# CB_1-2.net
KiCad netlist of a schematic drawn in EAGLE
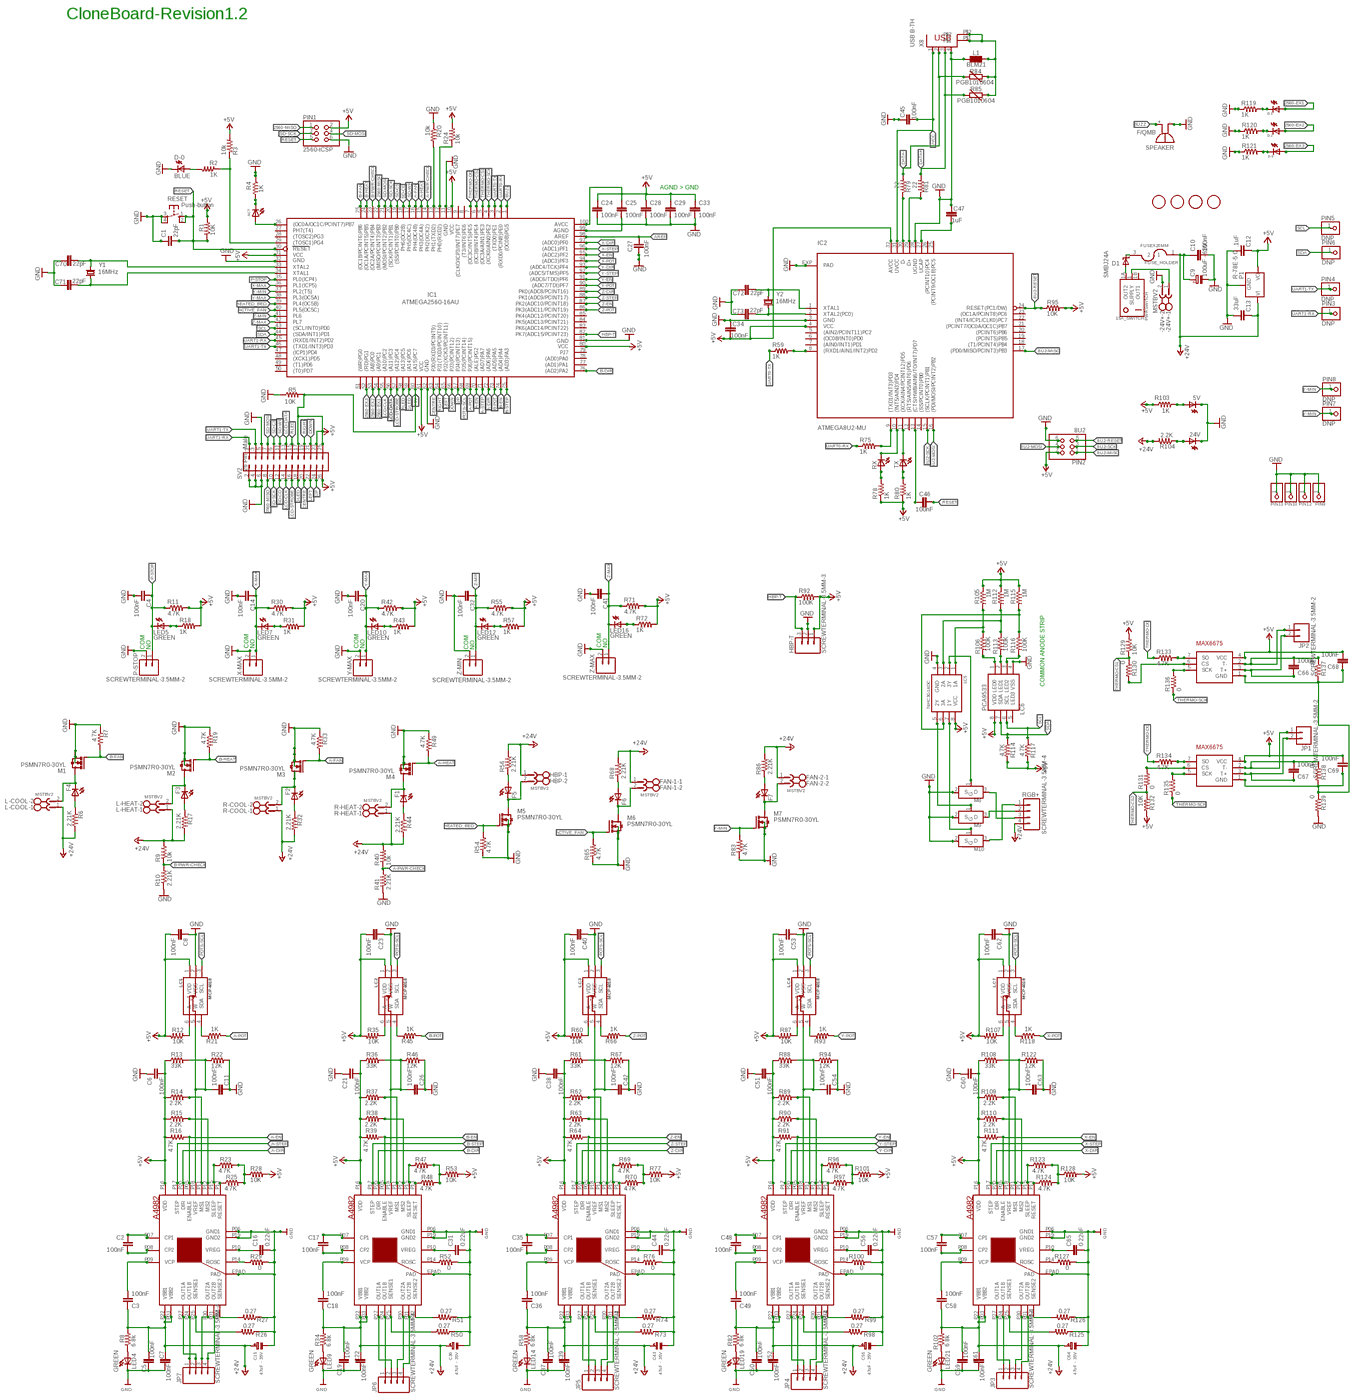
[diagram p0: schematic, sheet 1, overview]
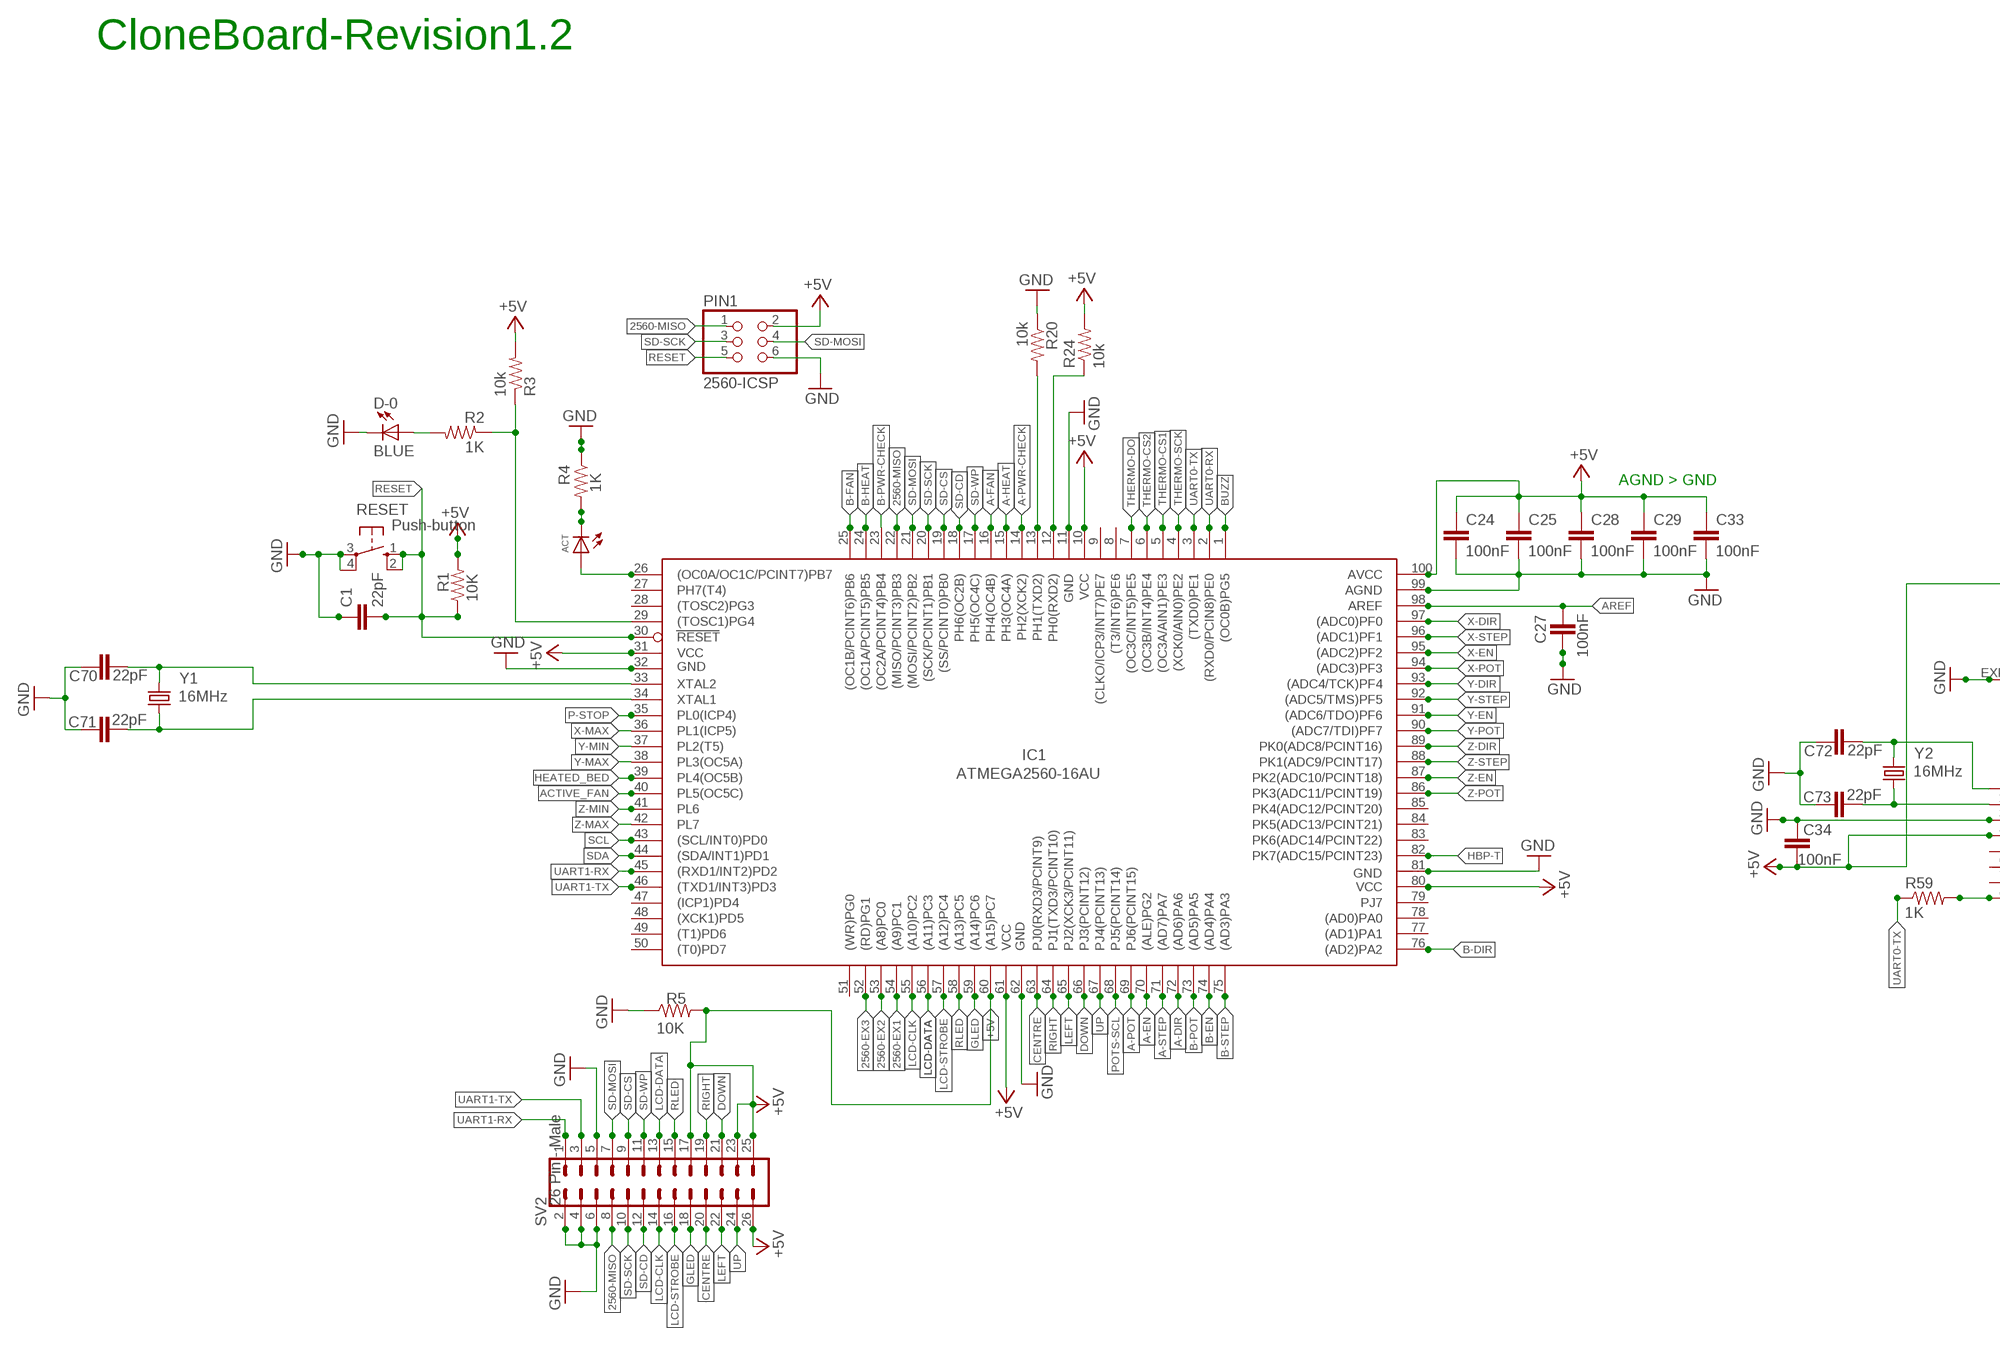
[diagram p1: schematic, sheet 1, part 1 of 4]
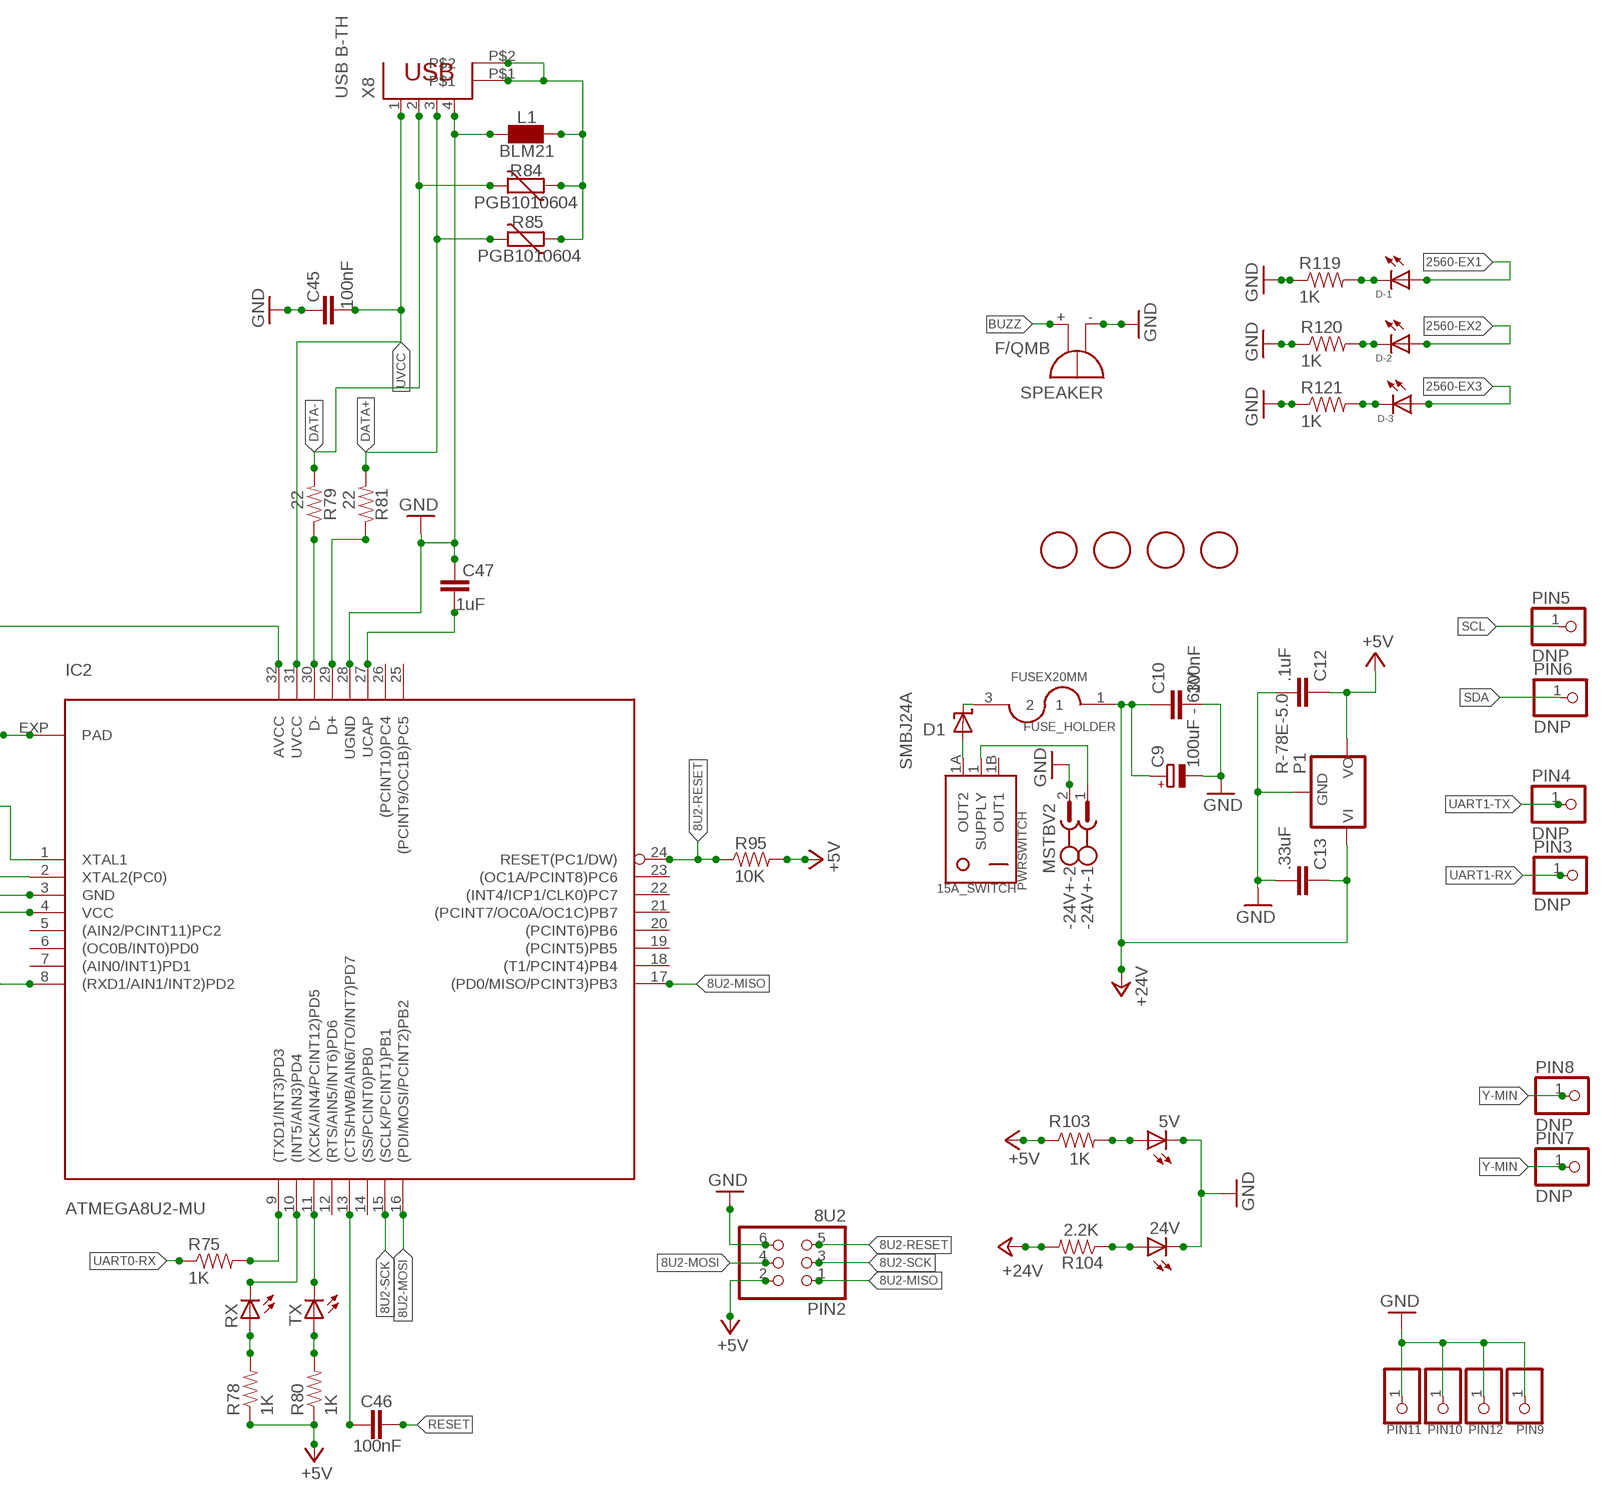
[diagram p2: schematic, sheet 1, part 2 of 4]
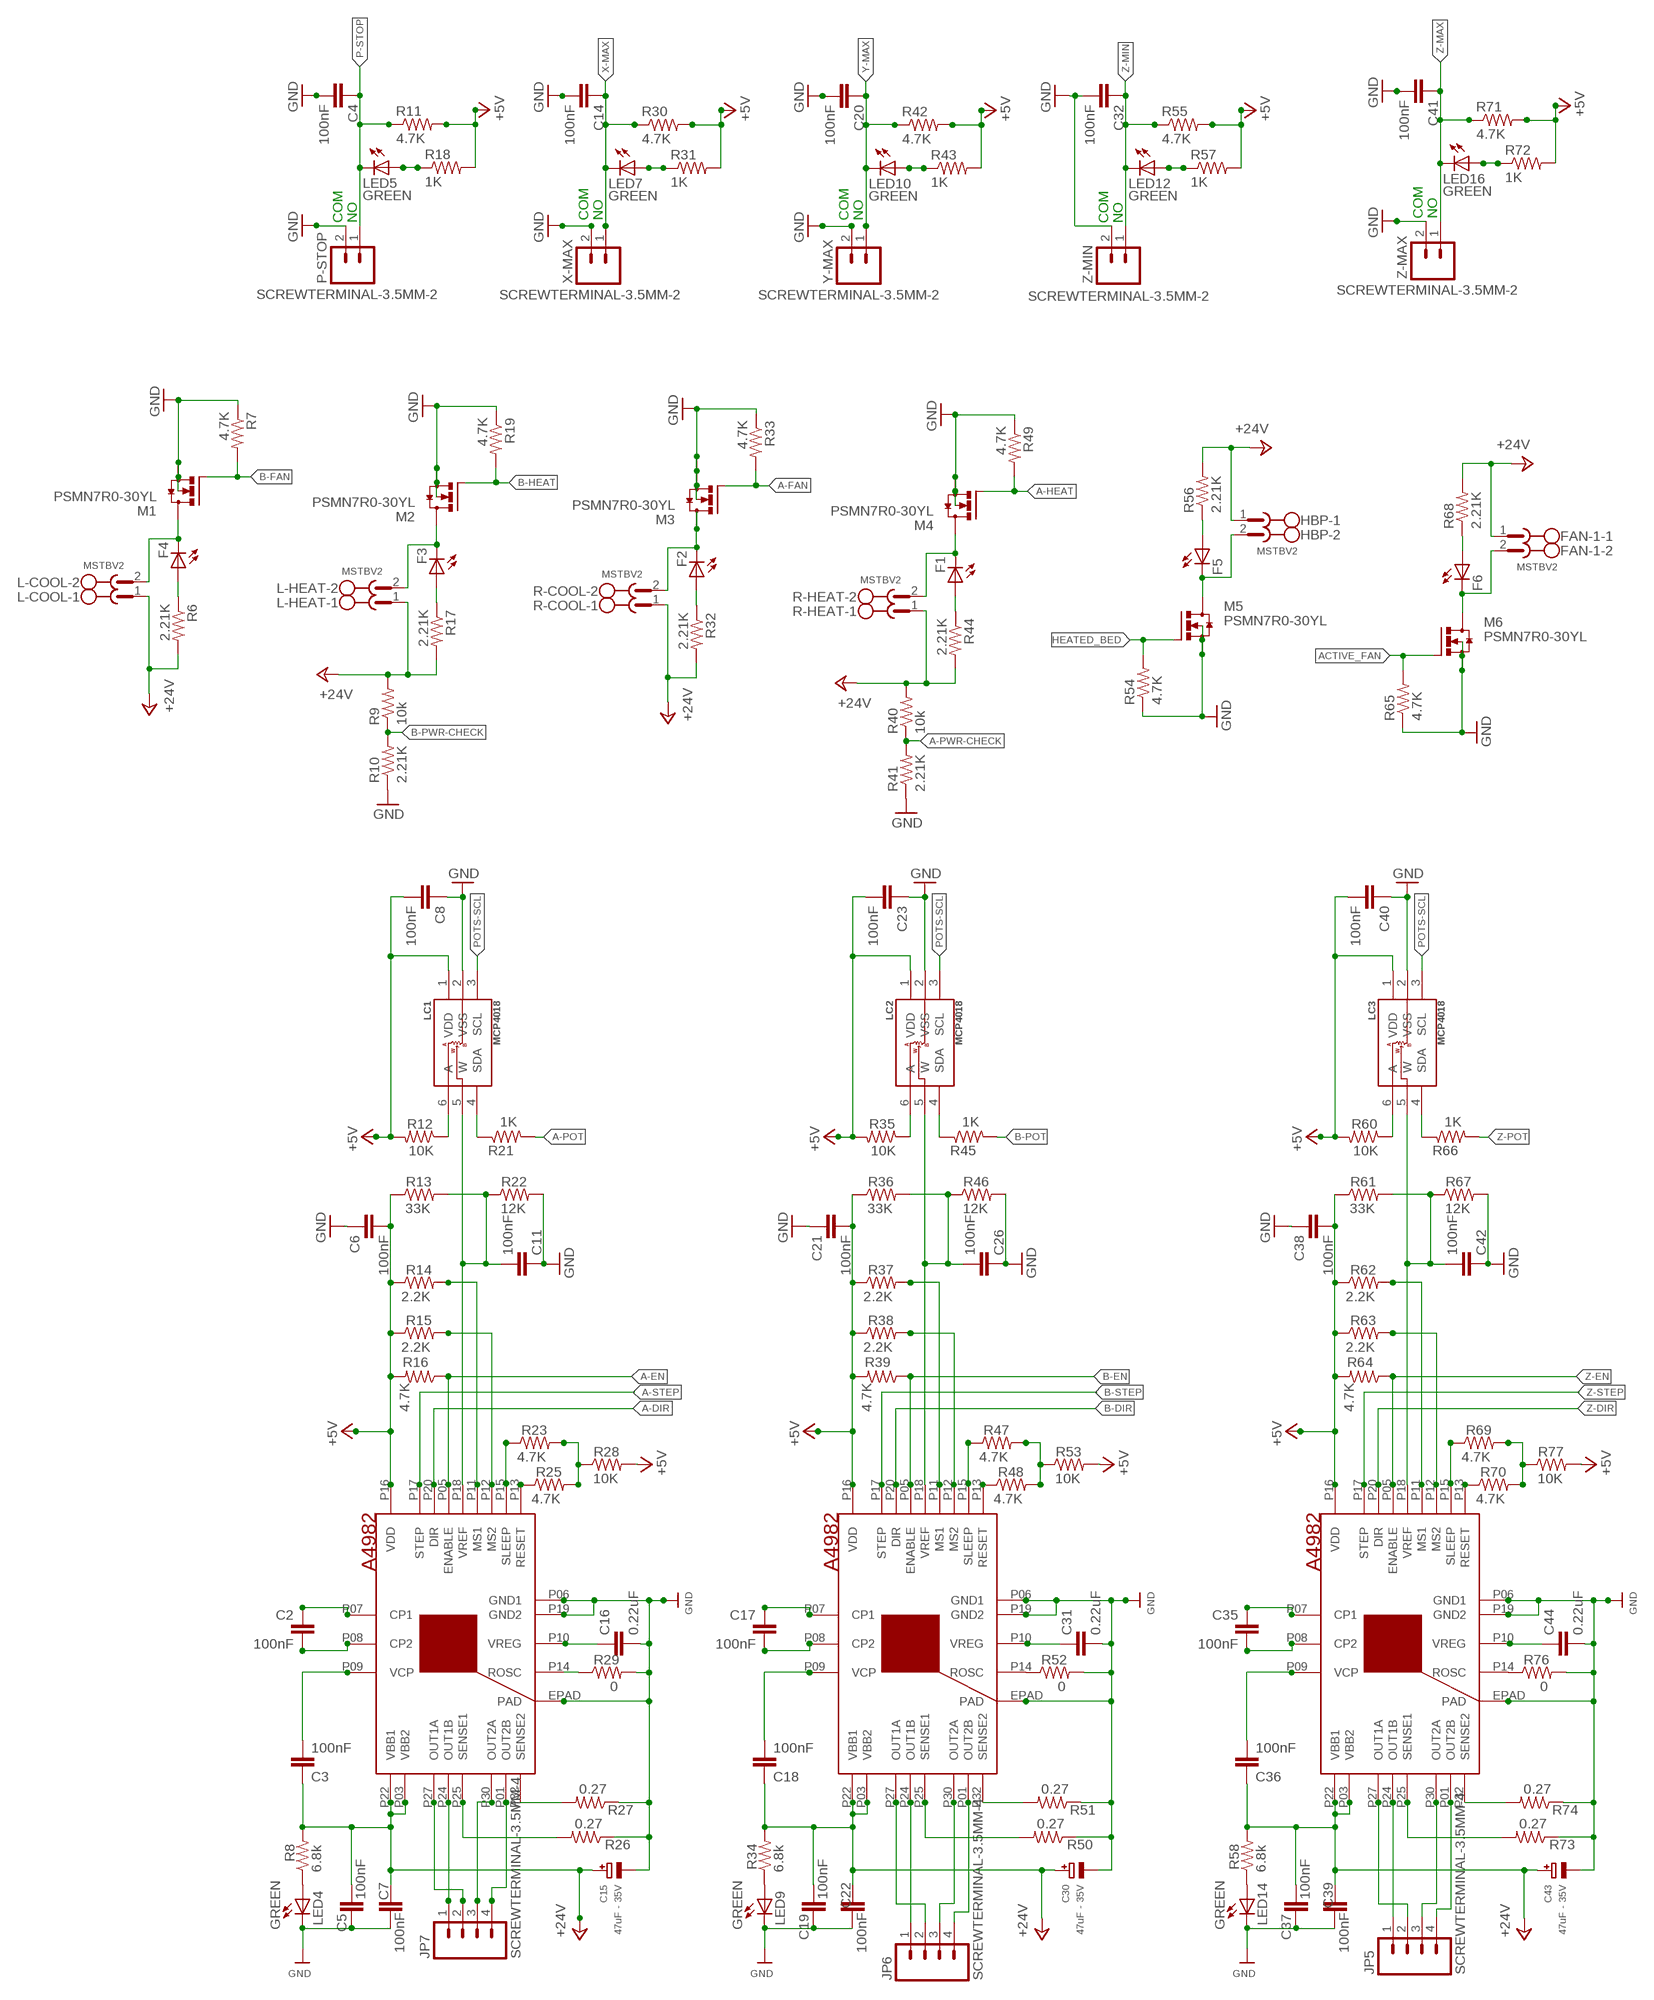
[diagram p3: schematic, sheet 1, part 3 of 4]
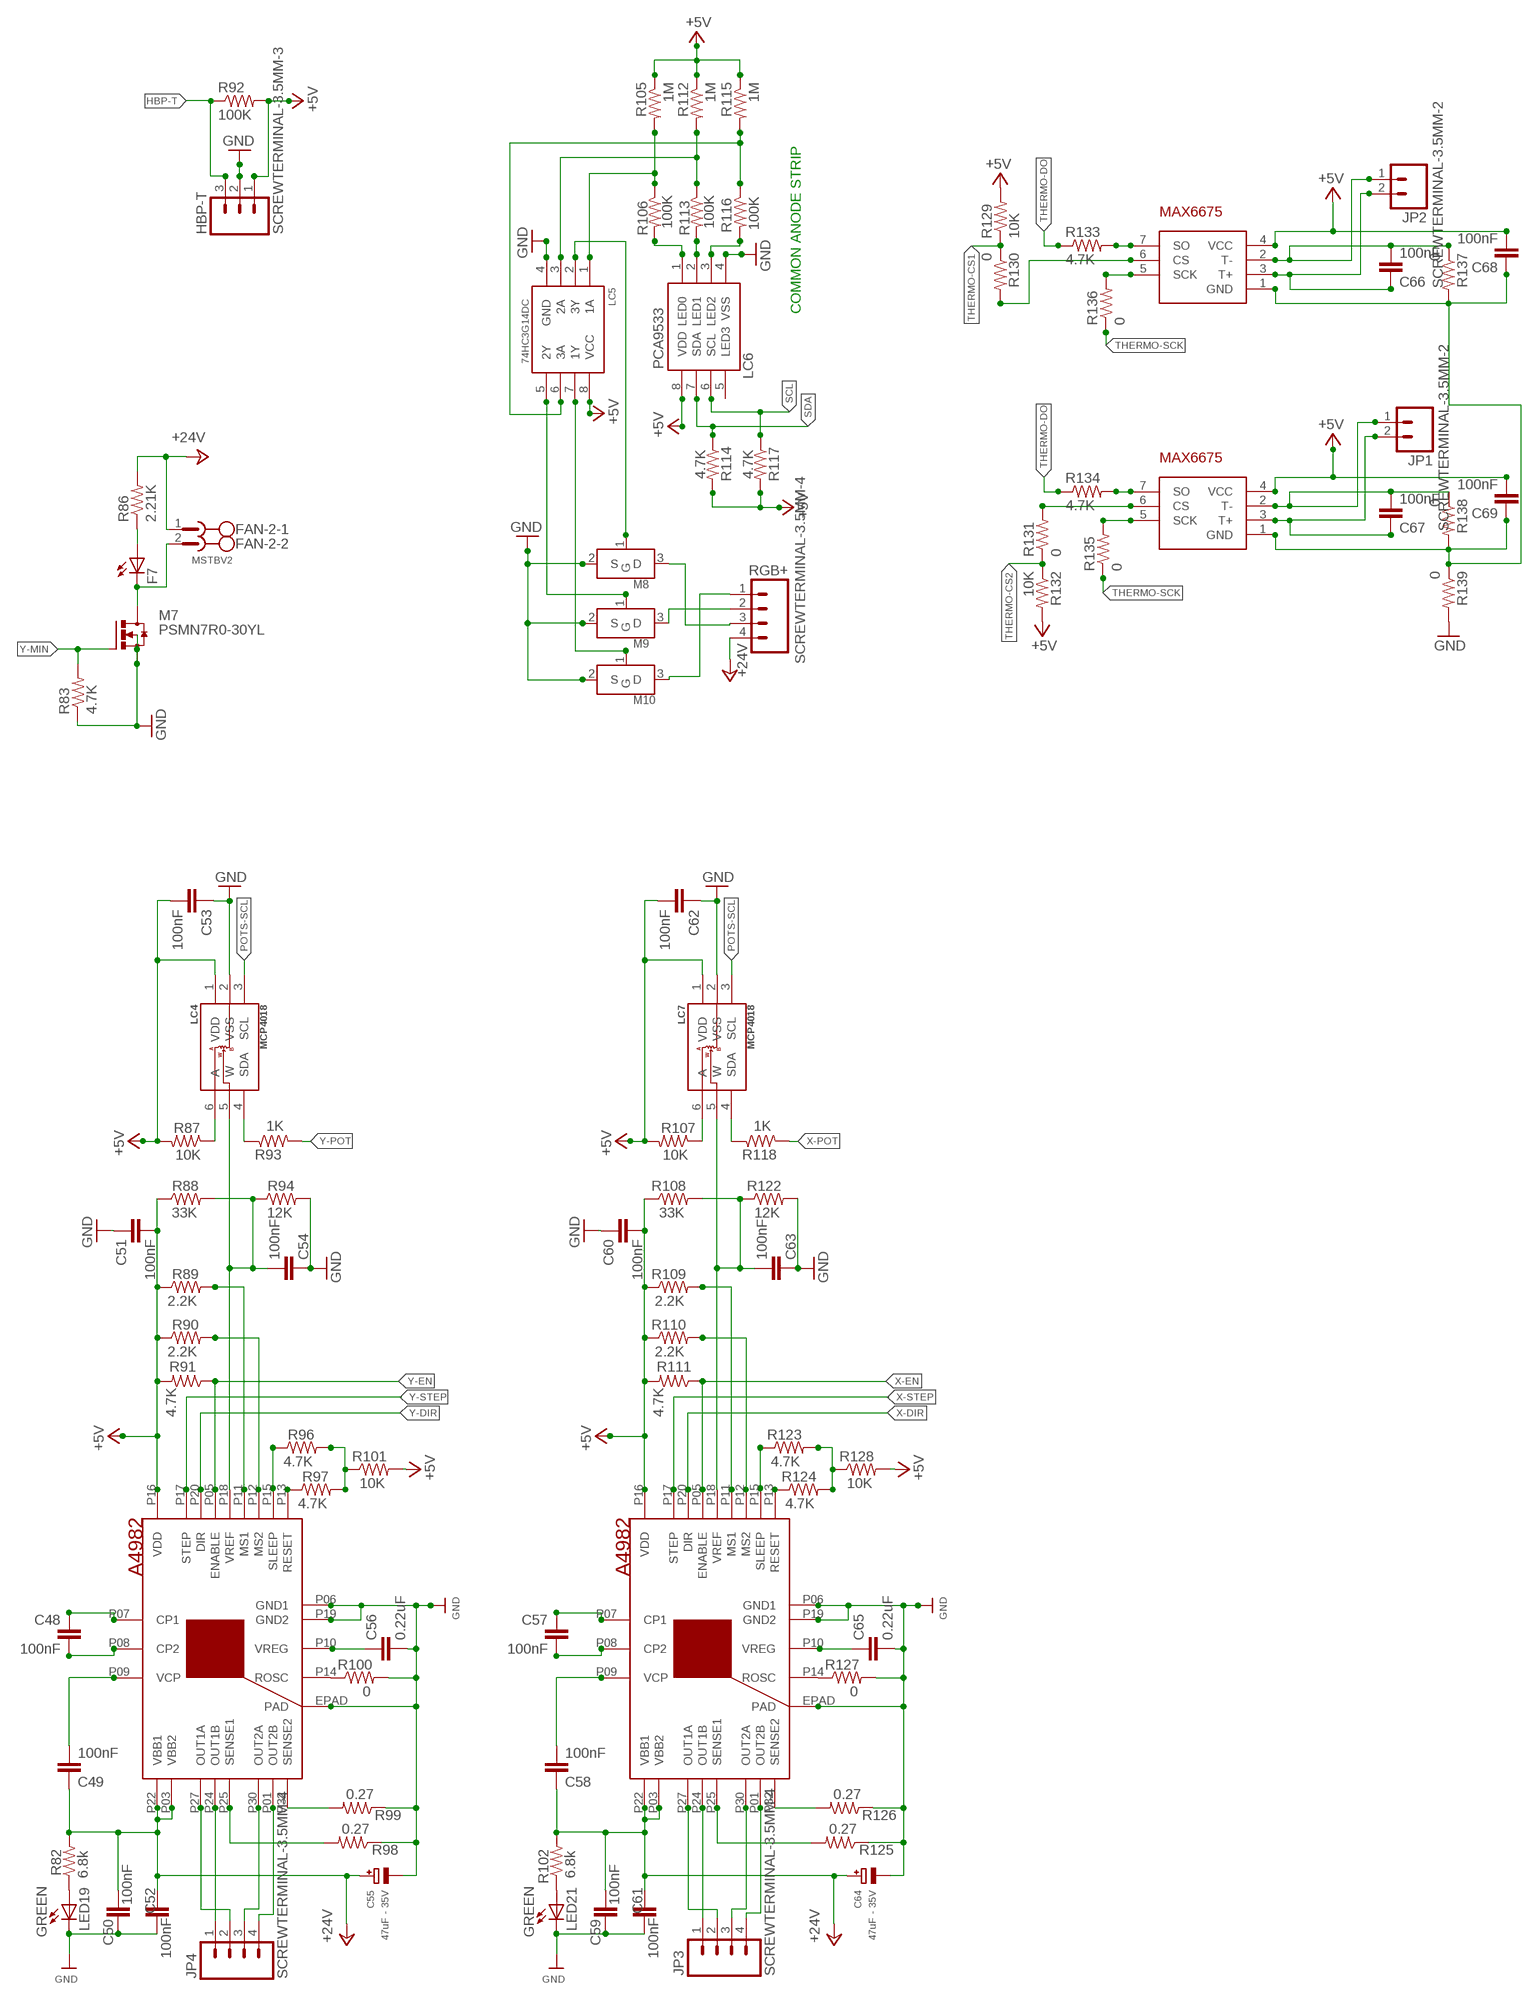
[diagram p4: schematic, sheet 1, part 4 of 4]

(export (version "E")
  (design (tool "Eeschema 10.0.6"))
  (components
    (comp (ref "-24V+")
      (value "MSTBV2")
      (footprint "eagle-import:MSTBV2")
      (fields (field (name "MPN") "MSTBV 2,5/2-GF-5.08"))
      (libsource (lib "eagle-import") (part "con-phoenix-508_MSTBV2"))
    )
    (comp (ref "5V")
      (value "BLUE")
      (footprint "eagle-import:LED-0805")
      (libsource (lib "eagle-import") (part "LED0805"))
    )
    (comp (ref "15A_SWITCH")
      (value "PWRSWITCH")
      (footprint "eagle-import:D501JT2S2APQF")
      (libsource (lib "eagle-import") (part "PWRSWITCH"))
    )
    (comp (ref "24V")
      (value "GREEN")
      (footprint "eagle-import:LED-0805")
      (libsource (lib "eagle-import") (part "LED0805"))
    )
    (comp (ref "A1")
      (value "A4982ETSSOP32")
      (footprint "eagle-import:ETSSOP32")
      (libsource (lib "eagle-import") (part "A4982ETSSOP32"))
    )
    (comp (ref "A2")
      (value "A4982ETSSOP32")
      (footprint "eagle-import:ETSSOP32")
      (libsource (lib "eagle-import") (part "A4982ETSSOP32"))
    )
    (comp (ref "A3")
      (value "A4982ETSSOP32")
      (footprint "eagle-import:ETSSOP32")
      (libsource (lib "eagle-import") (part "A4982ETSSOP32"))
    )
    (comp (ref "A4")
      (value "A4982ETSSOP32")
      (footprint "eagle-import:ETSSOP32")
      (libsource (lib "eagle-import") (part "A4982ETSSOP32"))
    )
    (comp (ref "A5")
      (value "A4982ETSSOP32")
      (footprint "eagle-import:ETSSOP32")
      (libsource (lib "eagle-import") (part "A4982ETSSOP32"))
    )
    (comp (ref "ACT")
      (value "BLUE")
      (footprint "eagle-import:LED-0805")
      (libsource (lib "eagle-import") (part "LED0805"))
    )
    (comp (ref "C1")
      (value "22pF")
      (footprint "eagle-import:0805")
      (libsource (lib "eagle-import") (part "CAP0805"))
    )
    (comp (ref "C2")
      (value "100nF")
      (footprint "eagle-import:0805")
      (libsource (lib "eagle-import") (part "CAP0805"))
    )
    (comp (ref "C3")
      (value "100nF")
      (footprint "eagle-import:0805")
      (libsource (lib "eagle-import") (part "CAP0805"))
    )
    (comp (ref "C4")
      (value "100nF")
      (footprint "eagle-import:0805")
      (libsource (lib "eagle-import") (part "CAP0805"))
    )
    (comp (ref "C5")
      (value "100nF")
      (footprint "eagle-import:0805")
      (libsource (lib "eagle-import") (part "CAP0805"))
    )
    (comp (ref "C6")
      (value "100nF")
      (footprint "eagle-import:0805")
      (libsource (lib "eagle-import") (part "CAP0805"))
    )
    (comp (ref "C7")
      (value "100nF")
      (footprint "eagle-import:0805")
      (libsource (lib "eagle-import") (part "CAP0805"))
    )
    (comp (ref "C8")
      (value "100nF")
      (footprint "eagle-import:0805")
      (libsource (lib "eagle-import") (part "CAP0805"))
    )
    (comp (ref "C9")
      (value "100uF - 63V")
      (footprint "eagle-import:E3,5-8")
      (libsource (lib "eagle-import") (part "CPOL-EUE3.5-8"))
    )
    (comp (ref "C10")
      (value "100nF")
      (footprint "eagle-import:0805")
      (libsource (lib "eagle-import") (part "CAP0805"))
    )
    (comp (ref "C11")
      (value "100nF")
      (footprint "eagle-import:0805")
      (libsource (lib "eagle-import") (part "CAP0805"))
    )
    (comp (ref "C12")
      (value ".1uF")
      (footprint "eagle-import:C0603")
      (libsource (lib "eagle-import") (part "C-EUC0603"))
    )
    (comp (ref "C13")
      (value ".33uF")
      (footprint "eagle-import:C0603")
      (libsource (lib "eagle-import") (part "C-EUC0603"))
    )
    (comp (ref "C14")
      (value "100nF")
      (footprint "eagle-import:0805")
      (libsource (lib "eagle-import") (part "CAP0805"))
    )
    (comp (ref "C15")
      (value "47uF - 35V")
      (footprint "eagle-import:EIA7343-31_D-R")
      (libsource (lib "eagle-import") (part "CAP_TANTALUMD/7343_REFLOW"))
    )
    (comp (ref "C16")
      (value "0.22uF")
      (footprint "eagle-import:0805")
      (libsource (lib "eagle-import") (part "SparkFun-Capacitors_CAP0805"))
    )
    (comp (ref "C17")
      (value "100nF")
      (footprint "eagle-import:0805")
      (libsource (lib "eagle-import") (part "CAP0805"))
    )
    (comp (ref "C18")
      (value "100nF")
      (footprint "eagle-import:0805")
      (libsource (lib "eagle-import") (part "CAP0805"))
    )
    (comp (ref "C19")
      (value "100nF")
      (footprint "eagle-import:0805")
      (libsource (lib "eagle-import") (part "CAP0805"))
    )
    (comp (ref "C20")
      (value "100nF")
      (footprint "eagle-import:0805")
      (libsource (lib "eagle-import") (part "CAP0805"))
    )
    (comp (ref "C21")
      (value "100nF")
      (footprint "eagle-import:0805")
      (libsource (lib "eagle-import") (part "CAP0805"))
    )
    (comp (ref "C22")
      (value "100nF")
      (footprint "eagle-import:0805")
      (libsource (lib "eagle-import") (part "CAP0805"))
    )
    (comp (ref "C23")
      (value "100nF")
      (footprint "eagle-import:0805")
      (libsource (lib "eagle-import") (part "CAP0805"))
    )
    (comp (ref "C24")
      (value "100nF")
      (footprint "eagle-import:0805")
      (libsource (lib "eagle-import") (part "CAP0805"))
    )
    (comp (ref "C25")
      (value "100nF")
      (footprint "eagle-import:0805")
      (libsource (lib "eagle-import") (part "CAP0805"))
    )
    (comp (ref "C26")
      (value "100nF")
      (footprint "eagle-import:0805")
      (libsource (lib "eagle-import") (part "CAP0805"))
    )
    (comp (ref "C27")
      (value "100nF")
      (footprint "eagle-import:0805")
      (libsource (lib "eagle-import") (part "CAP0805"))
    )
    (comp (ref "C28")
      (value "100nF")
      (footprint "eagle-import:0805")
      (libsource (lib "eagle-import") (part "CAP0805"))
    )
    (comp (ref "C29")
      (value "100nF")
      (footprint "eagle-import:0805")
      (libsource (lib "eagle-import") (part "CAP0805"))
    )
    (comp (ref "C30")
      (value "47uF - 35V")
      (footprint "eagle-import:EIA7343-31_D-R")
      (libsource (lib "eagle-import") (part "CAP_TANTALUMD/7343_REFLOW"))
    )
    (comp (ref "C31")
      (value "0.22uF")
      (footprint "eagle-import:0805")
      (libsource (lib "eagle-import") (part "SparkFun-Capacitors_CAP0805"))
    )
    (comp (ref "C32")
      (value "100nF")
      (footprint "eagle-import:0805")
      (libsource (lib "eagle-import") (part "CAP0805"))
    )
    (comp (ref "C33")
      (value "100nF")
      (footprint "eagle-import:0805")
      (libsource (lib "eagle-import") (part "CAP0805"))
    )
    (comp (ref "C34")
      (value "100nF")
      (footprint "eagle-import:0805")
      (libsource (lib "eagle-import") (part "CAP0805"))
    )
    (comp (ref "C35")
      (value "100nF")
      (footprint "eagle-import:0805")
      (libsource (lib "eagle-import") (part "CAP0805"))
    )
    (comp (ref "C36")
      (value "100nF")
      (footprint "eagle-import:0805")
      (libsource (lib "eagle-import") (part "CAP0805"))
    )
    (comp (ref "C37")
      (value "100nF")
      (footprint "eagle-import:0805")
      (libsource (lib "eagle-import") (part "CAP0805"))
    )
    (comp (ref "C38")
      (value "100nF")
      (footprint "eagle-import:0805")
      (libsource (lib "eagle-import") (part "CAP0805"))
    )
    (comp (ref "C39")
      (value "100nF")
      (footprint "eagle-import:0805")
      (libsource (lib "eagle-import") (part "CAP0805"))
    )
    (comp (ref "C40")
      (value "100nF")
      (footprint "eagle-import:0805")
      (libsource (lib "eagle-import") (part "CAP0805"))
    )
    (comp (ref "C41")
      (value "100nF")
      (footprint "eagle-import:0805")
      (libsource (lib "eagle-import") (part "CAP0805"))
    )
    (comp (ref "C42")
      (value "100nF")
      (footprint "eagle-import:0805")
      (libsource (lib "eagle-import") (part "CAP0805"))
    )
    (comp (ref "C43")
      (value "47uF - 35V")
      (footprint "eagle-import:EIA7343-31_D-R")
      (libsource (lib "eagle-import") (part "CAP_TANTALUMD/7343_REFLOW"))
    )
    (comp (ref "C44")
      (value "0.22uF")
      (footprint "eagle-import:0805")
      (libsource (lib "eagle-import") (part "SparkFun-Capacitors_CAP0805"))
    )
    (comp (ref "C45")
      (value "100nF")
      (footprint "eagle-import:0805")
      (libsource (lib "eagle-import") (part "CAP0805"))
    )
    (comp (ref "C46")
      (value "100nF")
      (footprint "eagle-import:0805")
      (libsource (lib "eagle-import") (part "SparkFun-Capacitors_CAP0805"))
    )
    (comp (ref "C47")
      (value "1uF")
      (footprint "eagle-import:0805")
      (libsource (lib "eagle-import") (part "CAP0805"))
    )
    (comp (ref "C48")
      (value "100nF")
      (footprint "eagle-import:0805")
      (libsource (lib "eagle-import") (part "CAP0805"))
    )
    (comp (ref "C49")
      (value "100nF")
      (footprint "eagle-import:0805")
      (libsource (lib "eagle-import") (part "CAP0805"))
    )
    (comp (ref "C50")
      (value "100nF")
      (footprint "eagle-import:0805")
      (libsource (lib "eagle-import") (part "CAP0805"))
    )
    (comp (ref "C51")
      (value "100nF")
      (footprint "eagle-import:0805")
      (libsource (lib "eagle-import") (part "CAP0805"))
    )
    (comp (ref "C52")
      (value "100nF")
      (footprint "eagle-import:0805")
      (libsource (lib "eagle-import") (part "CAP0805"))
    )
    (comp (ref "C53")
      (value "100nF")
      (footprint "eagle-import:0805")
      (libsource (lib "eagle-import") (part "CAP0805"))
    )
    (comp (ref "C54")
      (value "100nF")
      (footprint "eagle-import:0805")
      (libsource (lib "eagle-import") (part "CAP0805"))
    )
    (comp (ref "C55")
      (value "47uF - 35V")
      (footprint "eagle-import:EIA7343-31_D-R")
      (libsource (lib "eagle-import") (part "CAP_TANTALUMD/7343_REFLOW"))
    )
    (comp (ref "C56")
      (value "0.22uF")
      (footprint "eagle-import:0805")
      (libsource (lib "eagle-import") (part "SparkFun-Capacitors_CAP0805"))
    )
    (comp (ref "C57")
      (value "100nF")
      (footprint "eagle-import:0805")
      (libsource (lib "eagle-import") (part "CAP0805"))
    )
    (comp (ref "C58")
      (value "100nF")
      (footprint "eagle-import:0805")
      (libsource (lib "eagle-import") (part "CAP0805"))
    )
    (comp (ref "C59")
      (value "100nF")
      (footprint "eagle-import:0805")
      (libsource (lib "eagle-import") (part "CAP0805"))
    )
    (comp (ref "C60")
      (value "100nF")
      (footprint "eagle-import:0805")
      (libsource (lib "eagle-import") (part "CAP0805"))
    )
    (comp (ref "C61")
      (value "100nF")
      (footprint "eagle-import:0805")
      (libsource (lib "eagle-import") (part "CAP0805"))
    )
    (comp (ref "C62")
      (value "100nF")
      (footprint "eagle-import:0805")
      (libsource (lib "eagle-import") (part "CAP0805"))
    )
    (comp (ref "C63")
      (value "100nF")
      (footprint "eagle-import:0805")
      (libsource (lib "eagle-import") (part "CAP0805"))
    )
    (comp (ref "C64")
      (value "47uF - 35V")
      (footprint "eagle-import:EIA7343-31_D-R")
      (libsource (lib "eagle-import") (part "CAP_TANTALUMD/7343_REFLOW"))
    )
    (comp (ref "C65")
      (value "0.22uF")
      (footprint "eagle-import:0805")
      (libsource (lib "eagle-import") (part "SparkFun-Capacitors_CAP0805"))
    )
    (comp (ref "C66")
      (value "100nF")
      (footprint "eagle-import:0805")
      (libsource (lib "eagle-import") (part "CAP0805"))
    )
    (comp (ref "C67")
      (value "100nF")
      (footprint "eagle-import:0805")
      (libsource (lib "eagle-import") (part "CAP0805"))
    )
    (comp (ref "C68")
      (value "100nF")
      (footprint "eagle-import:0805")
      (libsource (lib "eagle-import") (part "CAP0805"))
    )
    (comp (ref "C69")
      (value "100nF")
      (footprint "eagle-import:0805")
      (libsource (lib "eagle-import") (part "CAP0805"))
    )
    (comp (ref "C70")
      (value "22pF")
      (footprint "eagle-import:0805")
      (libsource (lib "eagle-import") (part "CAP0805"))
    )
    (comp (ref "C71")
      (value "22pF")
      (footprint "eagle-import:0805")
      (libsource (lib "eagle-import") (part "CAP0805"))
    )
    (comp (ref "C72")
      (value "22pF")
      (footprint "eagle-import:0805")
      (libsource (lib "eagle-import") (part "CAP0805"))
    )
    (comp (ref "C73")
      (value "22pF")
      (footprint "eagle-import:0805")
      (libsource (lib "eagle-import") (part "CAP0805"))
    )
    (comp (ref "D-0")
      (value "BLUE")
      (footprint "eagle-import:LED-0805")
      (libsource (lib "eagle-import") (part "LED0805"))
    )
    (comp (ref "D-1")
      (value "YELLOW")
      (footprint "eagle-import:LED-0805")
      (libsource (lib "eagle-import") (part "LED0805"))
    )
    (comp (ref "D-2")
      (value "ORANGE")
      (footprint "eagle-import:LED-0805")
      (libsource (lib "eagle-import") (part "LED0805"))
    )
    (comp (ref "D-3")
      (value "RED")
      (footprint "eagle-import:LED-0805")
      (libsource (lib "eagle-import") (part "LED0805"))
    )
    (comp (ref "D1")
      (value "SMBJ24A")
      (footprint "eagle-import:SMBJ")
      (libsource (lib "eagle-import") (part "SUPPRESSOR-SMBJ"))
    )
    (comp (ref "F1")
      (value "RED")
      (footprint "eagle-import:LED-0805")
      (libsource (lib "eagle-import") (part "LED0805"))
    )
    (comp (ref "F2")
      (value "Yellow")
      (footprint "eagle-import:LED-0805")
      (libsource (lib "eagle-import") (part "LED0805"))
    )
    (comp (ref "F3")
      (value "RED")
      (footprint "eagle-import:LED-0805")
      (libsource (lib "eagle-import") (part "LED0805"))
    )
    (comp (ref "F4")
      (value "Yellow")
      (footprint "eagle-import:LED-0805")
      (libsource (lib "eagle-import") (part "LED0805"))
    )
    (comp (ref "F5")
      (value "RED")
      (footprint "eagle-import:LED-0805")
      (libsource (lib "eagle-import") (part "LED0805"))
    )
    (comp (ref "F6")
      (value "Yellow")
      (footprint "eagle-import:LED-0805")
      (libsource (lib "eagle-import") (part "LED0805"))
    )
    (comp (ref "F7")
      (value "Yellow")
      (footprint "eagle-import:LED-0805")
      (libsource (lib "eagle-import") (part "LED0805"))
    )
    (comp (ref "FAN-1")
      (value "MSTBV2")
      (footprint "eagle-import:MSTBV2")
      (fields (field (name "MPN") "MSTBV 2,5/2-GF-5.08"))
      (libsource (lib "eagle-import") (part "MSTBV2"))
    )
    (comp (ref "FAN-2")
      (value "MSTBV2")
      (footprint "eagle-import:MSTBV2")
      (fields (field (name "MPN") "MSTBV 2,5/2-GF-5.08"))
      (libsource (lib "eagle-import") (part "MSTBV2"))
    )
    (comp (ref "FID1")
      (value "FIDUCIALMOUNT")
      (footprint "eagle-import:FIDUCIA-MOUNT")
      (libsource (lib "eagle-import") (part "FIDUCIALMOUNT"))
    )
    (comp (ref "FID2")
      (value "FIDUCIALMOUNT")
      (footprint "eagle-import:FIDUCIA-MOUNT")
      (libsource (lib "eagle-import") (part "FIDUCIALMOUNT"))
    )
    (comp (ref "FID3")
      (value "FIDUCIALMOUNT")
      (footprint "eagle-import:FIDUCIA-MOUNT")
      (libsource (lib "eagle-import") (part "FIDUCIALMOUNT"))
    )
    (comp (ref "FID4")
      (value "FIDUCIALMOUNT")
      (footprint "eagle-import:FIDUCIA-MOUNT")
      (libsource (lib "eagle-import") (part "FIDUCIALMOUNT"))
    )
    (comp (ref "FUSE_HOLDER")
      (value "FUSEX20MM")
      (footprint "eagle-import:FUSE_5MM")
      (libsource (lib "eagle-import") (part "FUSEX20MM"))
    )
    (comp (ref "HBP")
      (value "MSTBV2")
      (footprint "eagle-import:MSTBV2")
      (fields (field (name "MPN") "MSTBV 2,5/2-GF-5.08"))
      (libsource (lib "eagle-import") (part "MSTBV2"))
    )
    (comp (ref "HBP-T")
      (value "SCREWTERMINAL-3.5MM-3")
      (footprint "eagle-import:SCREWTERMINAL-3.5MM-3")
      (libsource (lib "eagle-import") (part "M03SCREW"))
    )
    (comp (ref "IC1")
      (value "ATMEGA2560-16AU")
      (footprint "eagle-import:TQFP100")
      (libsource (lib "eagle-import") (part "ATMEGAAU2560-16"))
    )
    (comp (ref "IC2")
      (value "ATMEGA8U2-MU")
      (footprint "eagle-import:ATMEL_QFN32")
      (libsource (lib "eagle-import") (part "ATMEGA8U2"))
    )
    (comp (ref "JP1")
      (value "SCREWTERMINAL-3.5MM-2")
      (footprint "eagle-import:SCREWTERMINAL-3.5MM-2")
      (libsource (lib "eagle-import") (part "M023.5MM"))
    )
    (comp (ref "JP2")
      (value "SCREWTERMINAL-3.5MM-2")
      (footprint "eagle-import:SCREWTERMINAL-3.5MM-2")
      (libsource (lib "eagle-import") (part "M023.5MM"))
    )
    (comp (ref "JP3")
      (value "SCREWTERMINAL-3.5MM-4")
      (footprint "eagle-import:SCREWTERMINAL-3.5MM-4_LOCK")
      (libsource (lib "eagle-import") (part "M04SCREW_LOCK"))
    )
    (comp (ref "JP4")
      (value "SCREWTERMINAL-3.5MM-4")
      (footprint "eagle-import:SCREWTERMINAL-3.5MM-4_LOCK")
      (libsource (lib "eagle-import") (part "M04SCREW_LOCK"))
    )
    (comp (ref "JP5")
      (value "SCREWTERMINAL-3.5MM-4")
      (footprint "eagle-import:SCREWTERMINAL-3.5MM-4_LOCK")
      (libsource (lib "eagle-import") (part "M04SCREW_LOCK"))
    )
    (comp (ref "JP6")
      (value "SCREWTERMINAL-3.5MM-4")
      (footprint "eagle-import:SCREWTERMINAL-3.5MM-4_LOCK")
      (libsource (lib "eagle-import") (part "M04SCREW_LOCK"))
    )
    (comp (ref "JP7")
      (value "SCREWTERMINAL-3.5MM-4")
      (footprint "eagle-import:SCREWTERMINAL-3.5MM-4_LOCK")
      (libsource (lib "eagle-import") (part "M04SCREW_LOCK"))
    )
    (comp (ref "L-COOL")
      (value "MSTBV2")
      (footprint "eagle-import:MSTBV2")
      (fields (field (name "MPN") "MSTBV 2,5/2-GF-5.08"))
      (libsource (lib "eagle-import") (part "MSTBV2"))
    )
    (comp (ref "L-HEAT")
      (value "MSTBV2")
      (footprint "eagle-import:MSTBV2")
      (fields (field (name "MPN") "MSTBV 2,5/2-GF-5.08"))
      (libsource (lib "eagle-import") (part "MSTBV2"))
    )
    (comp (ref "L1")
      (value "BLM21")
      (footprint "eagle-import:0805")
      (libsource (lib "eagle-import") (part "WE-CBF_0805"))
    )
    (comp (ref "LC1")
      (value "MCP4018")
      (footprint "eagle-import:SC70-6L")
      (libsource (lib "eagle-import") (part "MCP4018"))
    )
    (comp (ref "LC2")
      (value "MCP4018")
      (footprint "eagle-import:SC70-6L")
      (libsource (lib "eagle-import") (part "MCP4018"))
    )
    (comp (ref "LC3")
      (value "MCP4018")
      (footprint "eagle-import:SC70-6L")
      (libsource (lib "eagle-import") (part "MCP4018"))
    )
    (comp (ref "LC4")
      (value "MCP4018")
      (footprint "eagle-import:SC70-6L")
      (libsource (lib "eagle-import") (part "MCP4018"))
    )
    (comp (ref "LC5")
      (value "74HC3G14DC")
      (footprint "eagle-import:VSSOP8")
      (libsource (lib "eagle-import") (part "74HC3G14DC"))
    )
    (comp (ref "LC6")
      (value "PCA9533")
      (footprint "eagle-import:SO8")
      (libsource (lib "eagle-import") (part "PCA9533"))
    )
    (comp (ref "LC7")
      (value "MCP4018")
      (footprint "eagle-import:SC70-6L")
      (libsource (lib "eagle-import") (part "MCP4018"))
    )
    (comp (ref "LED4")
      (value "GREEN")
      (footprint "eagle-import:LED-0805")
      (libsource (lib "eagle-import") (part "LED0805"))
    )
    (comp (ref "LED5")
      (value "GREEN")
      (footprint "eagle-import:LED-0805")
      (libsource (lib "eagle-import") (part "LED0805"))
    )
    (comp (ref "LED7")
      (value "GREEN")
      (footprint "eagle-import:LED-0805")
      (libsource (lib "eagle-import") (part "LED0805"))
    )
    (comp (ref "LED9")
      (value "GREEN")
      (footprint "eagle-import:LED-0805")
      (libsource (lib "eagle-import") (part "LED0805"))
    )
    (comp (ref "LED10")
      (value "GREEN")
      (footprint "eagle-import:LED-0805")
      (libsource (lib "eagle-import") (part "LED0805"))
    )
    (comp (ref "LED12")
      (value "GREEN")
      (footprint "eagle-import:LED-0805")
      (libsource (lib "eagle-import") (part "LED0805"))
    )
    (comp (ref "LED14")
      (value "GREEN")
      (footprint "eagle-import:LED-0805")
      (libsource (lib "eagle-import") (part "LED0805"))
    )
    (comp (ref "LED16")
      (value "GREEN")
      (footprint "eagle-import:LED-0805")
      (libsource (lib "eagle-import") (part "LED0805"))
    )
    (comp (ref "LED19")
      (value "GREEN")
      (footprint "eagle-import:LED-0805")
      (libsource (lib "eagle-import") (part "LED0805"))
    )
    (comp (ref "LED21")
      (value "GREEN")
      (footprint "eagle-import:LED-0805")
      (libsource (lib "eagle-import") (part "LED0805"))
    )
    (comp (ref "M1")
      (value "PSMN7R0-30YL")
      (footprint "eagle-import:SOT669")
      (libsource (lib "eagle-import") (part "PSMN7R0-30YL"))
    )
    (comp (ref "M2")
      (value "PSMN7R0-30YL")
      (footprint "eagle-import:SOT669")
      (libsource (lib "eagle-import") (part "PSMN7R0-30YL"))
    )
    (comp (ref "M3")
      (value "PSMN7R0-30YL")
      (footprint "eagle-import:SOT669")
      (libsource (lib "eagle-import") (part "PSMN7R0-30YL"))
    )
    (comp (ref "M4")
      (value "PSMN7R0-30YL")
      (footprint "eagle-import:SOT669")
      (libsource (lib "eagle-import") (part "PSMN7R0-30YL"))
    )
    (comp (ref "M5")
      (value "PSMN7R0-30YL")
      (footprint "eagle-import:SOT669")
      (libsource (lib "eagle-import") (part "PSMN7R0-30YL"))
    )
    (comp (ref "M6")
      (value "PSMN7R0-30YL")
      (footprint "eagle-import:SOT669")
      (libsource (lib "eagle-import") (part "PSMN7R0-30YL"))
    )
    (comp (ref "M7")
      (value "PSMN7R0-30YL")
      (footprint "eagle-import:SOT669")
      (libsource (lib "eagle-import") (part "PSMN7R0-30YL"))
    )
    (comp (ref "M8")
      (value "FDV301N")
      (footprint "eagle-import:SOT-23")
      (libsource (lib "eagle-import") (part "FDV301N"))
    )
    (comp (ref "M9")
      (value "FDV301N")
      (footprint "eagle-import:SOT-23")
      (libsource (lib "eagle-import") (part "FDV301N"))
    )
    (comp (ref "M10")
      (value "FDV301N")
      (footprint "eagle-import:SOT-23")
      (libsource (lib "eagle-import") (part "FDV301N"))
    )
    (comp (ref "P-STOP")
      (value "SCREWTERMINAL-3.5MM-2")
      (footprint "eagle-import:SCREWTERMINAL-3.5MM-2")
      (libsource (lib "eagle-import") (part "M023.5MM"))
    )
    (comp (ref "P1")
      (value "R-78E-5.0")
      (footprint "eagle-import:R-78")
      (libsource (lib "eagle-import") (part "R-78"))
    )
    (comp (ref "PIN1")
      (value "2560-ICSP")
      (footprint "eagle-import:2X03")
      (libsource (lib "eagle-import") (part "pinhead_PINHD-2X3"))
    )
    (comp (ref "PIN2")
      (value "8U2")
      (footprint "eagle-import:2X03")
      (libsource (lib "eagle-import") (part "PINHD-2X3"))
    )
    (comp (ref "PIN3")
      (value "DNP")
      (footprint "eagle-import:1X01")
      (libsource (lib "eagle-import") (part "PINHD-1X1"))
    )
    (comp (ref "PIN4")
      (value "DNP")
      (footprint "eagle-import:1X01")
      (libsource (lib "eagle-import") (part "PINHD-1X1"))
    )
    (comp (ref "PIN5")
      (value "DNP")
      (footprint "eagle-import:1X01")
      (libsource (lib "eagle-import") (part "PINHD-1X1"))
    )
    (comp (ref "PIN6")
      (value "DNP")
      (footprint "eagle-import:1X01")
      (libsource (lib "eagle-import") (part "PINHD-1X1"))
    )
    (comp (ref "PIN7")
      (value "DNP")
      (footprint "eagle-import:1X01")
      (libsource (lib "eagle-import") (part "PINHD-1X1"))
    )
    (comp (ref "PIN8")
      (value "DNP")
      (footprint "eagle-import:1X01")
      (libsource (lib "eagle-import") (part "PINHD-1X1"))
    )
    (comp (ref "PIN9")
      (value "DNP")
      (footprint "eagle-import:1X01")
      (libsource (lib "eagle-import") (part "pinhead_PINHD-1X1"))
    )
    (comp (ref "PIN10")
      (value "DNP")
      (footprint "eagle-import:1X01")
      (libsource (lib "eagle-import") (part "pinhead_PINHD-1X1"))
    )
    (comp (ref "PIN11")
      (value "DNP")
      (footprint "eagle-import:1X01")
      (libsource (lib "eagle-import") (part "pinhead_PINHD-1X1"))
    )
    (comp (ref "PIN12")
      (value "DNP")
      (footprint "eagle-import:1X01")
      (libsource (lib "eagle-import") (part "pinhead_PINHD-1X1"))
    )
    (comp (ref "R-COOL")
      (value "MSTBV2")
      (footprint "eagle-import:MSTBV2")
      (fields (field (name "MPN") "MSTBV 2,5/2-GF-5.08"))
      (libsource (lib "eagle-import") (part "MSTBV2"))
    )
    (comp (ref "R-HEAT")
      (value "MSTBV2")
      (footprint "eagle-import:MSTBV2")
      (fields (field (name "MPN") "MSTBV 2,5/2-GF-5.08"))
      (libsource (lib "eagle-import") (part "MSTBV2"))
    )
    (comp (ref "R1")
      (value "10K")
      (footprint "eagle-import:0805")
      (libsource (lib "eagle-import") (part "RESISTOR"))
    )
    (comp (ref "R2")
      (value "1K")
      (footprint "eagle-import:0805")
      (libsource (lib "eagle-import") (part "RESISTOR"))
    )
    (comp (ref "R3")
      (value "10k")
      (footprint "eagle-import:0805")
      (libsource (lib "eagle-import") (part "RESISTOR"))
    )
    (comp (ref "R4")
      (value "1K")
      (footprint "eagle-import:0805")
      (libsource (lib "eagle-import") (part "RESISTOR"))
    )
    (comp (ref "R5")
      (value "10K")
      (footprint "eagle-import:0805")
      (libsource (lib "eagle-import") (part "RESISTOR"))
    )
    (comp (ref "R6")
      (value "2.21K")
      (footprint "eagle-import:0805")
      (libsource (lib "eagle-import") (part "RESISTOR"))
    )
    (comp (ref "R7")
      (value "4.7K")
      (footprint "eagle-import:0805")
      (libsource (lib "eagle-import") (part "RESISTOR"))
    )
    (comp (ref "R8")
      (value "6.8k")
      (footprint "eagle-import:0805")
      (libsource (lib "eagle-import") (part "RESISTOR"))
    )
    (comp (ref "R9")
      (value "10k")
      (footprint "eagle-import:0805")
      (libsource (lib "eagle-import") (part "RESISTOR"))
    )
    (comp (ref "R10")
      (value "2.21K")
      (footprint "eagle-import:0805")
      (libsource (lib "eagle-import") (part "RESISTOR"))
    )
    (comp (ref "R11")
      (value "4.7K")
      (footprint "eagle-import:0805")
      (libsource (lib "eagle-import") (part "RESISTOR"))
    )
    (comp (ref "R12")
      (value "10K")
      (footprint "eagle-import:0805")
      (libsource (lib "eagle-import") (part "RESISTOR"))
    )
    (comp (ref "R13")
      (value "33K")
      (footprint "eagle-import:0805")
      (libsource (lib "eagle-import") (part "RESISTOR"))
    )
    (comp (ref "R14")
      (value "2.2K")
      (footprint "eagle-import:0805")
      (libsource (lib "eagle-import") (part "RESISTOR"))
    )
    (comp (ref "R15")
      (value "2.2K")
      (footprint "eagle-import:0805")
      (libsource (lib "eagle-import") (part "RESISTOR"))
    )
    (comp (ref "R16")
      (value "4.7K")
      (footprint "eagle-import:0805")
      (libsource (lib "eagle-import") (part "RESISTOR"))
    )
    (comp (ref "R17")
      (value "2.21K")
      (footprint "eagle-import:0805")
      (libsource (lib "eagle-import") (part "RESISTOR"))
    )
    (comp (ref "R18")
      (value "1K")
      (footprint "eagle-import:0805")
      (libsource (lib "eagle-import") (part "RESISTOR"))
    )
    (comp (ref "R19")
      (value "4.7K")
      (footprint "eagle-import:0805")
      (libsource (lib "eagle-import") (part "RESISTOR"))
    )
    (comp (ref "R20")
      (value "10k")
      (footprint "eagle-import:0805")
      (libsource (lib "eagle-import") (part "RESISTOR"))
    )
    (comp (ref "R21")
      (value "1K")
      (footprint "eagle-import:0805")
      (libsource (lib "eagle-import") (part "RESISTOR"))
    )
    (comp (ref "R22")
      (value "12K")
      (footprint "eagle-import:0805")
      (libsource (lib "eagle-import") (part "RESISTOR"))
    )
    (comp (ref "R23")
      (value "4.7K")
      (footprint "eagle-import:0805")
      (libsource (lib "eagle-import") (part "RESISTOR"))
    )
    (comp (ref "R24")
      (value "10k")
      (footprint "eagle-import:0805")
      (libsource (lib "eagle-import") (part "RESISTOR"))
    )
    (comp (ref "R25")
      (value "4.7K")
      (footprint "eagle-import:0805")
      (libsource (lib "eagle-import") (part "RESISTOR"))
    )
    (comp (ref "R26")
      (value "0.27")
      (footprint "eagle-import:0805")
      (libsource (lib "eagle-import") (part "RESISTOR"))
    )
    (comp (ref "R27")
      (value "0.27")
      (footprint "eagle-import:0805")
      (libsource (lib "eagle-import") (part "RESISTOR"))
    )
    (comp (ref "R28")
      (value "10K")
      (footprint "eagle-import:0805")
      (libsource (lib "eagle-import") (part "RESISTOR"))
    )
    (comp (ref "R29")
      (value "0")
      (footprint "eagle-import:0805")
      (libsource (lib "eagle-import") (part "RESISTOR"))
    )
    (comp (ref "R30")
      (value "4.7K")
      (footprint "eagle-import:0805")
      (libsource (lib "eagle-import") (part "RESISTOR"))
    )
    (comp (ref "R31")
      (value "1K")
      (footprint "eagle-import:0805")
      (libsource (lib "eagle-import") (part "RESISTOR"))
    )
    (comp (ref "R32")
      (value "2.21K")
      (footprint "eagle-import:0805")
      (libsource (lib "eagle-import") (part "RESISTOR"))
    )
    (comp (ref "R33")
      (value "4.7K")
      (footprint "eagle-import:0805")
      (libsource (lib "eagle-import") (part "RESISTOR"))
    )
    (comp (ref "R34")
      (value "6.8k")
      (footprint "eagle-import:0805")
      (libsource (lib "eagle-import") (part "RESISTOR"))
    )
    (comp (ref "R35")
      (value "10K")
      (footprint "eagle-import:0805")
      (libsource (lib "eagle-import") (part "RESISTOR"))
    )
    (comp (ref "R36")
      (value "33K")
      (footprint "eagle-import:0805")
      (libsource (lib "eagle-import") (part "RESISTOR"))
    )
    (comp (ref "R37")
      (value "2.2K")
      (footprint "eagle-import:0805")
      (libsource (lib "eagle-import") (part "RESISTOR"))
    )
    (comp (ref "R38")
      (value "2.2K")
      (footprint "eagle-import:0805")
      (libsource (lib "eagle-import") (part "RESISTOR"))
    )
    (comp (ref "R39")
      (value "4.7K")
      (footprint "eagle-import:0805")
      (libsource (lib "eagle-import") (part "RESISTOR"))
    )
    (comp (ref "R40")
      (value "10k")
      (footprint "eagle-import:0805")
      (libsource (lib "eagle-import") (part "RESISTOR"))
    )
    (comp (ref "R41")
      (value "2.21K")
      (footprint "eagle-import:0805")
      (libsource (lib "eagle-import") (part "RESISTOR"))
    )
    (comp (ref "R42")
      (value "4.7K")
      (footprint "eagle-import:0805")
      (libsource (lib "eagle-import") (part "RESISTOR"))
    )
    (comp (ref "R43")
      (value "1K")
      (footprint "eagle-import:0805")
      (libsource (lib "eagle-import") (part "RESISTOR"))
    )
    (comp (ref "R44")
      (value "2.21K")
      (footprint "eagle-import:0805")
      (libsource (lib "eagle-import") (part "RESISTOR"))
    )
    (comp (ref "R45")
      (value "1K")
      (footprint "eagle-import:0805")
      (libsource (lib "eagle-import") (part "RESISTOR"))
    )
    (comp (ref "R46")
      (value "12K")
      (footprint "eagle-import:0805")
      (libsource (lib "eagle-import") (part "RESISTOR"))
    )
    (comp (ref "R47")
      (value "4.7K")
      (footprint "eagle-import:0805")
      (libsource (lib "eagle-import") (part "RESISTOR"))
    )
    (comp (ref "R48")
      (value "4.7K")
      (footprint "eagle-import:0805")
      (libsource (lib "eagle-import") (part "RESISTOR"))
    )
    (comp (ref "R49")
      (value "4.7K")
      (footprint "eagle-import:0805")
      (libsource (lib "eagle-import") (part "RESISTOR"))
    )
    (comp (ref "R50")
      (value "0.27")
      (footprint "eagle-import:0805")
      (libsource (lib "eagle-import") (part "RESISTOR"))
    )
    (comp (ref "R51")
      (value "0.27")
      (footprint "eagle-import:0805")
      (libsource (lib "eagle-import") (part "RESISTOR"))
    )
    (comp (ref "R52")
      (value "0")
      (footprint "eagle-import:0805")
      (libsource (lib "eagle-import") (part "RESISTOR"))
    )
    (comp (ref "R53")
      (value "10K")
      (footprint "eagle-import:0805")
      (libsource (lib "eagle-import") (part "RESISTOR"))
    )
    (comp (ref "R54")
      (value "4.7K")
      (footprint "eagle-import:0805")
      (libsource (lib "eagle-import") (part "RESISTOR"))
    )
    (comp (ref "R55")
      (value "4.7K")
      (footprint "eagle-import:0805")
      (libsource (lib "eagle-import") (part "RESISTOR"))
    )
    (comp (ref "R56")
      (value "2.21K")
      (footprint "eagle-import:0805")
      (libsource (lib "eagle-import") (part "RESISTOR"))
    )
    (comp (ref "R57")
      (value "1K")
      (footprint "eagle-import:0805")
      (libsource (lib "eagle-import") (part "RESISTOR"))
    )
    (comp (ref "R58")
      (value "6.8k")
      (footprint "eagle-import:0805")
      (libsource (lib "eagle-import") (part "RESISTOR"))
    )
    (comp (ref "R59")
      (value "1K")
      (footprint "eagle-import:0805")
      (libsource (lib "eagle-import") (part "RESISTOR"))
    )
    (comp (ref "R60")
      (value "10K")
      (footprint "eagle-import:0805")
      (libsource (lib "eagle-import") (part "RESISTOR"))
    )
    (comp (ref "R61")
      (value "33K")
      (footprint "eagle-import:0805")
      (libsource (lib "eagle-import") (part "RESISTOR"))
    )
    (comp (ref "R62")
      (value "2.2K")
      (footprint "eagle-import:0805")
      (libsource (lib "eagle-import") (part "RESISTOR"))
    )
    (comp (ref "R63")
      (value "2.2K")
      (footprint "eagle-import:0805")
      (libsource (lib "eagle-import") (part "RESISTOR"))
    )
    (comp (ref "R64")
      (value "4.7K")
      (footprint "eagle-import:0805")
      (libsource (lib "eagle-import") (part "RESISTOR"))
    )
    (comp (ref "R65")
      (value "4.7K")
      (footprint "eagle-import:0805")
      (libsource (lib "eagle-import") (part "RESISTOR"))
    )
    (comp (ref "R66")
      (value "1K")
      (footprint "eagle-import:0805")
      (libsource (lib "eagle-import") (part "RESISTOR"))
    )
    (comp (ref "R67")
      (value "12K")
      (footprint "eagle-import:0805")
      (libsource (lib "eagle-import") (part "RESISTOR"))
    )
    (comp (ref "R68")
      (value "2.21K")
      (footprint "eagle-import:0805")
      (libsource (lib "eagle-import") (part "RESISTOR"))
    )
    (comp (ref "R69")
      (value "4.7K")
      (footprint "eagle-import:0805")
      (libsource (lib "eagle-import") (part "RESISTOR"))
    )
    (comp (ref "R70")
      (value "4.7K")
      (footprint "eagle-import:0805")
      (libsource (lib "eagle-import") (part "RESISTOR"))
    )
    (comp (ref "R71")
      (value "4.7K")
      (footprint "eagle-import:0805")
      (libsource (lib "eagle-import") (part "RESISTOR"))
    )
    (comp (ref "R72")
      (value "1K")
      (footprint "eagle-import:0805")
      (libsource (lib "eagle-import") (part "RESISTOR"))
    )
    (comp (ref "R73")
      (value "0.27")
      (footprint "eagle-import:0805")
      (libsource (lib "eagle-import") (part "RESISTOR"))
    )
    (comp (ref "R74")
      (value "0.27")
      (footprint "eagle-import:0805")
      (libsource (lib "eagle-import") (part "RESISTOR"))
    )
    (comp (ref "R75")
      (value "1K")
      (footprint "eagle-import:0805")
      (libsource (lib "eagle-import") (part "RESISTOR"))
    )
    (comp (ref "R76")
      (value "0")
      (footprint "eagle-import:0805")
      (libsource (lib "eagle-import") (part "RESISTOR"))
    )
    (comp (ref "R77")
      (value "10K")
      (footprint "eagle-import:0805")
      (libsource (lib "eagle-import") (part "RESISTOR"))
    )
    (comp (ref "R78")
      (value "1K")
      (footprint "eagle-import:0805")
      (libsource (lib "eagle-import") (part "RESISTOR"))
    )
    (comp (ref "R79")
      (value "22")
      (footprint "eagle-import:0805")
      (libsource (lib "eagle-import") (part "RESISTOR"))
    )
    (comp (ref "R80")
      (value "1K")
      (footprint "eagle-import:0805")
      (libsource (lib "eagle-import") (part "RESISTOR"))
    )
    (comp (ref "R81")
      (value "22")
      (footprint "eagle-import:0805")
      (libsource (lib "eagle-import") (part "RESISTOR"))
    )
    (comp (ref "R82")
      (value "6.8k")
      (footprint "eagle-import:0805")
      (libsource (lib "eagle-import") (part "RESISTOR"))
    )
    (comp (ref "R83")
      (value "4.7K")
      (footprint "eagle-import:0805")
      (libsource (lib "eagle-import") (part "RESISTOR"))
    )
    (comp (ref "R84")
      (value "PGB1010604")
      (footprint "eagle-import:CT_CN0603")
      (libsource (lib "eagle-import") (part "VARISTORCN0603"))
    )
    (comp (ref "R85")
      (value "PGB1010604")
      (footprint "eagle-import:CT_CN0603")
      (libsource (lib "eagle-import") (part "VARISTORCN0603"))
    )
    (comp (ref "R86")
      (value "2.21K")
      (footprint "eagle-import:0805")
      (libsource (lib "eagle-import") (part "RESISTOR"))
    )
    (comp (ref "R87")
      (value "10K")
      (footprint "eagle-import:0805")
      (libsource (lib "eagle-import") (part "RESISTOR"))
    )
    (comp (ref "R88")
      (value "33K")
      (footprint "eagle-import:0805")
      (libsource (lib "eagle-import") (part "RESISTOR"))
    )
    (comp (ref "R89")
      (value "2.2K")
      (footprint "eagle-import:0805")
      (libsource (lib "eagle-import") (part "RESISTOR"))
    )
    (comp (ref "R90")
      (value "2.2K")
      (footprint "eagle-import:0805")
      (libsource (lib "eagle-import") (part "RESISTOR"))
    )
    (comp (ref "R91")
      (value "4.7K")
      (footprint "eagle-import:0805")
      (libsource (lib "eagle-import") (part "RESISTOR"))
    )
    (comp (ref "R92")
      (value "100K")
      (footprint "eagle-import:0805")
      (libsource (lib "eagle-import") (part "RESISTOR"))
    )
    (comp (ref "R93")
      (value "1K")
      (footprint "eagle-import:0805")
      (libsource (lib "eagle-import") (part "RESISTOR"))
    )
    (comp (ref "R94")
      (value "12K")
      (footprint "eagle-import:0805")
      (libsource (lib "eagle-import") (part "RESISTOR"))
    )
    (comp (ref "R95")
      (value "10K")
      (footprint "eagle-import:0805")
      (libsource (lib "eagle-import") (part "RESISTOR"))
    )
    (comp (ref "R96")
      (value "4.7K")
      (footprint "eagle-import:0805")
      (libsource (lib "eagle-import") (part "RESISTOR"))
    )
    (comp (ref "R97")
      (value "4.7K")
      (footprint "eagle-import:0805")
      (libsource (lib "eagle-import") (part "RESISTOR"))
    )
    (comp (ref "R98")
      (value "0.27")
      (footprint "eagle-import:0805")
      (libsource (lib "eagle-import") (part "RESISTOR"))
    )
    (comp (ref "R99")
      (value "0.27")
      (footprint "eagle-import:0805")
      (libsource (lib "eagle-import") (part "RESISTOR"))
    )
    (comp (ref "R100")
      (value "0")
      (footprint "eagle-import:0805")
      (libsource (lib "eagle-import") (part "RESISTOR"))
    )
    (comp (ref "R101")
      (value "10K")
      (footprint "eagle-import:0805")
      (libsource (lib "eagle-import") (part "RESISTOR"))
    )
    (comp (ref "R102")
      (value "6.8k")
      (footprint "eagle-import:0805")
      (libsource (lib "eagle-import") (part "RESISTOR"))
    )
    (comp (ref "R103")
      (value "1K")
      (footprint "eagle-import:0805")
      (libsource (lib "eagle-import") (part "RESISTOR"))
    )
    (comp (ref "R104")
      (value "2.2K")
      (footprint "eagle-import:0805")
      (libsource (lib "eagle-import") (part "RESISTOR"))
    )
    (comp (ref "R105")
      (value "1M")
      (footprint "eagle-import:0805")
      (libsource (lib "eagle-import") (part "RESISTOR"))
    )
    (comp (ref "R106")
      (value "100K")
      (footprint "eagle-import:0805")
      (libsource (lib "eagle-import") (part "RESISTOR"))
    )
    (comp (ref "R107")
      (value "10K")
      (footprint "eagle-import:0805")
      (libsource (lib "eagle-import") (part "RESISTOR"))
    )
    (comp (ref "R108")
      (value "33K")
      (footprint "eagle-import:0805")
      (libsource (lib "eagle-import") (part "RESISTOR"))
    )
    (comp (ref "R109")
      (value "2.2K")
      (footprint "eagle-import:0805")
      (libsource (lib "eagle-import") (part "RESISTOR"))
    )
    (comp (ref "R110")
      (value "2.2K")
      (footprint "eagle-import:0805")
      (libsource (lib "eagle-import") (part "RESISTOR"))
    )
    (comp (ref "R111")
      (value "4.7K")
      (footprint "eagle-import:0805")
      (libsource (lib "eagle-import") (part "RESISTOR"))
    )
    (comp (ref "R112")
      (value "1M")
      (footprint "eagle-import:0805")
      (libsource (lib "eagle-import") (part "RESISTOR"))
    )
    (comp (ref "R113")
      (value "100K")
      (footprint "eagle-import:0805")
      (libsource (lib "eagle-import") (part "RESISTOR"))
    )
    (comp (ref "R114")
      (value "4.7K")
      (footprint "eagle-import:0805")
      (libsource (lib "eagle-import") (part "RESISTOR"))
    )
    (comp (ref "R115")
      (value "1M")
      (footprint "eagle-import:0805")
      (libsource (lib "eagle-import") (part "RESISTOR"))
    )
    (comp (ref "R116")
      (value "100K")
      (footprint "eagle-import:0805")
      (libsource (lib "eagle-import") (part "RESISTOR"))
    )
    (comp (ref "R117")
      (value "4.7K")
      (footprint "eagle-import:0805")
      (libsource (lib "eagle-import") (part "RESISTOR"))
    )
    (comp (ref "R118")
      (value "1K")
      (footprint "eagle-import:0805")
      (libsource (lib "eagle-import") (part "RESISTOR"))
    )
    (comp (ref "R119")
      (value "1K")
      (footprint "eagle-import:0805")
      (libsource (lib "eagle-import") (part "RESISTOR"))
    )
    (comp (ref "R120")
      (value "1K")
      (footprint "eagle-import:0805")
      (libsource (lib "eagle-import") (part "RESISTOR"))
    )
    (comp (ref "R121")
      (value "1K")
      (footprint "eagle-import:0805")
      (libsource (lib "eagle-import") (part "RESISTOR"))
    )
    (comp (ref "R122")
      (value "12K")
      (footprint "eagle-import:0805")
      (libsource (lib "eagle-import") (part "RESISTOR"))
    )
    (comp (ref "R123")
      (value "4.7K")
      (footprint "eagle-import:0805")
      (libsource (lib "eagle-import") (part "RESISTOR"))
    )
    (comp (ref "R124")
      (value "4.7K")
      (footprint "eagle-import:0805")
      (libsource (lib "eagle-import") (part "RESISTOR"))
    )
    (comp (ref "R125")
      (value "0.27")
      (footprint "eagle-import:0805")
      (libsource (lib "eagle-import") (part "RESISTOR"))
    )
    (comp (ref "R126")
      (value "0.27")
      (footprint "eagle-import:0805")
      (libsource (lib "eagle-import") (part "RESISTOR"))
    )
    (comp (ref "R127")
      (value "0")
      (footprint "eagle-import:0805")
      (libsource (lib "eagle-import") (part "RESISTOR"))
    )
    (comp (ref "R128")
      (value "10K")
      (footprint "eagle-import:0805")
      (libsource (lib "eagle-import") (part "RESISTOR"))
    )
    (comp (ref "R129")
      (value "10K")
      (footprint "eagle-import:0805")
      (libsource (lib "eagle-import") (part "RESISTOR"))
    )
    (comp (ref "R130")
      (value "0")
      (footprint "eagle-import:0805")
      (libsource (lib "eagle-import") (part "RESISTOR"))
    )
    (comp (ref "R131")
      (value "0")
      (footprint "eagle-import:0805")
      (libsource (lib "eagle-import") (part "RESISTOR"))
    )
    (comp (ref "R132")
      (value "10K")
      (footprint "eagle-import:0805")
      (libsource (lib "eagle-import") (part "RESISTOR"))
    )
    (comp (ref "R133")
      (value "4.7K")
      (footprint "eagle-import:0805")
      (libsource (lib "eagle-import") (part "RESISTOR"))
    )
    (comp (ref "R134")
      (value "4.7K")
      (footprint "eagle-import:0805")
      (libsource (lib "eagle-import") (part "RESISTOR"))
    )
    (comp (ref "R135")
      (value "0")
      (footprint "eagle-import:0805")
      (libsource (lib "eagle-import") (part "RESISTOR"))
    )
    (comp (ref "R136")
      (value "0")
      (footprint "eagle-import:0805")
      (libsource (lib "eagle-import") (part "RESISTOR"))
    )
    (comp (ref "R137")
      (value "0")
      (footprint "eagle-import:0805")
      (libsource (lib "eagle-import") (part "RESISTOR"))
    )
    (comp (ref "R138")
      (value "0")
      (footprint "eagle-import:0805")
      (libsource (lib "eagle-import") (part "RESISTOR"))
    )
    (comp (ref "R139")
      (value "0")
      (footprint "eagle-import:0805")
      (libsource (lib "eagle-import") (part "RESISTOR"))
    )
    (comp (ref "RESET")
      (value "Push-button")
      (footprint "eagle-import:B3F-10XX")
      (libsource (lib "eagle-import") (part "10-XX"))
    )
    (comp (ref "RGB+")
      (value "SCREWTERMINAL-3.5MM-4")
      (footprint "eagle-import:SCREWTERMINAL-3.5MM-4")
      (libsource (lib "eagle-import") (part "M04SCREW"))
    )
    (comp (ref "RX")
      (value "YELLOW")
      (footprint "eagle-import:LED-0805")
      (libsource (lib "eagle-import") (part "LED0805"))
    )
    (comp (ref "SPEAKER")
      (value "F/QMB")
      (footprint "eagle-import:F_QMB")
      (libsource (lib "eagle-import") (part "F/QMB"))
    )
    (comp (ref "SV2")
      (value "26 Pin - Male")
      (footprint "eagle-import:ML26")
      (libsource (lib "eagle-import") (part "ML26"))
    )
    (comp (ref "T1")
      (value "MAX6675")
      (footprint "eagle-import:SO08")
      (libsource (lib "eagle-import") (part "MAX6675"))
    )
    (comp (ref "T2")
      (value "MAX6675")
      (footprint "eagle-import:SO08")
      (libsource (lib "eagle-import") (part "MAX6675"))
    )
    (comp (ref "TX")
      (value "YELLOW")
      (footprint "eagle-import:LED-0805")
      (libsource (lib "eagle-import") (part "LED0805"))
    )
    (comp (ref "X-MAX")
      (value "SCREWTERMINAL-3.5MM-2")
      (footprint "eagle-import:SCREWTERMINAL-3.5MM-2")
      (libsource (lib "eagle-import") (part "M023.5MM"))
    )
    (comp (ref "X8")
      (value "USB B-TH")
      (footprint "eagle-import:PN61729")
      (libsource (lib "eagle-import") (part "PN61729"))
    )
    (comp (ref "Y-MAX")
      (value "SCREWTERMINAL-3.5MM-2")
      (footprint "eagle-import:SCREWTERMINAL-3.5MM-2")
      (libsource (lib "eagle-import") (part "M023.5MM"))
    )
    (comp (ref "Y1")
      (value "16MHz")
      (footprint "eagle-import:HC49_S")
      (libsource (lib "eagle-import") (part "CRYTALHC49S"))
    )
    (comp (ref "Y2")
      (value "16MHz")
      (footprint "eagle-import:HC49_S")
      (libsource (lib "eagle-import") (part "CRYTALHC49S"))
    )
    (comp (ref "Z-MAX")
      (value "SCREWTERMINAL-3.5MM-2")
      (footprint "eagle-import:SCREWTERMINAL-3.5MM-2")
      (libsource (lib "eagle-import") (part "M023.5MM"))
    )
    (comp (ref "Z-MIN")
      (value "SCREWTERMINAL-3.5MM-2")
      (footprint "eagle-import:SCREWTERMINAL-3.5MM-2")
      (libsource (lib "eagle-import") (part "M023.5MM"))
    )
  )
  (nets
    (net (code "1") (name "+5V") (class "Default")
      (node (ref "A1") (pin "P16") (pinfunction "VDD_P16") (pintype "bidirectional"))
      (node (ref "A2") (pin "P16") (pinfunction "VDD_P16") (pintype "bidirectional"))
      (node (ref "A3") (pin "P16") (pinfunction "VDD_P16") (pintype "bidirectional"))
      (node (ref "A4") (pin "P16") (pinfunction "VDD_P16") (pintype "bidirectional"))
      (node (ref "A5") (pin "P16") (pinfunction "VDD_P16") (pintype "bidirectional"))
      (node (ref "C12") (pin "1") (pinfunction "1_1") (pintype "passive"))
      (node (ref "C21") (pin "2") (pinfunction "2_2") (pintype "passive"))
      (node (ref "C23") (pin "2") (pinfunction "2_2") (pintype "passive"))
      (node (ref "C24") (pin "1") (pinfunction "1_1") (pintype "passive"))
      (node (ref "C25") (pin "1") (pinfunction "1_1") (pintype "passive"))
      (node (ref "C28") (pin "1") (pinfunction "1_1") (pintype "passive"))
      (node (ref "C29") (pin "1") (pinfunction "1_1") (pintype "passive"))
      (node (ref "C33") (pin "1") (pinfunction "1_1") (pintype "passive"))
      (node (ref "C34") (pin "2") (pinfunction "2_2") (pintype "passive"))
      (node (ref "C38") (pin "2") (pinfunction "2_2") (pintype "passive"))
      (node (ref "C40") (pin "2") (pinfunction "2_2") (pintype "passive"))
      (node (ref "C51") (pin "2") (pinfunction "2_2") (pintype "passive"))
      (node (ref "C53") (pin "2") (pinfunction "2_2") (pintype "passive"))
      (node (ref "C6") (pin "2") (pinfunction "2_2") (pintype "passive"))
      (node (ref "C60") (pin "2") (pinfunction "2_2") (pintype "passive"))
      (node (ref "C62") (pin "2") (pinfunction "2_2") (pintype "passive"))
      (node (ref "C68") (pin "2") (pinfunction "2_2") (pintype "passive"))
      (node (ref "C69") (pin "2") (pinfunction "2_2") (pintype "passive"))
      (node (ref "C8") (pin "2") (pinfunction "2_2") (pintype "passive"))
      (node (ref "HBP-T") (pin "1") (pinfunction "1_1") (pintype "passive"))
      (node (ref "IC1") (pin "10") (pinfunction "VCC_10") (pintype "power_in"))
      (node (ref "IC1") (pin "100") (pinfunction "AVCC_100") (pintype "power_in"))
      (node (ref "IC1") (pin "31") (pinfunction "VCC1_31") (pintype "power_in"))
      (node (ref "IC1") (pin "60") (pinfunction "(A15)PC7_60") (pintype "bidirectional"))
      (node (ref "IC1") (pin "61") (pinfunction "VCC2_61") (pintype "power_in"))
      (node (ref "IC1") (pin "80") (pinfunction "VCC3_80") (pintype "power_in"))
      (node (ref "IC2") (pin "32") (pinfunction "AVCC_32") (pintype "power_in"))
      (node (ref "IC2") (pin "4") (pinfunction "VCC_4") (pintype "power_in"))
      (node (ref "LC1") (pin "1") (pinfunction "VDD_1") (pintype "bidirectional"))
      (node (ref "LC2") (pin "1") (pinfunction "VDD_1") (pintype "bidirectional"))
      (node (ref "LC3") (pin "1") (pinfunction "VDD_1") (pintype "bidirectional"))
      (node (ref "LC4") (pin "1") (pinfunction "VDD_1") (pintype "bidirectional"))
      (node (ref "LC5") (pin "8") (pinfunction "VCC_8") (pintype "bidirectional"))
      (node (ref "LC6") (pin "8") (pinfunction "VDD_8") (pintype "bidirectional"))
      (node (ref "LC7") (pin "1") (pinfunction "VDD_1") (pintype "bidirectional"))
      (node (ref "P1") (pin "3") (pinfunction "VO_3") (pintype "bidirectional"))
      (node (ref "PIN1") (pin "2") (pinfunction "2_2") (pintype "passive"))
      (node (ref "PIN2") (pin "2") (pinfunction "2_2") (pintype "passive"))
      (node (ref "R1") (pin "2") (pinfunction "2_2") (pintype "passive"))
      (node (ref "R101") (pin "2") (pinfunction "2_2") (pintype "passive"))
      (node (ref "R103") (pin "1") (pinfunction "1_1") (pintype "passive"))
      (node (ref "R105") (pin "1") (pinfunction "1_1") (pintype "passive"))
      (node (ref "R107") (pin "2") (pinfunction "2_2") (pintype "passive"))
      (node (ref "R108") (pin "1") (pinfunction "1_1") (pintype "passive"))
      (node (ref "R109") (pin "1") (pinfunction "1_1") (pintype "passive"))
      (node (ref "R11") (pin "2") (pinfunction "2_2") (pintype "passive"))
      (node (ref "R110") (pin "1") (pinfunction "1_1") (pintype "passive"))
      (node (ref "R111") (pin "2") (pinfunction "2_2") (pintype "passive"))
      (node (ref "R112") (pin "1") (pinfunction "1_1") (pintype "passive"))
      (node (ref "R114") (pin "2") (pinfunction "2_2") (pintype "passive"))
      (node (ref "R115") (pin "1") (pinfunction "1_1") (pintype "passive"))
      (node (ref "R117") (pin "2") (pinfunction "2_2") (pintype "passive"))
      (node (ref "R12") (pin "2") (pinfunction "2_2") (pintype "passive"))
      (node (ref "R128") (pin "2") (pinfunction "2_2") (pintype "passive"))
      (node (ref "R129") (pin "2") (pinfunction "2_2") (pintype "passive"))
      (node (ref "R13") (pin "1") (pinfunction "1_1") (pintype "passive"))
      (node (ref "R132") (pin "2") (pinfunction "2_2") (pintype "passive"))
      (node (ref "R14") (pin "1") (pinfunction "1_1") (pintype "passive"))
      (node (ref "R15") (pin "1") (pinfunction "1_1") (pintype "passive"))
      (node (ref "R16") (pin "2") (pinfunction "2_2") (pintype "passive"))
      (node (ref "R18") (pin "2") (pinfunction "2_2") (pintype "passive"))
      (node (ref "R24") (pin "2") (pinfunction "2_2") (pintype "passive"))
      (node (ref "R28") (pin "2") (pinfunction "2_2") (pintype "passive"))
      (node (ref "R3") (pin "2") (pinfunction "2_2") (pintype "passive"))
      (node (ref "R30") (pin "2") (pinfunction "2_2") (pintype "passive"))
      (node (ref "R31") (pin "2") (pinfunction "2_2") (pintype "passive"))
      (node (ref "R35") (pin "2") (pinfunction "2_2") (pintype "passive"))
      (node (ref "R36") (pin "1") (pinfunction "1_1") (pintype "passive"))
      (node (ref "R37") (pin "1") (pinfunction "1_1") (pintype "passive"))
      (node (ref "R38") (pin "1") (pinfunction "1_1") (pintype "passive"))
      (node (ref "R39") (pin "2") (pinfunction "2_2") (pintype "passive"))
      (node (ref "R42") (pin "2") (pinfunction "2_2") (pintype "passive"))
      (node (ref "R43") (pin "2") (pinfunction "2_2") (pintype "passive"))
      (node (ref "R5") (pin "2") (pinfunction "2_2") (pintype "passive"))
      (node (ref "R53") (pin "2") (pinfunction "2_2") (pintype "passive"))
      (node (ref "R55") (pin "2") (pinfunction "2_2") (pintype "passive"))
      (node (ref "R57") (pin "2") (pinfunction "2_2") (pintype "passive"))
      (node (ref "R60") (pin "2") (pinfunction "2_2") (pintype "passive"))
      (node (ref "R61") (pin "1") (pinfunction "1_1") (pintype "passive"))
      (node (ref "R62") (pin "1") (pinfunction "1_1") (pintype "passive"))
      (node (ref "R63") (pin "1") (pinfunction "1_1") (pintype "passive"))
      (node (ref "R64") (pin "2") (pinfunction "2_2") (pintype "passive"))
      (node (ref "R71") (pin "2") (pinfunction "2_2") (pintype "passive"))
      (node (ref "R72") (pin "2") (pinfunction "2_2") (pintype "passive"))
      (node (ref "R77") (pin "2") (pinfunction "2_2") (pintype "passive"))
      (node (ref "R78") (pin "1") (pinfunction "1_1") (pintype "passive"))
      (node (ref "R80") (pin "1") (pinfunction "1_1") (pintype "passive"))
      (node (ref "R87") (pin "2") (pinfunction "2_2") (pintype "passive"))
      (node (ref "R88") (pin "1") (pinfunction "1_1") (pintype "passive"))
      (node (ref "R89") (pin "1") (pinfunction "1_1") (pintype "passive"))
      (node (ref "R90") (pin "1") (pinfunction "1_1") (pintype "passive"))
      (node (ref "R91") (pin "2") (pinfunction "2_2") (pintype "passive"))
      (node (ref "R92") (pin "2") (pinfunction "2_2") (pintype "passive"))
      (node (ref "R95") (pin "2") (pinfunction "2_2") (pintype "passive"))
      (node (ref "SV2") (pin "17") (pinfunction "17_17") (pintype "passive"))
      (node (ref "SV2") (pin "23") (pinfunction "23_23") (pintype "passive"))
      (node (ref "SV2") (pin "25") (pinfunction "25_25") (pintype "passive"))
      (node (ref "SV2") (pin "26") (pinfunction "26_26") (pintype "passive"))
      (node (ref "T1") (pin "4") (pinfunction "VCC_4") (pintype "power_in"))
      (node (ref "T2") (pin "4") (pinfunction "VCC_4") (pintype "power_in"))
    )
    (net (code "2") (name "+24V") (class "Default")
      (node (ref "A1") (pin "P03") (pinfunction "VBB2_P03") (pintype "bidirectional"))
      (node (ref "A1") (pin "P22") (pinfunction "VBB1_P22") (pintype "bidirectional"))
      (node (ref "A2") (pin "P03") (pinfunction "VBB2_P03") (pintype "bidirectional"))
      (node (ref "A2") (pin "P22") (pinfunction "VBB1_P22") (pintype "bidirectional"))
      (node (ref "A3") (pin "P03") (pinfunction "VBB2_P03") (pintype "bidirectional"))
      (node (ref "A3") (pin "P22") (pinfunction "VBB1_P22") (pintype "bidirectional"))
      (node (ref "A4") (pin "P03") (pinfunction "VBB2_P03") (pintype "bidirectional"))
      (node (ref "A4") (pin "P22") (pinfunction "VBB1_P22") (pintype "bidirectional"))
      (node (ref "A5") (pin "P03") (pinfunction "VBB2_P03") (pintype "bidirectional"))
      (node (ref "A5") (pin "P22") (pinfunction "VBB1_P22") (pintype "bidirectional"))
      (node (ref "C10") (pin "1") (pinfunction "1_1") (pintype "passive"))
      (node (ref "C13") (pin "1") (pinfunction "1_1") (pintype "passive"))
      (node (ref "C15") (pin "+") (pinfunction "+_+") (pintype "passive"))
      (node (ref "C18") (pin "1") (pinfunction "1_1") (pintype "passive"))
      (node (ref "C19") (pin "2") (pinfunction "2_2") (pintype "passive"))
      (node (ref "C22") (pin "2") (pinfunction "2_2") (pintype "passive"))
      (node (ref "C3") (pin "1") (pinfunction "1_1") (pintype "passive"))
      (node (ref "C30") (pin "+") (pinfunction "+_+") (pintype "passive"))
      (node (ref "C36") (pin "1") (pinfunction "1_1") (pintype "passive"))
      (node (ref "C37") (pin "2") (pinfunction "2_2") (pintype "passive"))
      (node (ref "C39") (pin "2") (pinfunction "2_2") (pintype "passive"))
      (node (ref "C43") (pin "+") (pinfunction "+_+") (pintype "passive"))
      (node (ref "C49") (pin "1") (pinfunction "1_1") (pintype "passive"))
      (node (ref "C5") (pin "2") (pinfunction "2_2") (pintype "passive"))
      (node (ref "C50") (pin "2") (pinfunction "2_2") (pintype "passive"))
      (node (ref "C52") (pin "2") (pinfunction "2_2") (pintype "passive"))
      (node (ref "C55") (pin "+") (pinfunction "+_+") (pintype "passive"))
      (node (ref "C58") (pin "1") (pinfunction "1_1") (pintype "passive"))
      (node (ref "C59") (pin "2") (pinfunction "2_2") (pintype "passive"))
      (node (ref "C61") (pin "2") (pinfunction "2_2") (pintype "passive"))
      (node (ref "C64") (pin "+") (pinfunction "+_+") (pintype "passive"))
      (node (ref "C7") (pin "2") (pinfunction "2_2") (pintype "passive"))
      (node (ref "C9") (pin "+") (pinfunction "+_+") (pintype "passive"))
      (node (ref "FAN-1") (pin "1") (pinfunction "1_1") (pintype "passive"))
      (node (ref "FAN-2") (pin "1") (pinfunction "1_1") (pintype "passive"))
      (node (ref "FUSE_HOLDER") (pin "1") (pinfunction "1_1") (pintype "bidirectional"))
      (node (ref "HBP") (pin "1") (pinfunction "1_1") (pintype "passive"))
      (node (ref "L-COOL") (pin "1") (pinfunction "1_1") (pintype "passive"))
      (node (ref "L-HEAT") (pin "1") (pinfunction "1_1") (pintype "passive"))
      (node (ref "P1") (pin "1") (pinfunction "VI_1") (pintype "input"))
      (node (ref "R-COOL") (pin "1") (pinfunction "1_1") (pintype "passive"))
      (node (ref "R-HEAT") (pin "1") (pinfunction "1_1") (pintype "passive"))
      (node (ref "R102") (pin "2") (pinfunction "2_2") (pintype "passive"))
      (node (ref "R104") (pin "2") (pinfunction "2_2") (pintype "passive"))
      (node (ref "R17") (pin "2") (pinfunction "2_2") (pintype "passive"))
      (node (ref "R32") (pin "2") (pinfunction "2_2") (pintype "passive"))
      (node (ref "R34") (pin "2") (pinfunction "2_2") (pintype "passive"))
      (node (ref "R40") (pin "2") (pinfunction "2_2") (pintype "passive"))
      (node (ref "R44") (pin "2") (pinfunction "2_2") (pintype "passive"))
      (node (ref "R56") (pin "2") (pinfunction "2_2") (pintype "passive"))
      (node (ref "R58") (pin "2") (pinfunction "2_2") (pintype "passive"))
      (node (ref "R6") (pin "2") (pinfunction "2_2") (pintype "passive"))
      (node (ref "R68") (pin "2") (pinfunction "2_2") (pintype "passive"))
      (node (ref "R8") (pin "2") (pinfunction "2_2") (pintype "passive"))
      (node (ref "R82") (pin "2") (pinfunction "2_2") (pintype "passive"))
      (node (ref "R86") (pin "2") (pinfunction "2_2") (pintype "passive"))
      (node (ref "R9") (pin "2") (pinfunction "2_2") (pintype "passive"))
      (node (ref "RGB+") (pin "4") (pinfunction "4_4") (pintype "passive"))
    )
    (net (code "3") (name "8U2-MISO") (class "Default")
      (node (ref "IC2") (pin "17") (pinfunction "(PD0/MISO/PCINT3)PB3_17") (pintype "bidirectional"))
      (node (ref "PIN2") (pin "1") (pinfunction "1_1") (pintype "passive"))
    )
    (net (code "4") (name "8U2-MOSI") (class "Default")
      (node (ref "IC2") (pin "16") (pinfunction "(PDI/MOSI/PCINT2)PB2_16") (pintype "bidirectional"))
      (node (ref "PIN2") (pin "4") (pinfunction "4_4") (pintype "passive"))
    )
    (net (code "5") (name "8U2-RESET") (class "Default")
      (node (ref "IC2") (pin "24") (pinfunction "RESET(PC1/DW)_24") (pintype "input"))
      (node (ref "PIN2") (pin "5") (pinfunction "5_5") (pintype "passive"))
      (node (ref "R95") (pin "1") (pinfunction "1_1") (pintype "passive"))
    )
    (net (code "6") (name "8U2-SCK") (class "Default")
      (node (ref "IC2") (pin "15") (pinfunction "(SCLK/PCINT1)PB1_15") (pintype "bidirectional"))
      (node (ref "PIN2") (pin "3") (pinfunction "3_3") (pintype "passive"))
    )
    (net (code "7") (name "2560-EX1") (class "Default")
      (node (ref "D-1") (pin "A") (pinfunction "A_A") (pintype "passive"))
      (node (ref "IC1") (pin "54") (pinfunction "(A9)PC1_54") (pintype "bidirectional"))
    )
    (net (code "8") (name "2560-EX2") (class "Default")
      (node (ref "D-2") (pin "A") (pinfunction "A_A") (pintype "passive"))
      (node (ref "IC1") (pin "53") (pinfunction "(A8)PC0_53") (pintype "bidirectional"))
    )
    (net (code "9") (name "2560-EX3") (class "Default")
      (node (ref "D-3") (pin "A") (pinfunction "A_A") (pintype "passive"))
      (node (ref "IC1") (pin "52") (pinfunction "(RD)PG1_52") (pintype "bidirectional"))
    )
    (net (code "10") (name "2560-MISO") (class "Default")
      (node (ref "IC1") (pin "22") (pinfunction "(MISO/PCINT3)PB3_22") (pintype "bidirectional"))
      (node (ref "PIN1") (pin "1") (pinfunction "1_1") (pintype "passive"))
      (node (ref "SV2") (pin "8") (pinfunction "8_8") (pintype "passive"))
    )
    (net (code "11") (name "A-DIR") (class "Default")
      (node (ref "A1") (pin "P20") (pinfunction "DIR_P20") (pintype "bidirectional"))
      (node (ref "IC1") (pin "72") (pinfunction "(AD6)PA6_72") (pintype "bidirectional"))
    )
    (net (code "12") (name "A-EN") (class "Default")
      (node (ref "A1") (pin "P05") (pinfunction "ENABLE_P05") (pintype "bidirectional"))
      (node (ref "IC1") (pin "70") (pinfunction "(ALE)PG2_70") (pintype "bidirectional"))
      (node (ref "R16") (pin "1") (pinfunction "1_1") (pintype "passive"))
    )
    (net (code "13") (name "A-FAN") (class "Default")
      (node (ref "IC1") (pin "16") (pinfunction "PH4(OC4B)_16") (pintype "bidirectional"))
      (node (ref "M3") (pin "4") (pinfunction "G_4") (pintype "passive"))
      (node (ref "R33") (pin "2") (pinfunction "2_2") (pintype "passive"))
    )
    (net (code "14") (name "A-HEAT") (class "Default")
      (node (ref "IC1") (pin "15") (pinfunction "PH3(OC4A)_15") (pintype "bidirectional"))
      (node (ref "M4") (pin "4") (pinfunction "G_4") (pintype "passive"))
      (node (ref "R49") (pin "2") (pinfunction "2_2") (pintype "passive"))
    )
    (net (code "15") (name "A-POT") (class "Default")
      (node (ref "IC1") (pin "69") (pinfunction "PJ6(PCINT15)_69") (pintype "bidirectional"))
      (node (ref "R21") (pin "2") (pinfunction "2_2") (pintype "passive"))
    )
    (net (code "16") (name "A-PWR-CHECK") (class "Default")
      (node (ref "IC1") (pin "14") (pinfunction "PH2(XCK2)_14") (pintype "bidirectional"))
      (node (ref "R40") (pin "1") (pinfunction "1_1") (pintype "passive"))
      (node (ref "R41") (pin "2") (pinfunction "2_2") (pintype "passive"))
    )
    (net (code "17") (name "A-STEP") (class "Default")
      (node (ref "A1") (pin "P17") (pinfunction "STEP_P17") (pintype "bidirectional"))
      (node (ref "IC1") (pin "71") (pinfunction "(AD7)PA7_71") (pintype "bidirectional"))
    )
    (net (code "18") (name "ACTIVE_FAN") (class "Default")
      (node (ref "IC1") (pin "40") (pinfunction "PL5(OC5C)_40") (pintype "bidirectional"))
      (node (ref "M6") (pin "4") (pinfunction "G_4") (pintype "passive"))
      (node (ref "R65") (pin "2") (pinfunction "2_2") (pintype "passive"))
    )
    (net (code "19") (name "AREF") (class "Default")
      (node (ref "C27") (pin "1") (pinfunction "1_1") (pintype "passive"))
      (node (ref "IC1") (pin "98") (pinfunction "AREF_98") (pintype "bidirectional"))
    )
    (net (code "20") (name "B-DIR") (class "Default")
      (node (ref "A2") (pin "P20") (pinfunction "DIR_P20") (pintype "bidirectional"))
      (node (ref "IC1") (pin "76") (pinfunction "(AD2)PA2_76") (pintype "bidirectional"))
    )
    (net (code "21") (name "B-EN") (class "Default")
      (node (ref "A2") (pin "P05") (pinfunction "ENABLE_P05") (pintype "bidirectional"))
      (node (ref "IC1") (pin "74") (pinfunction "(AD4)PA4_74") (pintype "bidirectional"))
      (node (ref "R39") (pin "1") (pinfunction "1_1") (pintype "passive"))
    )
    (net (code "22") (name "B-FAN") (class "Default")
      (node (ref "IC1") (pin "25") (pinfunction "(OC1B/PCINT6)PB6_25") (pintype "bidirectional"))
      (node (ref "M1") (pin "4") (pinfunction "G_4") (pintype "passive"))
      (node (ref "R7") (pin "2") (pinfunction "2_2") (pintype "passive"))
    )
    (net (code "23") (name "B-HEAT") (class "Default")
      (node (ref "IC1") (pin "24") (pinfunction "(OC1A/PCINT5)PB5_24") (pintype "bidirectional"))
      (node (ref "M2") (pin "4") (pinfunction "G_4") (pintype "passive"))
      (node (ref "R19") (pin "2") (pinfunction "2_2") (pintype "passive"))
    )
    (net (code "24") (name "B-POT") (class "Default")
      (node (ref "IC1") (pin "73") (pinfunction "(AD5)PA5_73") (pintype "bidirectional"))
      (node (ref "R45") (pin "2") (pinfunction "2_2") (pintype "passive"))
    )
    (net (code "25") (name "B-PWR-CHECK") (class "Default")
      (node (ref "IC1") (pin "23") (pinfunction "(OC2A/PCINT4)PB4_23") (pintype "bidirectional"))
      (node (ref "R10") (pin "2") (pinfunction "2_2") (pintype "passive"))
      (node (ref "R9") (pin "1") (pinfunction "1_1") (pintype "passive"))
    )
    (net (code "26") (name "B-STEP") (class "Default")
      (node (ref "A2") (pin "P17") (pinfunction "STEP_P17") (pintype "bidirectional"))
      (node (ref "IC1") (pin "75") (pinfunction "(AD3)PA3_75") (pintype "bidirectional"))
    )
    (net (code "27") (name "BUZZ") (class "Default")
      (node (ref "IC1") (pin "1") (pinfunction "(OC0B)PG5_1") (pintype "bidirectional"))
      (node (ref "SPEAKER") (pin "+") (pinfunction "-_+") (pintype "passive"))
    )
    (net (code "28") (name "CENTRE") (class "Default")
      (node (ref "IC1") (pin "63") (pinfunction "PJ0(RXD3/PCINT9)_63") (pintype "bidirectional"))
      (node (ref "SV2") (pin "20") (pinfunction "20_20") (pintype "passive"))
    )
    (net (code "29") (name "DATA+") (class "Default")
      (node (ref "R81") (pin "2") (pinfunction "2_2") (pintype "passive"))
      (node (ref "R85") (pin "2") (pinfunction "2_2") (pintype "passive"))
      (node (ref "X8") (pin "3") (pinfunction "3_3") (pintype "bidirectional"))
    )
    (net (code "30") (name "DATA-") (class "Default")
      (node (ref "R79") (pin "2") (pinfunction "2_2") (pintype "passive"))
      (node (ref "R84") (pin "2") (pinfunction "2_2") (pintype "passive"))
      (node (ref "X8") (pin "2") (pinfunction "2_2") (pintype "bidirectional"))
    )
    (net (code "31") (name "DOWN") (class "Default")
      (node (ref "IC1") (pin "66") (pinfunction "PJ3(PCINT12)_66") (pintype "bidirectional"))
      (node (ref "SV2") (pin "21") (pinfunction "21_21") (pintype "passive"))
    )
    (net (code "32") (name "GLED") (class "Default")
      (node (ref "IC1") (pin "59") (pinfunction "(A14)PC6_59") (pintype "bidirectional"))
      (node (ref "SV2") (pin "18") (pinfunction "18_18") (pintype "passive"))
    )
    (net (code "33") (name "GND") (class "Default")
      (node (ref "-24V+") (pin "2") (pinfunction "1_2") (pintype "passive"))
      (node (ref "24V") (pin "C") (pinfunction "C_C") (pintype "passive"))
      (node (ref "5V") (pin "C") (pinfunction "C_C") (pintype "passive"))
      (node (ref "A1") (pin "EPAD") (pinfunction "PAD_EPAD") (pintype "bidirectional"))
      (node (ref "A1") (pin "P06") (pinfunction "GND1_P06") (pintype "bidirectional"))
      (node (ref "A1") (pin "P19") (pinfunction "GND2_P19") (pintype "bidirectional"))
      (node (ref "A2") (pin "EPAD") (pinfunction "PAD_EPAD") (pintype "bidirectional"))
      (node (ref "A2") (pin "P06") (pinfunction "GND1_P06") (pintype "bidirectional"))
      (node (ref "A2") (pin "P19") (pinfunction "GND2_P19") (pintype "bidirectional"))
      (node (ref "A3") (pin "EPAD") (pinfunction "PAD_EPAD") (pintype "bidirectional"))
      (node (ref "A3") (pin "P06") (pinfunction "GND1_P06") (pintype "bidirectional"))
      (node (ref "A3") (pin "P19") (pinfunction "GND2_P19") (pintype "bidirectional"))
      (node (ref "A4") (pin "EPAD") (pinfunction "PAD_EPAD") (pintype "bidirectional"))
      (node (ref "A4") (pin "P06") (pinfunction "GND1_P06") (pintype "bidirectional"))
      (node (ref "A4") (pin "P19") (pinfunction "GND2_P19") (pintype "bidirectional"))
      (node (ref "A5") (pin "EPAD") (pinfunction "PAD_EPAD") (pintype "bidirectional"))
      (node (ref "A5") (pin "P06") (pinfunction "GND1_P06") (pintype "bidirectional"))
      (node (ref "A5") (pin "P19") (pinfunction "GND2_P19") (pintype "bidirectional"))
      (node (ref "C1") (pin "1") (pinfunction "1_1") (pintype "passive"))
      (node (ref "C10") (pin "2") (pinfunction "2_2") (pintype "passive"))
      (node (ref "C11") (pin "1") (pinfunction "1_1") (pintype "passive"))
      (node (ref "C12") (pin "2") (pinfunction "2_2") (pintype "passive"))
      (node (ref "C13") (pin "2") (pinfunction "2_2") (pintype "passive"))
      (node (ref "C14") (pin "2") (pinfunction "2_2") (pintype "passive"))
      (node (ref "C15") (pin "-") (pinfunction "-_-") (pintype "passive"))
      (node (ref "C16") (pin "2") (pinfunction "2_2") (pintype "passive"))
      (node (ref "C19") (pin "1") (pinfunction "1_1") (pintype "passive"))
      (node (ref "C20") (pin "2") (pinfunction "2_2") (pintype "passive"))
      (node (ref "C21") (pin "1") (pinfunction "1_1") (pintype "passive"))
      (node (ref "C22") (pin "1") (pinfunction "1_1") (pintype "passive"))
      (node (ref "C23") (pin "1") (pinfunction "1_1") (pintype "passive"))
      (node (ref "C24") (pin "2") (pinfunction "2_2") (pintype "passive"))
      (node (ref "C25") (pin "2") (pinfunction "2_2") (pintype "passive"))
      (node (ref "C26") (pin "1") (pinfunction "1_1") (pintype "passive"))
      (node (ref "C27") (pin "2") (pinfunction "2_2") (pintype "passive"))
      (node (ref "C28") (pin "2") (pinfunction "2_2") (pintype "passive"))
      (node (ref "C29") (pin "2") (pinfunction "2_2") (pintype "passive"))
      (node (ref "C30") (pin "-") (pinfunction "-_-") (pintype "passive"))
      (node (ref "C31") (pin "2") (pinfunction "2_2") (pintype "passive"))
      (node (ref "C32") (pin "2") (pinfunction "2_2") (pintype "passive"))
      (node (ref "C33") (pin "2") (pinfunction "2_2") (pintype "passive"))
      (node (ref "C34") (pin "1") (pinfunction "1_1") (pintype "passive"))
      (node (ref "C37") (pin "1") (pinfunction "1_1") (pintype "passive"))
      (node (ref "C38") (pin "1") (pinfunction "1_1") (pintype "passive"))
      (node (ref "C39") (pin "1") (pinfunction "1_1") (pintype "passive"))
      (node (ref "C4") (pin "2") (pinfunction "2_2") (pintype "passive"))
      (node (ref "C40") (pin "1") (pinfunction "1_1") (pintype "passive"))
      (node (ref "C41") (pin "2") (pinfunction "2_2") (pintype "passive"))
      (node (ref "C42") (pin "1") (pinfunction "1_1") (pintype "passive"))
      (node (ref "C43") (pin "-") (pinfunction "-_-") (pintype "passive"))
      (node (ref "C44") (pin "2") (pinfunction "2_2") (pintype "passive"))
      (node (ref "C45") (pin "1") (pinfunction "1_1") (pintype "passive"))
      (node (ref "C47") (pin "1") (pinfunction "1_1") (pintype "passive"))
      (node (ref "C5") (pin "1") (pinfunction "1_1") (pintype "passive"))
      (node (ref "C50") (pin "1") (pinfunction "1_1") (pintype "passive"))
      (node (ref "C51") (pin "1") (pinfunction "1_1") (pintype "passive"))
      (node (ref "C52") (pin "1") (pinfunction "1_1") (pintype "passive"))
      (node (ref "C53") (pin "1") (pinfunction "1_1") (pintype "passive"))
      (node (ref "C54") (pin "1") (pinfunction "1_1") (pintype "passive"))
      (node (ref "C55") (pin "-") (pinfunction "-_-") (pintype "passive"))
      (node (ref "C56") (pin "2") (pinfunction "2_2") (pintype "passive"))
      (node (ref "C59") (pin "1") (pinfunction "1_1") (pintype "passive"))
      (node (ref "C6") (pin "1") (pinfunction "1_1") (pintype "passive"))
      (node (ref "C60") (pin "1") (pinfunction "1_1") (pintype "passive"))
      (node (ref "C61") (pin "1") (pinfunction "1_1") (pintype "passive"))
      (node (ref "C62") (pin "1") (pinfunction "1_1") (pintype "passive"))
      (node (ref "C63") (pin "1") (pinfunction "1_1") (pintype "passive"))
      (node (ref "C64") (pin "-") (pinfunction "-_-") (pintype "passive"))
      (node (ref "C65") (pin "2") (pinfunction "2_2") (pintype "passive"))
      (node (ref "C7") (pin "1") (pinfunction "1_1") (pintype "passive"))
      (node (ref "C70") (pin "1") (pinfunction "1_1") (pintype "passive"))
      (node (ref "C71") (pin "1") (pinfunction "1_1") (pintype "passive"))
      (node (ref "C72") (pin "1") (pinfunction "1_1") (pintype "passive"))
      (node (ref "C73") (pin "1") (pinfunction "1_1") (pintype "passive"))
      (node (ref "C8") (pin "1") (pinfunction "1_1") (pintype "passive"))
      (node (ref "C9") (pin "-") (pinfunction "-_-") (pintype "passive"))
      (node (ref "D-0") (pin "C") (pinfunction "C_C") (pintype "passive"))
      (node (ref "HBP-T") (pin "2") (pinfunction "2_2") (pintype "passive"))
      (node (ref "IC1") (pin "11") (pinfunction "GND_11") (pintype "power_in"))
      (node (ref "IC1") (pin "32") (pinfunction "GND1_32") (pintype "power_in"))
      (node (ref "IC1") (pin "62") (pinfunction "GND2_62") (pintype "power_in"))
      (node (ref "IC1") (pin "81") (pinfunction "GND3_81") (pintype "power_in"))
      (node (ref "IC1") (pin "99") (pinfunction "AGND_99") (pintype "power_in"))
      (node (ref "IC2") (pin "28") (pinfunction "UGND_28") (pintype "power_in"))
      (node (ref "IC2") (pin "3") (pinfunction "GND_3") (pintype "power_in"))
      (node (ref "IC2") (pin "EXP") (pinfunction "PAD_EXP") (pintype "power_in"))
      (node (ref "L1") (pin "1") (pinfunction "1_1") (pintype "passive"))
      (node (ref "LC1") (pin "2") (pinfunction "VSS_2") (pintype "bidirectional"))
      (node (ref "LC2") (pin "2") (pinfunction "VSS_2") (pintype "bidirectional"))
      (node (ref "LC3") (pin "2") (pinfunction "VSS_2") (pintype "bidirectional"))
      (node (ref "LC4") (pin "2") (pinfunction "VSS_2") (pintype "bidirectional"))
      (node (ref "LC5") (pin "4") (pinfunction "GND_4") (pintype "bidirectional"))
      (node (ref "LC6") (pin "4") (pinfunction "VSS_4") (pintype "bidirectional"))
      (node (ref "LC7") (pin "2") (pinfunction "VSS_2") (pintype "bidirectional"))
      (node (ref "LED14") (pin "C") (pinfunction "C_C") (pintype "passive"))
      (node (ref "LED19") (pin "C") (pinfunction "C_C") (pintype "passive"))
      (node (ref "LED21") (pin "C") (pinfunction "C_C") (pintype "passive"))
      (node (ref "LED4") (pin "C") (pinfunction "C_C") (pintype "passive"))
      (node (ref "LED9") (pin "C") (pinfunction "C_C") (pintype "passive"))
      (node (ref "M1") (pin "1") (pinfunction "S_1") (pintype "passive"))
      (node (ref "M1") (pin "2") (pinfunction "S_2") (pintype "passive"))
      (node (ref "M1") (pin "3") (pinfunction "S_3") (pintype "passive"))
      (node (ref "M10") (pin "2") (pinfunction "S_2") (pintype "bidirectional"))
      (node (ref "M2") (pin "1") (pinfunction "S_1") (pintype "passive"))
      (node (ref "M2") (pin "2") (pinfunction "S_2") (pintype "passive"))
      (node (ref "M2") (pin "3") (pinfunction "S_3") (pintype "passive"))
      (node (ref "M3") (pin "1") (pinfunction "S_1") (pintype "passive"))
      (node (ref "M3") (pin "2") (pinfunction "S_2") (pintype "passive"))
      (node (ref "M3") (pin "3") (pinfunction "S_3") (pintype "passive"))
      (node (ref "M4") (pin "1") (pinfunction "S_1") (pintype "passive"))
      (node (ref "M4") (pin "2") (pinfunction "S_2") (pintype "passive"))
      (node (ref "M4") (pin "3") (pinfunction "S_3") (pintype "passive"))
      (node (ref "M5") (pin "1") (pinfunction "S_1") (pintype "passive"))
      (node (ref "M5") (pin "2") (pinfunction "S_2") (pintype "passive"))
      (node (ref "M5") (pin "3") (pinfunction "S_3") (pintype "passive"))
      (node (ref "M6") (pin "1") (pinfunction "S_1") (pintype "passive"))
      (node (ref "M6") (pin "2") (pinfunction "S_2") (pintype "passive"))
      (node (ref "M6") (pin "3") (pinfunction "S_3") (pintype "passive"))
      (node (ref "M7") (pin "1") (pinfunction "S_1") (pintype "passive"))
      (node (ref "M7") (pin "2") (pinfunction "S_2") (pintype "passive"))
      (node (ref "M7") (pin "3") (pinfunction "S_3") (pintype "passive"))
      (node (ref "M8") (pin "2") (pinfunction "S_2") (pintype "bidirectional"))
      (node (ref "M9") (pin "2") (pinfunction "S_2") (pintype "bidirectional"))
      (node (ref "P-STOP") (pin "2") (pinfunction "2_2") (pintype "passive"))
      (node (ref "P1") (pin "2") (pinfunction "GND_2") (pintype "input"))
      (node (ref "PIN1") (pin "6") (pinfunction "6_6") (pintype "passive"))
      (node (ref "PIN10") (pin "1") (pinfunction "1_1") (pintype "passive"))
      (node (ref "PIN11") (pin "1") (pinfunction "1_1") (pintype "passive"))
      (node (ref "PIN12") (pin "1") (pinfunction "1_1") (pintype "passive"))
      (node (ref "PIN2") (pin "6") (pinfunction "6_6") (pintype "passive"))
      (node (ref "PIN9") (pin "1") (pinfunction "1_1") (pintype "passive"))
      (node (ref "R10") (pin "1") (pinfunction "1_1") (pintype "passive"))
      (node (ref "R100") (pin "2") (pinfunction "2_2") (pintype "passive"))
      (node (ref "R119") (pin "1") (pinfunction "1_1") (pintype "passive"))
      (node (ref "R120") (pin "1") (pinfunction "1_1") (pintype "passive"))
      (node (ref "R121") (pin "1") (pinfunction "1_1") (pintype "passive"))
      (node (ref "R122") (pin "2") (pinfunction "2_2") (pintype "passive"))
      (node (ref "R125") (pin "1") (pinfunction "1_1") (pintype "passive"))
      (node (ref "R126") (pin "1") (pinfunction "1_1") (pintype "passive"))
      (node (ref "R127") (pin "2") (pinfunction "2_2") (pintype "passive"))
      (node (ref "R139") (pin "2") (pinfunction "2_2") (pintype "passive"))
      (node (ref "R19") (pin "1") (pinfunction "1_1") (pintype "passive"))
      (node (ref "R20") (pin "1") (pinfunction "1_1") (pintype "passive"))
      (node (ref "R22") (pin "2") (pinfunction "2_2") (pintype "passive"))
      (node (ref "R26") (pin "1") (pinfunction "1_1") (pintype "passive"))
      (node (ref "R27") (pin "1") (pinfunction "1_1") (pintype "passive"))
      (node (ref "R29") (pin "2") (pinfunction "2_2") (pintype "passive"))
      (node (ref "R33") (pin "1") (pinfunction "1_1") (pintype "passive"))
      (node (ref "R4") (pin "1") (pinfunction "1_1") (pintype "passive"))
      (node (ref "R41") (pin "1") (pinfunction "1_1") (pintype "passive"))
      (node (ref "R46") (pin "2") (pinfunction "2_2") (pintype "passive"))
      (node (ref "R49") (pin "1") (pinfunction "1_1") (pintype "passive"))
      (node (ref "R5") (pin "1") (pinfunction "1_1") (pintype "passive"))
      (node (ref "R50") (pin "1") (pinfunction "1_1") (pintype "passive"))
      (node (ref "R51") (pin "1") (pinfunction "1_1") (pintype "passive"))
      (node (ref "R52") (pin "2") (pinfunction "2_2") (pintype "passive"))
      (node (ref "R54") (pin "1") (pinfunction "1_1") (pintype "passive"))
      (node (ref "R65") (pin "1") (pinfunction "1_1") (pintype "passive"))
      (node (ref "R67") (pin "2") (pinfunction "2_2") (pintype "passive"))
      (node (ref "R7") (pin "1") (pinfunction "1_1") (pintype "passive"))
      (node (ref "R73") (pin "1") (pinfunction "1_1") (pintype "passive"))
      (node (ref "R74") (pin "1") (pinfunction "1_1") (pintype "passive"))
      (node (ref "R76") (pin "2") (pinfunction "2_2") (pintype "passive"))
      (node (ref "R83") (pin "1") (pinfunction "1_1") (pintype "passive"))
      (node (ref "R94") (pin "2") (pinfunction "2_2") (pintype "passive"))
      (node (ref "R98") (pin "1") (pinfunction "1_1") (pintype "passive"))
      (node (ref "R99") (pin "1") (pinfunction "1_1") (pintype "passive"))
      (node (ref "RESET") (pin "3") (pinfunction "P_3") (pintype "passive"))
      (node (ref "RESET") (pin "4") (pinfunction "P1_4") (pintype "passive"))
      (node (ref "SPEAKER") (pin "-") (pinfunction "+_-") (pintype "passive"))
      (node (ref "SV2") (pin "2") (pinfunction "2_2") (pintype "passive"))
      (node (ref "SV2") (pin "4") (pinfunction "4_4") (pintype "passive"))
      (node (ref "SV2") (pin "5") (pinfunction "5_5") (pintype "passive"))
      (node (ref "SV2") (pin "6") (pinfunction "6_6") (pintype "passive"))
      (node (ref "X-MAX") (pin "2") (pinfunction "2_2") (pintype "passive"))
      (node (ref "X8") (pin "4") (pinfunction "4_4") (pintype "bidirectional"))
      (node (ref "Y-MAX") (pin "2") (pinfunction "2_2") (pintype "passive"))
      (node (ref "Z-MAX") (pin "2") (pinfunction "2_2") (pintype "passive"))
      (node (ref "Z-MIN") (pin "2") (pinfunction "2_2") (pintype "passive"))
    )
    (net (code "34") (name "HBP-T") (class "Default")
      (node (ref "HBP-T") (pin "3") (pinfunction "3_3") (pintype "passive"))
      (node (ref "IC1") (pin "82") (pinfunction "PK7(ADC15/PCINT23)_82") (pintype "bidirectional"))
      (node (ref "R92") (pin "1") (pinfunction "1_1") (pintype "passive"))
    )
    (net (code "35") (name "HEATED_BED") (class "Default")
      (node (ref "IC1") (pin "39") (pinfunction "PL4(OC5B)_39") (pintype "bidirectional"))
      (node (ref "M5") (pin "4") (pinfunction "G_4") (pintype "passive"))
      (node (ref "R54") (pin "2") (pinfunction "2_2") (pintype "passive"))
    )
    (net (code "36") (name "LCD-CLK") (class "Default")
      (node (ref "IC1") (pin "55") (pinfunction "(A10)PC2_55") (pintype "bidirectional"))
      (node (ref "SV2") (pin "14") (pinfunction "14_14") (pintype "passive"))
    )
    (net (code "37") (name "LCD-DATA") (class "Default")
      (node (ref "IC1") (pin "56") (pinfunction "(A11)PC3_56") (pintype "bidirectional"))
      (node (ref "SV2") (pin "13") (pinfunction "13_13") (pintype "passive"))
    )
    (net (code "38") (name "LCD-STROBE") (class "Default")
      (node (ref "IC1") (pin "57") (pinfunction "(A12)PC4_57") (pintype "bidirectional"))
      (node (ref "SV2") (pin "16") (pinfunction "16_16") (pintype "passive"))
    )
    (net (code "39") (name "LEFT") (class "Default")
      (node (ref "IC1") (pin "65") (pinfunction "PJ2(XCK3/PCINT11)_65") (pintype "bidirectional"))
      (node (ref "SV2") (pin "22") (pinfunction "22_22") (pintype "passive"))
    )
    (net (code "40") (name "Net-(5V-PadA)") (class "Default")
      (node (ref "5V") (pin "A") (pinfunction "A_A") (pintype "passive"))
      (node (ref "R103") (pin "2") (pinfunction "2_2") (pintype "passive"))
    )
    (net (code "41") (name "Net-(15A_SWITCH-OUT2)") (class "Default")
      (node (ref "15A_SWITCH") (pin "1A") (pinfunction "OUT2_1A") (pintype "bidirectional"))
      (node (ref "D1") (pin "A") (pinfunction "A_A") (pintype "passive"))
    )
    (net (code "42") (name "Net-(15A_SWITCH-SUPPLY)") (class "Default")
      (node (ref "-24V+") (pin "1") (pinfunction "1_1") (pintype "passive"))
      (node (ref "15A_SWITCH") (pin "1") (pinfunction "SUPPLY_1") (pintype "bidirectional"))
    )
    (net (code "43") (name "Net-(24V-PadA)") (class "Default")
      (node (ref "24V") (pin "A") (pinfunction "A_A") (pintype "passive"))
      (node (ref "R104") (pin "1") (pinfunction "1_1") (pintype "passive"))
    )
    (net (code "44") (name "Net-(A1-CP1)") (class "Default")
      (node (ref "A1") (pin "P07") (pinfunction "CP1_P07") (pintype "bidirectional"))
      (node (ref "C2") (pin "1") (pinfunction "1_1") (pintype "passive"))
    )
    (net (code "45") (name "Net-(A1-CP2)") (class "Default")
      (node (ref "A1") (pin "P08") (pinfunction "CP2_P08") (pintype "bidirectional"))
      (node (ref "C2") (pin "2") (pinfunction "2_2") (pintype "passive"))
    )
    (net (code "46") (name "Net-(A1-MS1)") (class "Default")
      (node (ref "A1") (pin "P11") (pinfunction "MS1_P11") (pintype "bidirectional"))
      (node (ref "R14") (pin "2") (pinfunction "2_2") (pintype "passive"))
    )
    (net (code "47") (name "Net-(A1-MS2)") (class "Default")
      (node (ref "A1") (pin "P12") (pinfunction "MS2_P12") (pintype "bidirectional"))
      (node (ref "R15") (pin "2") (pinfunction "2_2") (pintype "passive"))
    )
    (net (code "48") (name "Net-(A1-OUT1A)") (class "Default")
      (node (ref "A1") (pin "P27") (pinfunction "OUT1A_P27") (pintype "bidirectional"))
      (node (ref "JP7") (pin "2") (pinfunction "2_2") (pintype "passive"))
    )
    (net (code "49") (name "Net-(A1-OUT1B)") (class "Default")
      (node (ref "A1") (pin "P24") (pinfunction "OUT1B_P24") (pintype "bidirectional"))
      (node (ref "JP7") (pin "1") (pinfunction "1_1") (pintype "passive"))
    )
    (net (code "50") (name "Net-(A1-OUT2A)") (class "Default")
      (node (ref "A1") (pin "P30") (pinfunction "OUT2A_P30") (pintype "bidirectional"))
      (node (ref "JP7") (pin "3") (pinfunction "3_3") (pintype "passive"))
    )
    (net (code "51") (name "Net-(A1-OUT2B)") (class "Default")
      (node (ref "A1") (pin "P01") (pinfunction "OUT2B_P01") (pintype "bidirectional"))
      (node (ref "JP7") (pin "4") (pinfunction "4_4") (pintype "passive"))
    )
    (net (code "52") (name "Net-(A1-RESET)") (class "Default")
      (node (ref "A1") (pin "P13") (pinfunction "RESET_P13") (pintype "bidirectional"))
      (node (ref "R25") (pin "1") (pinfunction "1_1") (pintype "passive"))
    )
    (net (code "53") (name "Net-(A1-ROSC)") (class "Default")
      (node (ref "A1") (pin "P14") (pinfunction "ROSC_P14") (pintype "bidirectional"))
      (node (ref "R29") (pin "1") (pinfunction "1_1") (pintype "passive"))
    )
    (net (code "54") (name "Net-(A1-SENSE1)") (class "Default")
      (node (ref "A1") (pin "P25") (pinfunction "SENSE1_P25") (pintype "bidirectional"))
      (node (ref "R26") (pin "2") (pinfunction "2_2") (pintype "passive"))
    )
    (net (code "55") (name "Net-(A1-SENSE2)") (class "Default")
      (node (ref "A1") (pin "P32") (pinfunction "SENSE2_P32") (pintype "bidirectional"))
      (node (ref "R27") (pin "2") (pinfunction "2_2") (pintype "passive"))
    )
    (net (code "56") (name "Net-(A1-SLEEP)") (class "Default")
      (node (ref "A1") (pin "P15") (pinfunction "SLEEP_P15") (pintype "bidirectional"))
      (node (ref "R23") (pin "1") (pinfunction "1_1") (pintype "passive"))
    )
    (net (code "57") (name "Net-(A1-VCP)") (class "Default")
      (node (ref "A1") (pin "P09") (pinfunction "VCP_P09") (pintype "bidirectional"))
      (node (ref "C3") (pin "2") (pinfunction "2_2") (pintype "passive"))
    )
    (net (code "58") (name "Net-(A1-VREF)") (class "Default")
      (node (ref "A1") (pin "P18") (pinfunction "VREF_P18") (pintype "bidirectional"))
      (node (ref "C11") (pin "2") (pinfunction "2_2") (pintype "passive"))
      (node (ref "LC1") (pin "5") (pinfunction "W_5") (pintype "bidirectional"))
      (node (ref "R13") (pin "2") (pinfunction "2_2") (pintype "passive"))
      (node (ref "R22") (pin "1") (pinfunction "1_1") (pintype "passive"))
    )
    (net (code "59") (name "Net-(A1-VREG)") (class "Default")
      (node (ref "A1") (pin "P10") (pinfunction "VREG_P10") (pintype "bidirectional"))
      (node (ref "C16") (pin "1") (pinfunction "1_1") (pintype "passive"))
    )
    (net (code "60") (name "Net-(A2-CP1)") (class "Default")
      (node (ref "A2") (pin "P07") (pinfunction "CP1_P07") (pintype "bidirectional"))
      (node (ref "C17") (pin "1") (pinfunction "1_1") (pintype "passive"))
    )
    (net (code "61") (name "Net-(A2-CP2)") (class "Default")
      (node (ref "A2") (pin "P08") (pinfunction "CP2_P08") (pintype "bidirectional"))
      (node (ref "C17") (pin "2") (pinfunction "2_2") (pintype "passive"))
    )
    (net (code "62") (name "Net-(A2-MS1)") (class "Default")
      (node (ref "A2") (pin "P11") (pinfunction "MS1_P11") (pintype "bidirectional"))
      (node (ref "R37") (pin "2") (pinfunction "2_2") (pintype "passive"))
    )
    (net (code "63") (name "Net-(A2-MS2)") (class "Default")
      (node (ref "A2") (pin "P12") (pinfunction "MS2_P12") (pintype "bidirectional"))
      (node (ref "R38") (pin "2") (pinfunction "2_2") (pintype "passive"))
    )
    (net (code "64") (name "Net-(A2-OUT1A)") (class "Default")
      (node (ref "A2") (pin "P27") (pinfunction "OUT1A_P27") (pintype "bidirectional"))
      (node (ref "JP6") (pin "2") (pinfunction "2_2") (pintype "passive"))
    )
    (net (code "65") (name "Net-(A2-OUT1B)") (class "Default")
      (node (ref "A2") (pin "P24") (pinfunction "OUT1B_P24") (pintype "bidirectional"))
      (node (ref "JP6") (pin "1") (pinfunction "1_1") (pintype "passive"))
    )
    (net (code "66") (name "Net-(A2-OUT2A)") (class "Default")
      (node (ref "A2") (pin "P30") (pinfunction "OUT2A_P30") (pintype "bidirectional"))
      (node (ref "JP6") (pin "3") (pinfunction "3_3") (pintype "passive"))
    )
    (net (code "67") (name "Net-(A2-OUT2B)") (class "Default")
      (node (ref "A2") (pin "P01") (pinfunction "OUT2B_P01") (pintype "bidirectional"))
      (node (ref "JP6") (pin "4") (pinfunction "4_4") (pintype "passive"))
    )
    (net (code "68") (name "Net-(A2-RESET)") (class "Default")
      (node (ref "A2") (pin "P13") (pinfunction "RESET_P13") (pintype "bidirectional"))
      (node (ref "R48") (pin "1") (pinfunction "1_1") (pintype "passive"))
    )
    (net (code "69") (name "Net-(A2-ROSC)") (class "Default")
      (node (ref "A2") (pin "P14") (pinfunction "ROSC_P14") (pintype "bidirectional"))
      (node (ref "R52") (pin "1") (pinfunction "1_1") (pintype "passive"))
    )
    (net (code "70") (name "Net-(A2-SENSE1)") (class "Default")
      (node (ref "A2") (pin "P25") (pinfunction "SENSE1_P25") (pintype "bidirectional"))
      (node (ref "R50") (pin "2") (pinfunction "2_2") (pintype "passive"))
    )
    (net (code "71") (name "Net-(A2-SENSE2)") (class "Default")
      (node (ref "A2") (pin "P32") (pinfunction "SENSE2_P32") (pintype "bidirectional"))
      (node (ref "R51") (pin "2") (pinfunction "2_2") (pintype "passive"))
    )
    (net (code "72") (name "Net-(A2-SLEEP)") (class "Default")
      (node (ref "A2") (pin "P15") (pinfunction "SLEEP_P15") (pintype "bidirectional"))
      (node (ref "R47") (pin "1") (pinfunction "1_1") (pintype "passive"))
    )
    (net (code "73") (name "Net-(A2-VCP)") (class "Default")
      (node (ref "A2") (pin "P09") (pinfunction "VCP_P09") (pintype "bidirectional"))
      (node (ref "C18") (pin "2") (pinfunction "2_2") (pintype "passive"))
    )
    (net (code "74") (name "Net-(A2-VREF)") (class "Default")
      (node (ref "A2") (pin "P18") (pinfunction "VREF_P18") (pintype "bidirectional"))
      (node (ref "C26") (pin "2") (pinfunction "2_2") (pintype "passive"))
      (node (ref "LC2") (pin "5") (pinfunction "W_5") (pintype "bidirectional"))
      (node (ref "R36") (pin "2") (pinfunction "2_2") (pintype "passive"))
      (node (ref "R46") (pin "1") (pinfunction "1_1") (pintype "passive"))
    )
    (net (code "75") (name "Net-(A2-VREG)") (class "Default")
      (node (ref "A2") (pin "P10") (pinfunction "VREG_P10") (pintype "bidirectional"))
      (node (ref "C31") (pin "1") (pinfunction "1_1") (pintype "passive"))
    )
    (net (code "76") (name "Net-(A3-CP1)") (class "Default")
      (node (ref "A3") (pin "P07") (pinfunction "CP1_P07") (pintype "bidirectional"))
      (node (ref "C35") (pin "1") (pinfunction "1_1") (pintype "passive"))
    )
    (net (code "77") (name "Net-(A3-CP2)") (class "Default")
      (node (ref "A3") (pin "P08") (pinfunction "CP2_P08") (pintype "bidirectional"))
      (node (ref "C35") (pin "2") (pinfunction "2_2") (pintype "passive"))
    )
    (net (code "78") (name "Net-(A3-MS1)") (class "Default")
      (node (ref "A3") (pin "P11") (pinfunction "MS1_P11") (pintype "bidirectional"))
      (node (ref "R62") (pin "2") (pinfunction "2_2") (pintype "passive"))
    )
    (net (code "79") (name "Net-(A3-MS2)") (class "Default")
      (node (ref "A3") (pin "P12") (pinfunction "MS2_P12") (pintype "bidirectional"))
      (node (ref "R63") (pin "2") (pinfunction "2_2") (pintype "passive"))
    )
    (net (code "80") (name "Net-(A3-OUT1A)") (class "Default")
      (node (ref "A3") (pin "P27") (pinfunction "OUT1A_P27") (pintype "bidirectional"))
      (node (ref "JP5") (pin "2") (pinfunction "2_2") (pintype "passive"))
    )
    (net (code "81") (name "Net-(A3-OUT1B)") (class "Default")
      (node (ref "A3") (pin "P24") (pinfunction "OUT1B_P24") (pintype "bidirectional"))
      (node (ref "JP5") (pin "1") (pinfunction "1_1") (pintype "passive"))
    )
    (net (code "82") (name "Net-(A3-OUT2A)") (class "Default")
      (node (ref "A3") (pin "P30") (pinfunction "OUT2A_P30") (pintype "bidirectional"))
      (node (ref "JP5") (pin "3") (pinfunction "3_3") (pintype "passive"))
    )
    (net (code "83") (name "Net-(A3-OUT2B)") (class "Default")
      (node (ref "A3") (pin "P01") (pinfunction "OUT2B_P01") (pintype "bidirectional"))
      (node (ref "JP5") (pin "4") (pinfunction "4_4") (pintype "passive"))
    )
    (net (code "84") (name "Net-(A3-RESET)") (class "Default")
      (node (ref "A3") (pin "P13") (pinfunction "RESET_P13") (pintype "bidirectional"))
      (node (ref "R70") (pin "1") (pinfunction "1_1") (pintype "passive"))
    )
    (net (code "85") (name "Net-(A3-ROSC)") (class "Default")
      (node (ref "A3") (pin "P14") (pinfunction "ROSC_P14") (pintype "bidirectional"))
      (node (ref "R76") (pin "1") (pinfunction "1_1") (pintype "passive"))
    )
    (net (code "86") (name "Net-(A3-SENSE1)") (class "Default")
      (node (ref "A3") (pin "P25") (pinfunction "SENSE1_P25") (pintype "bidirectional"))
      (node (ref "R73") (pin "2") (pinfunction "2_2") (pintype "passive"))
    )
    (net (code "87") (name "Net-(A3-SENSE2)") (class "Default")
      (node (ref "A3") (pin "P32") (pinfunction "SENSE2_P32") (pintype "bidirectional"))
      (node (ref "R74") (pin "2") (pinfunction "2_2") (pintype "passive"))
    )
    (net (code "88") (name "Net-(A3-SLEEP)") (class "Default")
      (node (ref "A3") (pin "P15") (pinfunction "SLEEP_P15") (pintype "bidirectional"))
      (node (ref "R69") (pin "1") (pinfunction "1_1") (pintype "passive"))
    )
    (net (code "89") (name "Net-(A3-VCP)") (class "Default")
      (node (ref "A3") (pin "P09") (pinfunction "VCP_P09") (pintype "bidirectional"))
      (node (ref "C36") (pin "2") (pinfunction "2_2") (pintype "passive"))
    )
    (net (code "90") (name "Net-(A3-VREF)") (class "Default")
      (node (ref "A3") (pin "P18") (pinfunction "VREF_P18") (pintype "bidirectional"))
      (node (ref "C42") (pin "2") (pinfunction "2_2") (pintype "passive"))
      (node (ref "LC3") (pin "5") (pinfunction "W_5") (pintype "bidirectional"))
      (node (ref "R61") (pin "2") (pinfunction "2_2") (pintype "passive"))
      (node (ref "R67") (pin "1") (pinfunction "1_1") (pintype "passive"))
    )
    (net (code "91") (name "Net-(A3-VREG)") (class "Default")
      (node (ref "A3") (pin "P10") (pinfunction "VREG_P10") (pintype "bidirectional"))
      (node (ref "C44") (pin "1") (pinfunction "1_1") (pintype "passive"))
    )
    (net (code "92") (name "Net-(A4-CP1)") (class "Default")
      (node (ref "A4") (pin "P07") (pinfunction "CP1_P07") (pintype "bidirectional"))
      (node (ref "C48") (pin "1") (pinfunction "1_1") (pintype "passive"))
    )
    (net (code "93") (name "Net-(A4-CP2)") (class "Default")
      (node (ref "A4") (pin "P08") (pinfunction "CP2_P08") (pintype "bidirectional"))
      (node (ref "C48") (pin "2") (pinfunction "2_2") (pintype "passive"))
    )
    (net (code "94") (name "Net-(A4-MS1)") (class "Default")
      (node (ref "A4") (pin "P11") (pinfunction "MS1_P11") (pintype "bidirectional"))
      (node (ref "R89") (pin "2") (pinfunction "2_2") (pintype "passive"))
    )
    (net (code "95") (name "Net-(A4-MS2)") (class "Default")
      (node (ref "A4") (pin "P12") (pinfunction "MS2_P12") (pintype "bidirectional"))
      (node (ref "R90") (pin "2") (pinfunction "2_2") (pintype "passive"))
    )
    (net (code "96") (name "Net-(A4-OUT1A)") (class "Default")
      (node (ref "A4") (pin "P27") (pinfunction "OUT1A_P27") (pintype "bidirectional"))
      (node (ref "JP4") (pin "2") (pinfunction "2_2") (pintype "passive"))
    )
    (net (code "97") (name "Net-(A4-OUT1B)") (class "Default")
      (node (ref "A4") (pin "P24") (pinfunction "OUT1B_P24") (pintype "bidirectional"))
      (node (ref "JP4") (pin "1") (pinfunction "1_1") (pintype "passive"))
    )
    (net (code "98") (name "Net-(A4-OUT2A)") (class "Default")
      (node (ref "A4") (pin "P30") (pinfunction "OUT2A_P30") (pintype "bidirectional"))
      (node (ref "JP4") (pin "3") (pinfunction "3_3") (pintype "passive"))
    )
    (net (code "99") (name "Net-(A4-OUT2B)") (class "Default")
      (node (ref "A4") (pin "P01") (pinfunction "OUT2B_P01") (pintype "bidirectional"))
      (node (ref "JP4") (pin "4") (pinfunction "4_4") (pintype "passive"))
    )
    (net (code "100") (name "Net-(A4-RESET)") (class "Default")
      (node (ref "A4") (pin "P13") (pinfunction "RESET_P13") (pintype "bidirectional"))
      (node (ref "R97") (pin "1") (pinfunction "1_1") (pintype "passive"))
    )
    (net (code "101") (name "Net-(A4-ROSC)") (class "Default")
      (node (ref "A4") (pin "P14") (pinfunction "ROSC_P14") (pintype "bidirectional"))
      (node (ref "R100") (pin "1") (pinfunction "1_1") (pintype "passive"))
    )
    (net (code "102") (name "Net-(A4-SENSE1)") (class "Default")
      (node (ref "A4") (pin "P25") (pinfunction "SENSE1_P25") (pintype "bidirectional"))
      (node (ref "R98") (pin "2") (pinfunction "2_2") (pintype "passive"))
    )
    (net (code "103") (name "Net-(A4-SENSE2)") (class "Default")
      (node (ref "A4") (pin "P32") (pinfunction "SENSE2_P32") (pintype "bidirectional"))
      (node (ref "R99") (pin "2") (pinfunction "2_2") (pintype "passive"))
    )
    (net (code "104") (name "Net-(A4-SLEEP)") (class "Default")
      (node (ref "A4") (pin "P15") (pinfunction "SLEEP_P15") (pintype "bidirectional"))
      (node (ref "R96") (pin "1") (pinfunction "1_1") (pintype "passive"))
    )
    (net (code "105") (name "Net-(A4-VCP)") (class "Default")
      (node (ref "A4") (pin "P09") (pinfunction "VCP_P09") (pintype "bidirectional"))
      (node (ref "C49") (pin "2") (pinfunction "2_2") (pintype "passive"))
    )
    (net (code "106") (name "Net-(A4-VREF)") (class "Default")
      (node (ref "A4") (pin "P18") (pinfunction "VREF_P18") (pintype "bidirectional"))
      (node (ref "C54") (pin "2") (pinfunction "2_2") (pintype "passive"))
      (node (ref "LC4") (pin "5") (pinfunction "W_5") (pintype "bidirectional"))
      (node (ref "R88") (pin "2") (pinfunction "2_2") (pintype "passive"))
      (node (ref "R94") (pin "1") (pinfunction "1_1") (pintype "passive"))
    )
    (net (code "107") (name "Net-(A4-VREG)") (class "Default")
      (node (ref "A4") (pin "P10") (pinfunction "VREG_P10") (pintype "bidirectional"))
      (node (ref "C56") (pin "1") (pinfunction "1_1") (pintype "passive"))
    )
    (net (code "108") (name "Net-(A5-CP1)") (class "Default")
      (node (ref "A5") (pin "P07") (pinfunction "CP1_P07") (pintype "bidirectional"))
      (node (ref "C57") (pin "1") (pinfunction "1_1") (pintype "passive"))
    )
    (net (code "109") (name "Net-(A5-CP2)") (class "Default")
      (node (ref "A5") (pin "P08") (pinfunction "CP2_P08") (pintype "bidirectional"))
      (node (ref "C57") (pin "2") (pinfunction "2_2") (pintype "passive"))
    )
    (net (code "110") (name "Net-(A5-MS1)") (class "Default")
      (node (ref "A5") (pin "P11") (pinfunction "MS1_P11") (pintype "bidirectional"))
      (node (ref "R109") (pin "2") (pinfunction "2_2") (pintype "passive"))
    )
    (net (code "111") (name "Net-(A5-MS2)") (class "Default")
      (node (ref "A5") (pin "P12") (pinfunction "MS2_P12") (pintype "bidirectional"))
      (node (ref "R110") (pin "2") (pinfunction "2_2") (pintype "passive"))
    )
    (net (code "112") (name "Net-(A5-OUT1A)") (class "Default")
      (node (ref "A5") (pin "P27") (pinfunction "OUT1A_P27") (pintype "bidirectional"))
      (node (ref "JP3") (pin "2") (pinfunction "2_2") (pintype "passive"))
    )
    (net (code "113") (name "Net-(A5-OUT1B)") (class "Default")
      (node (ref "A5") (pin "P24") (pinfunction "OUT1B_P24") (pintype "bidirectional"))
      (node (ref "JP3") (pin "1") (pinfunction "1_1") (pintype "passive"))
    )
    (net (code "114") (name "Net-(A5-OUT2A)") (class "Default")
      (node (ref "A5") (pin "P30") (pinfunction "OUT2A_P30") (pintype "bidirectional"))
      (node (ref "JP3") (pin "3") (pinfunction "3_3") (pintype "passive"))
    )
    (net (code "115") (name "Net-(A5-OUT2B)") (class "Default")
      (node (ref "A5") (pin "P01") (pinfunction "OUT2B_P01") (pintype "bidirectional"))
      (node (ref "JP3") (pin "4") (pinfunction "4_4") (pintype "passive"))
    )
    (net (code "116") (name "Net-(A5-RESET)") (class "Default")
      (node (ref "A5") (pin "P13") (pinfunction "RESET_P13") (pintype "bidirectional"))
      (node (ref "R124") (pin "1") (pinfunction "1_1") (pintype "passive"))
    )
    (net (code "117") (name "Net-(A5-ROSC)") (class "Default")
      (node (ref "A5") (pin "P14") (pinfunction "ROSC_P14") (pintype "bidirectional"))
      (node (ref "R127") (pin "1") (pinfunction "1_1") (pintype "passive"))
    )
    (net (code "118") (name "Net-(A5-SENSE1)") (class "Default")
      (node (ref "A5") (pin "P25") (pinfunction "SENSE1_P25") (pintype "bidirectional"))
      (node (ref "R125") (pin "2") (pinfunction "2_2") (pintype "passive"))
    )
    (net (code "119") (name "Net-(A5-SENSE2)") (class "Default")
      (node (ref "A5") (pin "P32") (pinfunction "SENSE2_P32") (pintype "bidirectional"))
      (node (ref "R126") (pin "2") (pinfunction "2_2") (pintype "passive"))
    )
    (net (code "120") (name "Net-(A5-SLEEP)") (class "Default")
      (node (ref "A5") (pin "P15") (pinfunction "SLEEP_P15") (pintype "bidirectional"))
      (node (ref "R123") (pin "1") (pinfunction "1_1") (pintype "passive"))
    )
    (net (code "121") (name "Net-(A5-VCP)") (class "Default")
      (node (ref "A5") (pin "P09") (pinfunction "VCP_P09") (pintype "bidirectional"))
      (node (ref "C58") (pin "2") (pinfunction "2_2") (pintype "passive"))
    )
    (net (code "122") (name "Net-(A5-VREF)") (class "Default")
      (node (ref "A5") (pin "P18") (pinfunction "VREF_P18") (pintype "bidirectional"))
      (node (ref "C63") (pin "2") (pinfunction "2_2") (pintype "passive"))
      (node (ref "LC7") (pin "5") (pinfunction "W_5") (pintype "bidirectional"))
      (node (ref "R108") (pin "2") (pinfunction "2_2") (pintype "passive"))
      (node (ref "R122") (pin "1") (pinfunction "1_1") (pintype "passive"))
    )
    (net (code "123") (name "Net-(A5-VREG)") (class "Default")
      (node (ref "A5") (pin "P10") (pinfunction "VREG_P10") (pintype "bidirectional"))
      (node (ref "C65") (pin "1") (pinfunction "1_1") (pintype "passive"))
    )
    (net (code "124") (name "Net-(ACT-PadC)") (class "Default")
      (node (ref "ACT") (pin "C") (pinfunction "C_C") (pintype "passive"))
      (node (ref "R4") (pin "2") (pinfunction "2_2") (pintype "passive"))
    )
    (net (code "125") (name "Net-(D-0-PadA)") (class "Default")
      (node (ref "D-0") (pin "A") (pinfunction "A_A") (pintype "passive"))
      (node (ref "R2") (pin "2") (pinfunction "2_2") (pintype "passive"))
    )
    (net (code "126") (name "Net-(D-1-PadC)") (class "Default")
      (node (ref "D-1") (pin "C") (pinfunction "C_C") (pintype "passive"))
      (node (ref "R119") (pin "2") (pinfunction "2_2") (pintype "passive"))
    )
    (net (code "127") (name "Net-(D-2-PadC)") (class "Default")
      (node (ref "D-2") (pin "C") (pinfunction "C_C") (pintype "passive"))
      (node (ref "R120") (pin "2") (pinfunction "2_2") (pintype "passive"))
    )
    (net (code "128") (name "Net-(D-3-PadC)") (class "Default")
      (node (ref "D-3") (pin "C") (pinfunction "C_C") (pintype "passive"))
      (node (ref "R121") (pin "2") (pinfunction "2_2") (pintype "passive"))
    )
    (net (code "129") (name "Net-(F1-PadA)") (class "Default")
      (node (ref "F1") (pin "A") (pinfunction "A_A") (pintype "passive"))
      (node (ref "R44") (pin "1") (pinfunction "1_1") (pintype "passive"))
    )
    (net (code "130") (name "Net-(F2-PadA)") (class "Default")
      (node (ref "F2") (pin "A") (pinfunction "A_A") (pintype "passive"))
      (node (ref "R32") (pin "1") (pinfunction "1_1") (pintype "passive"))
    )
    (net (code "131") (name "Net-(F3-PadA)") (class "Default")
      (node (ref "F3") (pin "A") (pinfunction "A_A") (pintype "passive"))
      (node (ref "R17") (pin "1") (pinfunction "1_1") (pintype "passive"))
    )
    (net (code "132") (name "Net-(F4-PadA)") (class "Default")
      (node (ref "F4") (pin "A") (pinfunction "A_A") (pintype "passive"))
      (node (ref "R6") (pin "1") (pinfunction "1_1") (pintype "passive"))
    )
    (net (code "133") (name "Net-(F5-PadA)") (class "Default")
      (node (ref "F5") (pin "A") (pinfunction "A_A") (pintype "passive"))
      (node (ref "R56") (pin "1") (pinfunction "1_1") (pintype "passive"))
    )
    (net (code "134") (name "Net-(F6-PadA)") (class "Default")
      (node (ref "F6") (pin "A") (pinfunction "A_A") (pintype "passive"))
      (node (ref "R68") (pin "1") (pinfunction "1_1") (pintype "passive"))
    )
    (net (code "135") (name "Net-(F7-PadA)") (class "Default")
      (node (ref "F7") (pin "A") (pinfunction "A_A") (pintype "passive"))
      (node (ref "R86") (pin "1") (pinfunction "1_1") (pintype "passive"))
    )
    (net (code "136") (name "Net-(FAN-1B-1)") (class "Default")
      (node (ref "F6") (pin "C") (pinfunction "C_C") (pintype "passive"))
      (node (ref "FAN-1") (pin "2") (pinfunction "1_2") (pintype "passive"))
      (node (ref "M6") (pin "MB") (pinfunction "D_MB") (pintype "passive"))
    )
    (net (code "137") (name "Net-(FAN-2B-1)") (class "Default")
      (node (ref "F7") (pin "C") (pinfunction "C_C") (pintype "passive"))
      (node (ref "FAN-2") (pin "2") (pinfunction "1_2") (pintype "passive"))
      (node (ref "M7") (pin "MB") (pinfunction "D_MB") (pintype "passive"))
    )
    (net (code "138") (name "Net-(FUSE_HOLDER-2)") (class "Default")
      (node (ref "D1") (pin "C") (pinfunction "C_C") (pintype "passive"))
      (node (ref "FUSE_HOLDER") (pin "3") (pinfunction "2_3") (pintype "bidirectional"))
    )
    (net (code "139") (name "Net-(HBPB-1)") (class "Default")
      (node (ref "F5") (pin "C") (pinfunction "C_C") (pintype "passive"))
      (node (ref "HBP") (pin "2") (pinfunction "1_2") (pintype "passive"))
      (node (ref "M5") (pin "MB") (pinfunction "D_MB") (pintype "passive"))
    )
    (net (code "140") (name "Net-(IC1-(OC0A{slash}OC1C{slash}PCINT7)PB7)") (class "Default")
      (node (ref "ACT") (pin "A") (pinfunction "A_A") (pintype "passive"))
      (node (ref "IC1") (pin "26") (pinfunction "(OC0A/OC1C/PCINT7)PB7_26") (pintype "bidirectional"))
    )
    (net (code "141") (name "Net-(IC1-(TOSC1)PG4)") (class "Default")
      (node (ref "IC1") (pin "29") (pinfunction "(TOSC1)PG4_29") (pintype "bidirectional"))
      (node (ref "R2") (pin "1") (pinfunction "1_1") (pintype "passive"))
      (node (ref "R3") (pin "1") (pinfunction "1_1") (pintype "passive"))
    )
    (net (code "142") (name "Net-(IC1-PH0(RXD2))") (class "Default")
      (node (ref "IC1") (pin "12") (pinfunction "PH0(RXD2)_12") (pintype "bidirectional"))
      (node (ref "R24") (pin "1") (pinfunction "1_1") (pintype "passive"))
    )
    (net (code "143") (name "Net-(IC1-PH1(TXD2))") (class "Default")
      (node (ref "IC1") (pin "13") (pinfunction "PH1(TXD2)_13") (pintype "bidirectional"))
      (node (ref "R20") (pin "2") (pinfunction "2_2") (pintype "passive"))
    )
    (net (code "144") (name "Net-(IC1-XTAL1)") (class "Default")
      (node (ref "C71") (pin "2") (pinfunction "2_2") (pintype "passive"))
      (node (ref "IC1") (pin "34") (pinfunction "XTAL1_34") (pintype "input"))
      (node (ref "Y1") (pin "1") (pinfunction "1_1") (pintype "passive"))
    )
    (net (code "145") (name "Net-(IC1-XTAL2)") (class "Default")
      (node (ref "C70") (pin "2") (pinfunction "2_2") (pintype "passive"))
      (node (ref "IC1") (pin "33") (pinfunction "XTAL2_33") (pintype "output"))
      (node (ref "Y1") (pin "2") (pinfunction "2_2") (pintype "passive"))
    )
    (net (code "146") (name "Net-(IC2-(CTS{slash}HWB{slash}AIN6{slash}TO{slash}INT7)PD7)") (class "Default")
      (node (ref "C46") (pin "1") (pinfunction "1_1") (pintype "passive"))
      (node (ref "IC2") (pin "13") (pinfunction "(CTS/HWB/AIN6/TO/INT7)PD7_13") (pintype "bidirectional"))
    )
    (net (code "147") (name "Net-(IC2-(INT5{slash}AIN3)PD4)") (class "Default")
      (node (ref "IC2") (pin "10") (pinfunction "(INT5/AIN3)PD4_10") (pintype "bidirectional"))
      (node (ref "RX") (pin "C") (pinfunction "C_C") (pintype "passive"))
    )
    (net (code "148") (name "Net-(IC2-(RXD1{slash}AIN1{slash}INT2)PD2)") (class "Default")
      (node (ref "IC2") (pin "8") (pinfunction "(RXD1/AIN1/INT2)PD2_8") (pintype "bidirectional"))
      (node (ref "R59") (pin "2") (pinfunction "2_2") (pintype "passive"))
    )
    (net (code "149") (name "Net-(IC2-(TXD1{slash}INT3)PD3)") (class "Default")
      (node (ref "IC2") (pin "9") (pinfunction "(TXD1/INT3)PD3_9") (pintype "bidirectional"))
      (node (ref "R75") (pin "2") (pinfunction "2_2") (pintype "passive"))
    )
    (net (code "150") (name "Net-(IC2-(XCK{slash}AIN4{slash}PCINT12)PD5)") (class "Default")
      (node (ref "IC2") (pin "11") (pinfunction "(XCK/AIN4/PCINT12)PD5_11") (pintype "bidirectional"))
      (node (ref "TX") (pin "C") (pinfunction "C_C") (pintype "passive"))
    )
    (net (code "151") (name "Net-(IC2-D+)") (class "Default")
      (node (ref "IC2") (pin "29") (pinfunction "D+_29") (pintype "bidirectional"))
      (node (ref "R81") (pin "1") (pinfunction "1_1") (pintype "passive"))
    )
    (net (code "152") (name "Net-(IC2-D-)") (class "Default")
      (node (ref "IC2") (pin "30") (pinfunction "D-_30") (pintype "bidirectional"))
      (node (ref "R79") (pin "1") (pinfunction "1_1") (pintype "passive"))
    )
    (net (code "153") (name "Net-(IC2-UCAP)") (class "Default")
      (node (ref "C47") (pin "2") (pinfunction "2_2") (pintype "passive"))
      (node (ref "IC2") (pin "27") (pinfunction "UCAP_27") (pintype "passive"))
    )
    (net (code "154") (name "Net-(IC2-XTAL1)") (class "Default")
      (node (ref "C72") (pin "2") (pinfunction "2_2") (pintype "passive"))
      (node (ref "IC2") (pin "1") (pinfunction "XTAL1_1") (pintype "bidirectional"))
      (node (ref "Y2") (pin "2") (pinfunction "2_2") (pintype "passive"))
    )
    (net (code "155") (name "Net-(IC2-XTAL2(PC0))") (class "Default")
      (node (ref "C73") (pin "2") (pinfunction "2_2") (pintype "passive"))
      (node (ref "IC2") (pin "2") (pinfunction "XTAL2(PC0)_2") (pintype "bidirectional"))
      (node (ref "Y2") (pin "1") (pinfunction "1_1") (pintype "passive"))
    )
    (net (code "156") (name "Net-(L-COOLB-1)") (class "Default")
      (node (ref "F4") (pin "C") (pinfunction "C_C") (pintype "passive"))
      (node (ref "L-COOL") (pin "2") (pinfunction "1_2") (pintype "passive"))
      (node (ref "M1") (pin "MB") (pinfunction "D_MB") (pintype "passive"))
    )
    (net (code "157") (name "Net-(L-HEATB-1)") (class "Default")
      (node (ref "F3") (pin "C") (pinfunction "C_C") (pintype "passive"))
      (node (ref "L-HEAT") (pin "2") (pinfunction "1_2") (pintype "passive"))
      (node (ref "M2") (pin "MB") (pinfunction "D_MB") (pintype "passive"))
    )
    (net (code "158") (name "Net-(L1-Pad2)") (class "Default")
      (node (ref "L1") (pin "2") (pinfunction "2_2") (pintype "passive"))
      (node (ref "R84") (pin "1") (pinfunction "1_1") (pintype "passive"))
      (node (ref "R85") (pin "1") (pinfunction "1_1") (pintype "passive"))
      (node (ref "X8") (pin "P$1") (pinfunction "P$1_P$1") (pintype "bidirectional"))
      (node (ref "X8") (pin "P$2") (pinfunction "P$2_P$2") (pintype "bidirectional"))
    )
    (net (code "159") (name "Net-(LC1-A)") (class "Default")
      (node (ref "LC1") (pin "6") (pinfunction "A_6") (pintype "bidirectional"))
      (node (ref "R12") (pin "1") (pinfunction "1_1") (pintype "passive"))
    )
    (net (code "160") (name "Net-(LC1-SDA)") (class "Default")
      (node (ref "LC1") (pin "4") (pinfunction "SDA_4") (pintype "bidirectional"))
      (node (ref "R21") (pin "1") (pinfunction "1_1") (pintype "passive"))
    )
    (net (code "161") (name "Net-(LC2-A)") (class "Default")
      (node (ref "LC2") (pin "6") (pinfunction "A_6") (pintype "bidirectional"))
      (node (ref "R35") (pin "1") (pinfunction "1_1") (pintype "passive"))
    )
    (net (code "162") (name "Net-(LC2-SDA)") (class "Default")
      (node (ref "LC2") (pin "4") (pinfunction "SDA_4") (pintype "bidirectional"))
      (node (ref "R45") (pin "1") (pinfunction "1_1") (pintype "passive"))
    )
    (net (code "163") (name "Net-(LC3-A)") (class "Default")
      (node (ref "LC3") (pin "6") (pinfunction "A_6") (pintype "bidirectional"))
      (node (ref "R60") (pin "1") (pinfunction "1_1") (pintype "passive"))
    )
    (net (code "164") (name "Net-(LC3-SDA)") (class "Default")
      (node (ref "LC3") (pin "4") (pinfunction "SDA_4") (pintype "bidirectional"))
      (node (ref "R66") (pin "1") (pinfunction "1_1") (pintype "passive"))
    )
    (net (code "165") (name "Net-(LC4-A)") (class "Default")
      (node (ref "LC4") (pin "6") (pinfunction "A_6") (pintype "bidirectional"))
      (node (ref "R87") (pin "1") (pinfunction "1_1") (pintype "passive"))
    )
    (net (code "166") (name "Net-(LC4-SDA)") (class "Default")
      (node (ref "LC4") (pin "4") (pinfunction "SDA_4") (pintype "bidirectional"))
      (node (ref "R93") (pin "1") (pinfunction "1_1") (pintype "passive"))
    )
    (net (code "167") (name "Net-(LC5-1A)") (class "Default")
      (node (ref "LC5") (pin "1") (pinfunction "1A_1") (pintype "bidirectional"))
      (node (ref "R105") (pin "2") (pinfunction "2_2") (pintype "passive"))
      (node (ref "R106") (pin "1") (pinfunction "1_1") (pintype "passive"))
    )
    (net (code "168") (name "Net-(LC5-1Y)") (class "Default")
      (node (ref "LC5") (pin "7") (pinfunction "1Y_7") (pintype "bidirectional"))
      (node (ref "M10") (pin "1") (pinfunction "G_1") (pintype "bidirectional"))
    )
    (net (code "169") (name "Net-(LC5-2A)") (class "Default")
      (node (ref "LC5") (pin "3") (pinfunction "2A_3") (pintype "bidirectional"))
      (node (ref "R112") (pin "2") (pinfunction "2_2") (pintype "passive"))
      (node (ref "R113") (pin "1") (pinfunction "1_1") (pintype "passive"))
    )
    (net (code "170") (name "Net-(LC5-2Y)") (class "Default")
      (node (ref "LC5") (pin "5") (pinfunction "2Y_5") (pintype "bidirectional"))
      (node (ref "M9") (pin "1") (pinfunction "G_1") (pintype "bidirectional"))
    )
    (net (code "171") (name "Net-(LC5-3A)") (class "Default")
      (node (ref "LC5") (pin "6") (pinfunction "3A_6") (pintype "bidirectional"))
      (node (ref "R115") (pin "2") (pinfunction "2_2") (pintype "passive"))
      (node (ref "R116") (pin "1") (pinfunction "1_1") (pintype "passive"))
    )
    (net (code "172") (name "Net-(LC5-3Y)") (class "Default")
      (node (ref "LC5") (pin "2") (pinfunction "3Y_2") (pintype "bidirectional"))
      (node (ref "M8") (pin "1") (pinfunction "G_1") (pintype "bidirectional"))
    )
    (net (code "173") (name "Net-(LC6-LED0)") (class "Default")
      (node (ref "LC6") (pin "1") (pinfunction "LED0_1") (pintype "bidirectional"))
      (node (ref "R106") (pin "2") (pinfunction "2_2") (pintype "passive"))
    )
    (net (code "174") (name "Net-(LC6-LED1)") (class "Default")
      (node (ref "LC6") (pin "2") (pinfunction "LED1_2") (pintype "bidirectional"))
      (node (ref "R113") (pin "2") (pinfunction "2_2") (pintype "passive"))
    )
    (net (code "175") (name "Net-(LC6-LED2)") (class "Default")
      (node (ref "LC6") (pin "3") (pinfunction "LED2_3") (pintype "bidirectional"))
      (node (ref "R116") (pin "2") (pinfunction "2_2") (pintype "passive"))
    )
    (net (code "176") (name "Net-(LC7-A)") (class "Default")
      (node (ref "LC7") (pin "6") (pinfunction "A_6") (pintype "bidirectional"))
      (node (ref "R107") (pin "1") (pinfunction "1_1") (pintype "passive"))
    )
    (net (code "177") (name "Net-(LC7-SDA)") (class "Default")
      (node (ref "LC7") (pin "4") (pinfunction "SDA_4") (pintype "bidirectional"))
      (node (ref "R118") (pin "1") (pinfunction "1_1") (pintype "passive"))
    )
    (net (code "178") (name "Net-(LED4-PadA)") (class "Default")
      (node (ref "LED4") (pin "A") (pinfunction "A_A") (pintype "passive"))
      (node (ref "R8") (pin "1") (pinfunction "1_1") (pintype "passive"))
    )
    (net (code "179") (name "Net-(LED5-PadA)") (class "Default")
      (node (ref "LED5") (pin "A") (pinfunction "A_A") (pintype "passive"))
      (node (ref "R18") (pin "1") (pinfunction "1_1") (pintype "passive"))
    )
    (net (code "180") (name "Net-(LED7-PadA)") (class "Default")
      (node (ref "LED7") (pin "A") (pinfunction "A_A") (pintype "passive"))
      (node (ref "R31") (pin "1") (pinfunction "1_1") (pintype "passive"))
    )
    (net (code "181") (name "Net-(LED9-PadA)") (class "Default")
      (node (ref "LED9") (pin "A") (pinfunction "A_A") (pintype "passive"))
      (node (ref "R34") (pin "1") (pinfunction "1_1") (pintype "passive"))
    )
    (net (code "182") (name "Net-(LED10-PadA)") (class "Default")
      (node (ref "LED10") (pin "A") (pinfunction "A_A") (pintype "passive"))
      (node (ref "R43") (pin "1") (pinfunction "1_1") (pintype "passive"))
    )
    (net (code "183") (name "Net-(LED12-PadA)") (class "Default")
      (node (ref "LED12") (pin "A") (pinfunction "A_A") (pintype "passive"))
      (node (ref "R57") (pin "1") (pinfunction "1_1") (pintype "passive"))
    )
    (net (code "184") (name "Net-(LED14-PadA)") (class "Default")
      (node (ref "LED14") (pin "A") (pinfunction "A_A") (pintype "passive"))
      (node (ref "R58") (pin "1") (pinfunction "1_1") (pintype "passive"))
    )
    (net (code "185") (name "Net-(LED16-PadA)") (class "Default")
      (node (ref "LED16") (pin "A") (pinfunction "A_A") (pintype "passive"))
      (node (ref "R72") (pin "1") (pinfunction "1_1") (pintype "passive"))
    )
    (net (code "186") (name "Net-(LED19-PadA)") (class "Default")
      (node (ref "LED19") (pin "A") (pinfunction "A_A") (pintype "passive"))
      (node (ref "R82") (pin "1") (pinfunction "1_1") (pintype "passive"))
    )
    (net (code "187") (name "Net-(LED21-PadA)") (class "Default")
      (node (ref "LED21") (pin "A") (pinfunction "A_A") (pintype "passive"))
      (node (ref "R102") (pin "1") (pinfunction "1_1") (pintype "passive"))
    )
    (net (code "188") (name "Net-(M3-D)") (class "Default")
      (node (ref "F2") (pin "C") (pinfunction "C_C") (pintype "passive"))
      (node (ref "M3") (pin "MB") (pinfunction "D_MB") (pintype "passive"))
      (node (ref "R-COOL") (pin "2") (pinfunction "1_2") (pintype "passive"))
    )
    (net (code "189") (name "Net-(M4-D)") (class "Default")
      (node (ref "F1") (pin "C") (pinfunction "C_C") (pintype "passive"))
      (node (ref "M4") (pin "MB") (pinfunction "D_MB") (pintype "passive"))
      (node (ref "R-HEAT") (pin "2") (pinfunction "1_2") (pintype "passive"))
    )
    (net (code "190") (name "Net-(M8-D)") (class "Default")
      (node (ref "M8") (pin "3") (pinfunction "D_3") (pintype "bidirectional"))
      (node (ref "RGB+") (pin "3") (pinfunction "3_3") (pintype "passive"))
    )
    (net (code "191") (name "Net-(M9-D)") (class "Default")
      (node (ref "M9") (pin "3") (pinfunction "D_3") (pintype "bidirectional"))
      (node (ref "RGB+") (pin "2") (pinfunction "2_2") (pintype "passive"))
    )
    (net (code "192") (name "Net-(M10-D)") (class "Default")
      (node (ref "M10") (pin "3") (pinfunction "D_3") (pintype "bidirectional"))
      (node (ref "RGB+") (pin "1") (pinfunction "1_1") (pintype "passive"))
    )
    (net (code "193") (name "Net-(R23-Pad2)") (class "Default")
      (node (ref "R23") (pin "2") (pinfunction "2_2") (pintype "passive"))
      (node (ref "R25") (pin "2") (pinfunction "2_2") (pintype "passive"))
      (node (ref "R28") (pin "1") (pinfunction "1_1") (pintype "passive"))
    )
    (net (code "194") (name "Net-(R47-Pad2)") (class "Default")
      (node (ref "R47") (pin "2") (pinfunction "2_2") (pintype "passive"))
      (node (ref "R48") (pin "2") (pinfunction "2_2") (pintype "passive"))
      (node (ref "R53") (pin "1") (pinfunction "1_1") (pintype "passive"))
    )
    (net (code "195") (name "Net-(R69-Pad2)") (class "Default")
      (node (ref "R69") (pin "2") (pinfunction "2_2") (pintype "passive"))
      (node (ref "R70") (pin "2") (pinfunction "2_2") (pintype "passive"))
      (node (ref "R77") (pin "1") (pinfunction "1_1") (pintype "passive"))
    )
    (net (code "196") (name "Net-(R78-Pad2)") (class "Default")
      (node (ref "R78") (pin "2") (pinfunction "2_2") (pintype "passive"))
      (node (ref "RX") (pin "A") (pinfunction "A_A") (pintype "passive"))
    )
    (net (code "197") (name "Net-(R80-Pad2)") (class "Default")
      (node (ref "R80") (pin "2") (pinfunction "2_2") (pintype "passive"))
      (node (ref "TX") (pin "A") (pinfunction "A_A") (pintype "passive"))
    )
    (net (code "198") (name "Net-(R101-Pad1)") (class "Default")
      (node (ref "R101") (pin "1") (pinfunction "1_1") (pintype "passive"))
      (node (ref "R96") (pin "2") (pinfunction "2_2") (pintype "passive"))
      (node (ref "R97") (pin "2") (pinfunction "2_2") (pintype "passive"))
    )
    (net (code "199") (name "Net-(R123-Pad2)") (class "Default")
      (node (ref "R123") (pin "2") (pinfunction "2_2") (pintype "passive"))
      (node (ref "R124") (pin "2") (pinfunction "2_2") (pintype "passive"))
      (node (ref "R128") (pin "1") (pinfunction "1_1") (pintype "passive"))
    )
    (net (code "200") (name "Net-(T1-CS)") (class "Default")
      (node (ref "R130") (pin "2") (pinfunction "2_2") (pintype "passive"))
      (node (ref "T1") (pin "6") (pinfunction "CS_6") (pintype "input"))
    )
    (net (code "201") (name "Net-(T1-GND)") (class "Default")
      (node (ref "C68") (pin "1") (pinfunction "1_1") (pintype "passive"))
      (node (ref "C69") (pin "1") (pinfunction "1_1") (pintype "passive"))
      (node (ref "R137") (pin "2") (pinfunction "2_2") (pintype "passive"))
      (node (ref "R138") (pin "2") (pinfunction "2_2") (pintype "passive"))
      (node (ref "R139") (pin "1") (pinfunction "1_1") (pintype "passive"))
      (node (ref "T1") (pin "1") (pinfunction "GND_1") (pintype "power_in"))
      (node (ref "T2") (pin "1") (pinfunction "GND_1") (pintype "power_in"))
    )
    (net (code "202") (name "Net-(T1-SCK)") (class "Default")
      (node (ref "R136") (pin "2") (pinfunction "2_2") (pintype "passive"))
      (node (ref "T1") (pin "5") (pinfunction "SCK_5") (pintype "input"))
    )
    (net (code "203") (name "Net-(T1-SO)") (class "Default")
      (node (ref "R133") (pin "2") (pinfunction "2_2") (pintype "passive"))
      (node (ref "T1") (pin "7") (pinfunction "SO_7") (pintype "output"))
    )
    (net (code "204") (name "Net-(T1-T+)") (class "Default")
      (node (ref "C66") (pin "1") (pinfunction "1_1") (pintype "passive"))
      (node (ref "JP2") (pin "2") (pinfunction "2_2") (pintype "passive"))
      (node (ref "T1") (pin "3") (pinfunction "T+_3") (pintype "input"))
    )
    (net (code "205") (name "Net-(T1-T-)") (class "Default")
      (node (ref "C66") (pin "2") (pinfunction "2_2") (pintype "passive"))
      (node (ref "JP2") (pin "1") (pinfunction "1_1") (pintype "passive"))
      (node (ref "R137") (pin "1") (pinfunction "1_1") (pintype "passive"))
      (node (ref "T1") (pin "2") (pinfunction "T-_2") (pintype "input"))
    )
    (net (code "206") (name "Net-(T2-CS)") (class "Default")
      (node (ref "R131") (pin "2") (pinfunction "2_2") (pintype "passive"))
      (node (ref "T2") (pin "6") (pinfunction "CS_6") (pintype "input"))
    )
    (net (code "207") (name "Net-(T2-SCK)") (class "Default")
      (node (ref "R135") (pin "2") (pinfunction "2_2") (pintype "passive"))
      (node (ref "T2") (pin "5") (pinfunction "SCK_5") (pintype "input"))
    )
    (net (code "208") (name "Net-(T2-SO)") (class "Default")
      (node (ref "R134") (pin "2") (pinfunction "2_2") (pintype "passive"))
      (node (ref "T2") (pin "7") (pinfunction "SO_7") (pintype "output"))
    )
    (net (code "209") (name "Net-(T2-T+)") (class "Default")
      (node (ref "C67") (pin "1") (pinfunction "1_1") (pintype "passive"))
      (node (ref "JP1") (pin "2") (pinfunction "2_2") (pintype "passive"))
      (node (ref "T2") (pin "3") (pinfunction "T+_3") (pintype "input"))
    )
    (net (code "210") (name "Net-(T2-T-)") (class "Default")
      (node (ref "C67") (pin "2") (pinfunction "2_2") (pintype "passive"))
      (node (ref "JP1") (pin "1") (pinfunction "1_1") (pintype "passive"))
      (node (ref "R138") (pin "1") (pinfunction "1_1") (pintype "passive"))
      (node (ref "T2") (pin "2") (pinfunction "T-_2") (pintype "input"))
    )
    (net (code "211") (name "P-STOP") (class "Default")
      (node (ref "C4") (pin "1") (pinfunction "1_1") (pintype "passive"))
      (node (ref "IC1") (pin "35") (pinfunction "PL0(ICP4)_35") (pintype "bidirectional"))
      (node (ref "LED5") (pin "C") (pinfunction "C_C") (pintype "passive"))
      (node (ref "P-STOP") (pin "1") (pinfunction "1_1") (pintype "passive"))
      (node (ref "R11") (pin "1") (pinfunction "1_1") (pintype "passive"))
    )
    (net (code "212") (name "POTS-SCL") (class "Default")
      (node (ref "IC1") (pin "68") (pinfunction "PJ5(PCINT14)_68") (pintype "bidirectional"))
      (node (ref "LC1") (pin "3") (pinfunction "SCL_3") (pintype "bidirectional"))
      (node (ref "LC2") (pin "3") (pinfunction "SCL_3") (pintype "bidirectional"))
      (node (ref "LC3") (pin "3") (pinfunction "SCL_3") (pintype "bidirectional"))
      (node (ref "LC4") (pin "3") (pinfunction "SCL_3") (pintype "bidirectional"))
      (node (ref "LC7") (pin "3") (pinfunction "SCL_3") (pintype "bidirectional"))
    )
    (net (code "213") (name "RESET") (class "Default")
      (node (ref "C1") (pin "2") (pinfunction "2_2") (pintype "passive"))
      (node (ref "C46") (pin "2") (pinfunction "2_2") (pintype "passive"))
      (node (ref "IC1") (pin "30") (pinfunction "RESET_30") (pintype "input"))
      (node (ref "PIN1") (pin "5") (pinfunction "5_5") (pintype "passive"))
      (node (ref "R1") (pin "1") (pinfunction "1_1") (pintype "passive"))
      (node (ref "RESET") (pin "1") (pinfunction "S_1") (pintype "passive"))
      (node (ref "RESET") (pin "2") (pinfunction "S1_2") (pintype "passive"))
    )
    (net (code "214") (name "RIGHT") (class "Default")
      (node (ref "IC1") (pin "64") (pinfunction "PJ1(TXD3/PCINT10)_64") (pintype "bidirectional"))
      (node (ref "SV2") (pin "19") (pinfunction "19_19") (pintype "passive"))
    )
    (net (code "215") (name "RLED") (class "Default")
      (node (ref "IC1") (pin "58") (pinfunction "(A13)PC5_58") (pintype "bidirectional"))
      (node (ref "SV2") (pin "15") (pinfunction "15_15") (pintype "passive"))
    )
    (net (code "216") (name "SCL") (class "Default")
      (node (ref "IC1") (pin "43") (pinfunction "(SCL/INT0)PD0_43") (pintype "bidirectional"))
      (node (ref "LC6") (pin "6") (pinfunction "SCL_6") (pintype "bidirectional"))
      (node (ref "PIN5") (pin "1") (pinfunction "1_1") (pintype "passive"))
      (node (ref "R117") (pin "1") (pinfunction "1_1") (pintype "passive"))
    )
    (net (code "217") (name "SD-CD") (class "Default")
      (node (ref "IC1") (pin "18") (pinfunction "PH6(OC2B)_18") (pintype "bidirectional"))
      (node (ref "SV2") (pin "12") (pinfunction "12_12") (pintype "passive"))
    )
    (net (code "218") (name "SD-CS") (class "Default")
      (node (ref "IC1") (pin "19") (pinfunction "(SS/PCINT0)PB0_19") (pintype "bidirectional"))
      (node (ref "SV2") (pin "9") (pinfunction "9_9") (pintype "passive"))
    )
    (net (code "219") (name "SD-MOSI") (class "Default")
      (node (ref "IC1") (pin "21") (pinfunction "(MOSI/PCINT2)PB2_21") (pintype "bidirectional"))
      (node (ref "PIN1") (pin "4") (pinfunction "4_4") (pintype "passive"))
      (node (ref "SV2") (pin "7") (pinfunction "7_7") (pintype "passive"))
    )
    (net (code "220") (name "SD-SCK") (class "Default")
      (node (ref "IC1") (pin "20") (pinfunction "(SCK/PCINT1)PB1_20") (pintype "bidirectional"))
      (node (ref "PIN1") (pin "3") (pinfunction "3_3") (pintype "passive"))
      (node (ref "SV2") (pin "10") (pinfunction "10_10") (pintype "passive"))
    )
    (net (code "221") (name "SD-WP") (class "Default")
      (node (ref "IC1") (pin "17") (pinfunction "PH5(OC4C)_17") (pintype "bidirectional"))
      (node (ref "SV2") (pin "11") (pinfunction "11_11") (pintype "passive"))
    )
    (net (code "222") (name "SDA") (class "Default")
      (node (ref "IC1") (pin "44") (pinfunction "(SDA/INT1)PD1_44") (pintype "bidirectional"))
      (node (ref "LC6") (pin "7") (pinfunction "SDA_7") (pintype "bidirectional"))
      (node (ref "PIN6") (pin "1") (pinfunction "1_1") (pintype "passive"))
      (node (ref "R114") (pin "1") (pinfunction "1_1") (pintype "passive"))
    )
    (net (code "223") (name "THERMO-CS1") (class "Default")
      (node (ref "IC1") (pin "5") (pinfunction "(OC3A/AIN1)PE3_5") (pintype "bidirectional"))
      (node (ref "R129") (pin "1") (pinfunction "1_1") (pintype "passive"))
      (node (ref "R130") (pin "1") (pinfunction "1_1") (pintype "passive"))
    )
    (net (code "224") (name "THERMO-CS2") (class "Default")
      (node (ref "IC1") (pin "6") (pinfunction "(OC3B/INT4)PE4_6") (pintype "bidirectional"))
      (node (ref "R131") (pin "1") (pinfunction "1_1") (pintype "passive"))
      (node (ref "R132") (pin "1") (pinfunction "1_1") (pintype "passive"))
    )
    (net (code "225") (name "THERMO-DO") (class "Default")
      (node (ref "IC1") (pin "7") (pinfunction "(OC3C/INT5)PE5_7") (pintype "bidirectional"))
      (node (ref "R133") (pin "1") (pinfunction "1_1") (pintype "passive"))
      (node (ref "R134") (pin "1") (pinfunction "1_1") (pintype "passive"))
    )
    (net (code "226") (name "THERMO-SCK") (class "Default")
      (node (ref "IC1") (pin "4") (pinfunction "(XCK0/AIN0)PE2_4") (pintype "bidirectional"))
      (node (ref "R135") (pin "1") (pinfunction "1_1") (pintype "passive"))
      (node (ref "R136") (pin "1") (pinfunction "1_1") (pintype "passive"))
    )
    (net (code "227") (name "UART0-RX") (class "Default")
      (node (ref "IC1") (pin "2") (pinfunction "(RXD0/PCIN8)PE0_2") (pintype "bidirectional"))
      (node (ref "R75") (pin "1") (pinfunction "1_1") (pintype "passive"))
    )
    (net (code "228") (name "UART0-TX") (class "Default")
      (node (ref "IC1") (pin "3") (pinfunction "(TXD0)PE1_3") (pintype "bidirectional"))
      (node (ref "R59") (pin "1") (pinfunction "1_1") (pintype "passive"))
    )
    (net (code "229") (name "UART1-RX") (class "Default")
      (node (ref "IC1") (pin "45") (pinfunction "(RXD1/INT2)PD2_45") (pintype "bidirectional"))
      (node (ref "PIN3") (pin "1") (pinfunction "1_1") (pintype "passive"))
      (node (ref "SV2") (pin "1") (pinfunction "1_1") (pintype "passive"))
    )
    (net (code "230") (name "UART1-TX") (class "Default")
      (node (ref "IC1") (pin "46") (pinfunction "(TXD1/INT3)PD3_46") (pintype "bidirectional"))
      (node (ref "PIN4") (pin "1") (pinfunction "1_1") (pintype "passive"))
      (node (ref "SV2") (pin "3") (pinfunction "3_3") (pintype "passive"))
    )
    (net (code "231") (name "UP") (class "Default")
      (node (ref "IC1") (pin "67") (pinfunction "PJ4(PCINT13)_67") (pintype "bidirectional"))
      (node (ref "SV2") (pin "24") (pinfunction "24_24") (pintype "passive"))
    )
    (net (code "232") (name "UVCC") (class "Default")
      (node (ref "C45") (pin "2") (pinfunction "2_2") (pintype "passive"))
      (node (ref "IC2") (pin "31") (pinfunction "UVCC_31") (pintype "power_in"))
      (node (ref "X8") (pin "1") (pinfunction "1_1") (pintype "bidirectional"))
    )
    (net (code "233") (name "X-DIR") (class "Default")
      (node (ref "A5") (pin "P20") (pinfunction "DIR_P20") (pintype "bidirectional"))
      (node (ref "IC1") (pin "97") (pinfunction "(ADC0)PF0_97") (pintype "bidirectional"))
    )
    (net (code "234") (name "X-EN") (class "Default")
      (node (ref "A5") (pin "P05") (pinfunction "ENABLE_P05") (pintype "bidirectional"))
      (node (ref "IC1") (pin "95") (pinfunction "(ADC2)PF2_95") (pintype "bidirectional"))
      (node (ref "R111") (pin "1") (pinfunction "1_1") (pintype "passive"))
    )
    (net (code "235") (name "X-MAX") (class "Default")
      (node (ref "C14") (pin "1") (pinfunction "1_1") (pintype "passive"))
      (node (ref "IC1") (pin "36") (pinfunction "PL1(ICP5)_36") (pintype "bidirectional"))
      (node (ref "LED7") (pin "C") (pinfunction "C_C") (pintype "passive"))
      (node (ref "R30") (pin "1") (pinfunction "1_1") (pintype "passive"))
      (node (ref "X-MAX") (pin "1") (pinfunction "1_1") (pintype "passive"))
    )
    (net (code "236") (name "X-POT") (class "Default")
      (node (ref "IC1") (pin "94") (pinfunction "(ADC3)PF3_94") (pintype "bidirectional"))
      (node (ref "R118") (pin "2") (pinfunction "2_2") (pintype "passive"))
    )
    (net (code "237") (name "X-STEP") (class "Default")
      (node (ref "A5") (pin "P17") (pinfunction "STEP_P17") (pintype "bidirectional"))
      (node (ref "IC1") (pin "96") (pinfunction "(ADC1)PF1_96") (pintype "bidirectional"))
    )
    (net (code "238") (name "Y-DIR") (class "Default")
      (node (ref "A4") (pin "P20") (pinfunction "DIR_P20") (pintype "bidirectional"))
      (node (ref "IC1") (pin "93") (pinfunction "(ADC4/TCK)PF4_93") (pintype "bidirectional"))
    )
    (net (code "239") (name "Y-EN") (class "Default")
      (node (ref "A4") (pin "P05") (pinfunction "ENABLE_P05") (pintype "bidirectional"))
      (node (ref "IC1") (pin "91") (pinfunction "(ADC6/TDO)PF6_91") (pintype "bidirectional"))
      (node (ref "R91") (pin "1") (pinfunction "1_1") (pintype "passive"))
    )
    (net (code "240") (name "Y-MAX") (class "Default")
      (node (ref "C20") (pin "1") (pinfunction "1_1") (pintype "passive"))
      (node (ref "IC1") (pin "38") (pinfunction "PL3(OC5A)_38") (pintype "bidirectional"))
      (node (ref "LED10") (pin "C") (pinfunction "C_C") (pintype "passive"))
      (node (ref "R42") (pin "1") (pinfunction "1_1") (pintype "passive"))
      (node (ref "Y-MAX") (pin "1") (pinfunction "1_1") (pintype "passive"))
    )
    (net (code "241") (name "Y-MIN") (class "Default")
      (node (ref "IC1") (pin "37") (pinfunction "PL2(T5)_37") (pintype "bidirectional"))
      (node (ref "M7") (pin "4") (pinfunction "G_4") (pintype "passive"))
      (node (ref "PIN7") (pin "1") (pinfunction "1_1") (pintype "passive"))
      (node (ref "PIN8") (pin "1") (pinfunction "1_1") (pintype "passive"))
      (node (ref "R83") (pin "2") (pinfunction "2_2") (pintype "passive"))
    )
    (net (code "242") (name "Y-POT") (class "Default")
      (node (ref "IC1") (pin "90") (pinfunction "(ADC7/TDI)PF7_90") (pintype "bidirectional"))
      (node (ref "R93") (pin "2") (pinfunction "2_2") (pintype "passive"))
    )
    (net (code "243") (name "Y-STEP") (class "Default")
      (node (ref "A4") (pin "P17") (pinfunction "STEP_P17") (pintype "bidirectional"))
      (node (ref "IC1") (pin "92") (pinfunction "(ADC5/TMS)PF5_92") (pintype "bidirectional"))
    )
    (net (code "244") (name "Z-DIR") (class "Default")
      (node (ref "A3") (pin "P20") (pinfunction "DIR_P20") (pintype "bidirectional"))
      (node (ref "IC1") (pin "89") (pinfunction "PK0(ADC8/PCINT16)_89") (pintype "bidirectional"))
    )
    (net (code "245") (name "Z-EN") (class "Default")
      (node (ref "A3") (pin "P05") (pinfunction "ENABLE_P05") (pintype "bidirectional"))
      (node (ref "IC1") (pin "87") (pinfunction "PK2(ADC10/PCINT18)_87") (pintype "bidirectional"))
      (node (ref "R64") (pin "1") (pinfunction "1_1") (pintype "passive"))
    )
    (net (code "246") (name "Z-MAX") (class "Default")
      (node (ref "C41") (pin "1") (pinfunction "1_1") (pintype "passive"))
      (node (ref "IC1") (pin "42") (pinfunction "PL7_42") (pintype "bidirectional"))
      (node (ref "LED16") (pin "C") (pinfunction "C_C") (pintype "passive"))
      (node (ref "R71") (pin "1") (pinfunction "1_1") (pintype "passive"))
      (node (ref "Z-MAX") (pin "1") (pinfunction "1_1") (pintype "passive"))
    )
    (net (code "247") (name "Z-MIN") (class "Default")
      (node (ref "C32") (pin "1") (pinfunction "1_1") (pintype "passive"))
      (node (ref "IC1") (pin "41") (pinfunction "PL6_41") (pintype "bidirectional"))
      (node (ref "LED12") (pin "C") (pinfunction "C_C") (pintype "passive"))
      (node (ref "R55") (pin "1") (pinfunction "1_1") (pintype "passive"))
      (node (ref "Z-MIN") (pin "1") (pinfunction "1_1") (pintype "passive"))
    )
    (net (code "248") (name "Z-POT") (class "Default")
      (node (ref "IC1") (pin "86") (pinfunction "PK3(ADC11/PCINT19)_86") (pintype "bidirectional"))
      (node (ref "R66") (pin "2") (pinfunction "2_2") (pintype "passive"))
    )
    (net (code "249") (name "Z-STEP") (class "Default")
      (node (ref "A3") (pin "P17") (pinfunction "STEP_P17") (pintype "bidirectional"))
      (node (ref "IC1") (pin "88") (pinfunction "PK1(ADC9/PCINT17)_88") (pintype "bidirectional"))
    )
    (net (code "250") (name "unconnected-(15A_SWITCH-OUT1-Pad1B)") (class "Default")
      (node (ref "15A_SWITCH") (pin "1B") (pinfunction "OUT1_1B") (pintype "bidirectional"))
    )
    (net (code "251") (name "unconnected-(IC1-(AD0)PA0-Pad78)") (class "Default")
      (node (ref "IC1") (pin "78") (pinfunction "(AD0)PA0_78") (pintype "bidirectional"))
    )
    (net (code "252") (name "unconnected-(IC1-(AD1)PA1-Pad77)") (class "Default")
      (node (ref "IC1") (pin "77") (pinfunction "(AD1)PA1_77") (pintype "bidirectional"))
    )
    (net (code "253") (name "unconnected-(IC1-(CLKO{slash}ICP3{slash}INT7)PE7-Pad9)") (class "Default")
      (node (ref "IC1") (pin "9") (pinfunction "(CLKO/ICP3/INT7)PE7_9") (pintype "bidirectional"))
    )
    (net (code "254") (name "unconnected-(IC1-(ICP1)PD4-Pad47)") (class "Default")
      (node (ref "IC1") (pin "47") (pinfunction "(ICP1)PD4_47") (pintype "bidirectional"))
    )
    (net (code "255") (name "unconnected-(IC1-(T0)PD7-Pad50)") (class "Default")
      (node (ref "IC1") (pin "50") (pinfunction "(T0)PD7_50") (pintype "bidirectional"))
    )
    (net (code "256") (name "unconnected-(IC1-(T1)PD6-Pad49)") (class "Default")
      (node (ref "IC1") (pin "49") (pinfunction "(T1)PD6_49") (pintype "bidirectional"))
    )
    (net (code "257") (name "unconnected-(IC1-(T3{slash}INT6)PE6-Pad8)") (class "Default")
      (node (ref "IC1") (pin "8") (pinfunction "(T3/INT6)PE6_8") (pintype "bidirectional"))
    )
    (net (code "258") (name "unconnected-(IC1-(TOSC2)PG3-Pad28)") (class "Default")
      (node (ref "IC1") (pin "28") (pinfunction "(TOSC2)PG3_28") (pintype "bidirectional"))
    )
    (net (code "259") (name "unconnected-(IC1-(WR)PG0-Pad51)") (class "Default")
      (node (ref "IC1") (pin "51") (pinfunction "(WR)PG0_51") (pintype "bidirectional"))
    )
    (net (code "260") (name "unconnected-(IC1-(XCK1)PD5-Pad48)") (class "Default")
      (node (ref "IC1") (pin "48") (pinfunction "(XCK1)PD5_48") (pintype "bidirectional"))
    )
    (net (code "261") (name "unconnected-(IC1-PH7(T4)-Pad27)") (class "Default")
      (node (ref "IC1") (pin "27") (pinfunction "PH7(T4)_27") (pintype "bidirectional"))
    )
    (net (code "262") (name "unconnected-(IC1-PJ7-Pad79)") (class "Default")
      (node (ref "IC1") (pin "79") (pinfunction "PJ7_79") (pintype "bidirectional"))
    )
    (net (code "263") (name "unconnected-(IC1-PK4(ADC12{slash}PCINT20)-Pad85)") (class "Default")
      (node (ref "IC1") (pin "85") (pinfunction "PK4(ADC12/PCINT20)_85") (pintype "bidirectional"))
    )
    (net (code "264") (name "unconnected-(IC1-PK5(ADC13{slash}PCINT21)-Pad84)") (class "Default")
      (node (ref "IC1") (pin "84") (pinfunction "PK5(ADC13/PCINT21)_84") (pintype "bidirectional"))
    )
    (net (code "265") (name "unconnected-(IC1-PK6(ADC14{slash}PCINT22)-Pad83)") (class "Default")
      (node (ref "IC1") (pin "83") (pinfunction "PK6(ADC14/PCINT22)_83") (pintype "bidirectional"))
    )
    (net (code "266") (name "unconnected-(IC2-(AIN0{slash}INT1)PD1-Pad7)") (class "Default")
      (node (ref "IC2") (pin "7") (pinfunction "(AIN0/INT1)PD1_7") (pintype "bidirectional"))
    )
    (net (code "267") (name "unconnected-(IC2-(AIN2{slash}PCINT11)PC2-Pad5)") (class "Default")
      (node (ref "IC2") (pin "5") (pinfunction "(AIN2/PCINT11)PC2_5") (pintype "bidirectional"))
    )
    (net (code "268") (name "unconnected-(IC2-(INT4{slash}ICP1{slash}CLK0)PC7-Pad22)") (class "Default")
      (node (ref "IC2") (pin "22") (pinfunction "(INT4/ICP1/CLK0)PC7_22") (pintype "bidirectional"))
    )
    (net (code "269") (name "unconnected-(IC2-(OC0B{slash}INT0)PD0-Pad6)") (class "Default")
      (node (ref "IC2") (pin "6") (pinfunction "(OC0B/INT0)PD0_6") (pintype "bidirectional"))
    )
    (net (code "270") (name "unconnected-(IC2-(OC1A{slash}PCINT8)PC6-Pad23)") (class "Default")
      (node (ref "IC2") (pin "23") (pinfunction "(OC1A/PCINT8)PC6_23") (pintype "bidirectional"))
    )
    (net (code "271") (name "unconnected-(IC2-(PCINT5)PB5-Pad19)") (class "Default")
      (node (ref "IC2") (pin "19") (pinfunction "(PCINT5)PB5_19") (pintype "bidirectional"))
    )
    (net (code "272") (name "unconnected-(IC2-(PCINT6)PB6-Pad20)") (class "Default")
      (node (ref "IC2") (pin "20") (pinfunction "(PCINT6)PB6_20") (pintype "bidirectional"))
    )
    (net (code "273") (name "unconnected-(IC2-(PCINT7{slash}OC0A{slash}OC1C)PB7-Pad21)") (class "Default")
      (node (ref "IC2") (pin "21") (pinfunction "(PCINT7/OC0A/OC1C)PB7_21") (pintype "bidirectional"))
    )
    (net (code "274") (name "unconnected-(IC2-(PCINT9{slash}OC1B)PC5-Pad25)") (class "Default")
      (node (ref "IC2") (pin "25") (pinfunction "(PCINT9/OC1B)PC5_25") (pintype "bidirectional"))
    )
    (net (code "275") (name "unconnected-(IC2-(PCINT10)PC4-Pad26)") (class "Default")
      (node (ref "IC2") (pin "26") (pinfunction "(PCINT10)PC4_26") (pintype "bidirectional"))
    )
    (net (code "276") (name "unconnected-(IC2-(RTS{slash}AIN5{slash}INT6)PD6-Pad12)") (class "Default")
      (node (ref "IC2") (pin "12") (pinfunction "(RTS/AIN5/INT6)PD6_12") (pintype "bidirectional"))
    )
    (net (code "277") (name "unconnected-(IC2-(SS{slash}PCINT0)PB0-Pad14)") (class "Default")
      (node (ref "IC2") (pin "14") (pinfunction "(SS/PCINT0)PB0_14") (pintype "bidirectional"))
    )
    (net (code "278") (name "unconnected-(IC2-(T1{slash}PCINT4)PB4-Pad18)") (class "Default")
      (node (ref "IC2") (pin "18") (pinfunction "(T1/PCINT4)PB4_18") (pintype "bidirectional"))
    )
    (net (code "279") (name "unconnected-(LC6-LED3-Pad5)") (class "Default")
      (node (ref "LC6") (pin "5") (pinfunction "LED3_5") (pintype "bidirectional"))
    )
  )
)
